# sensor_frontend_test_v0_5_e8a143b4.net
KiCad netlist of a schematic drawn in EAGLE
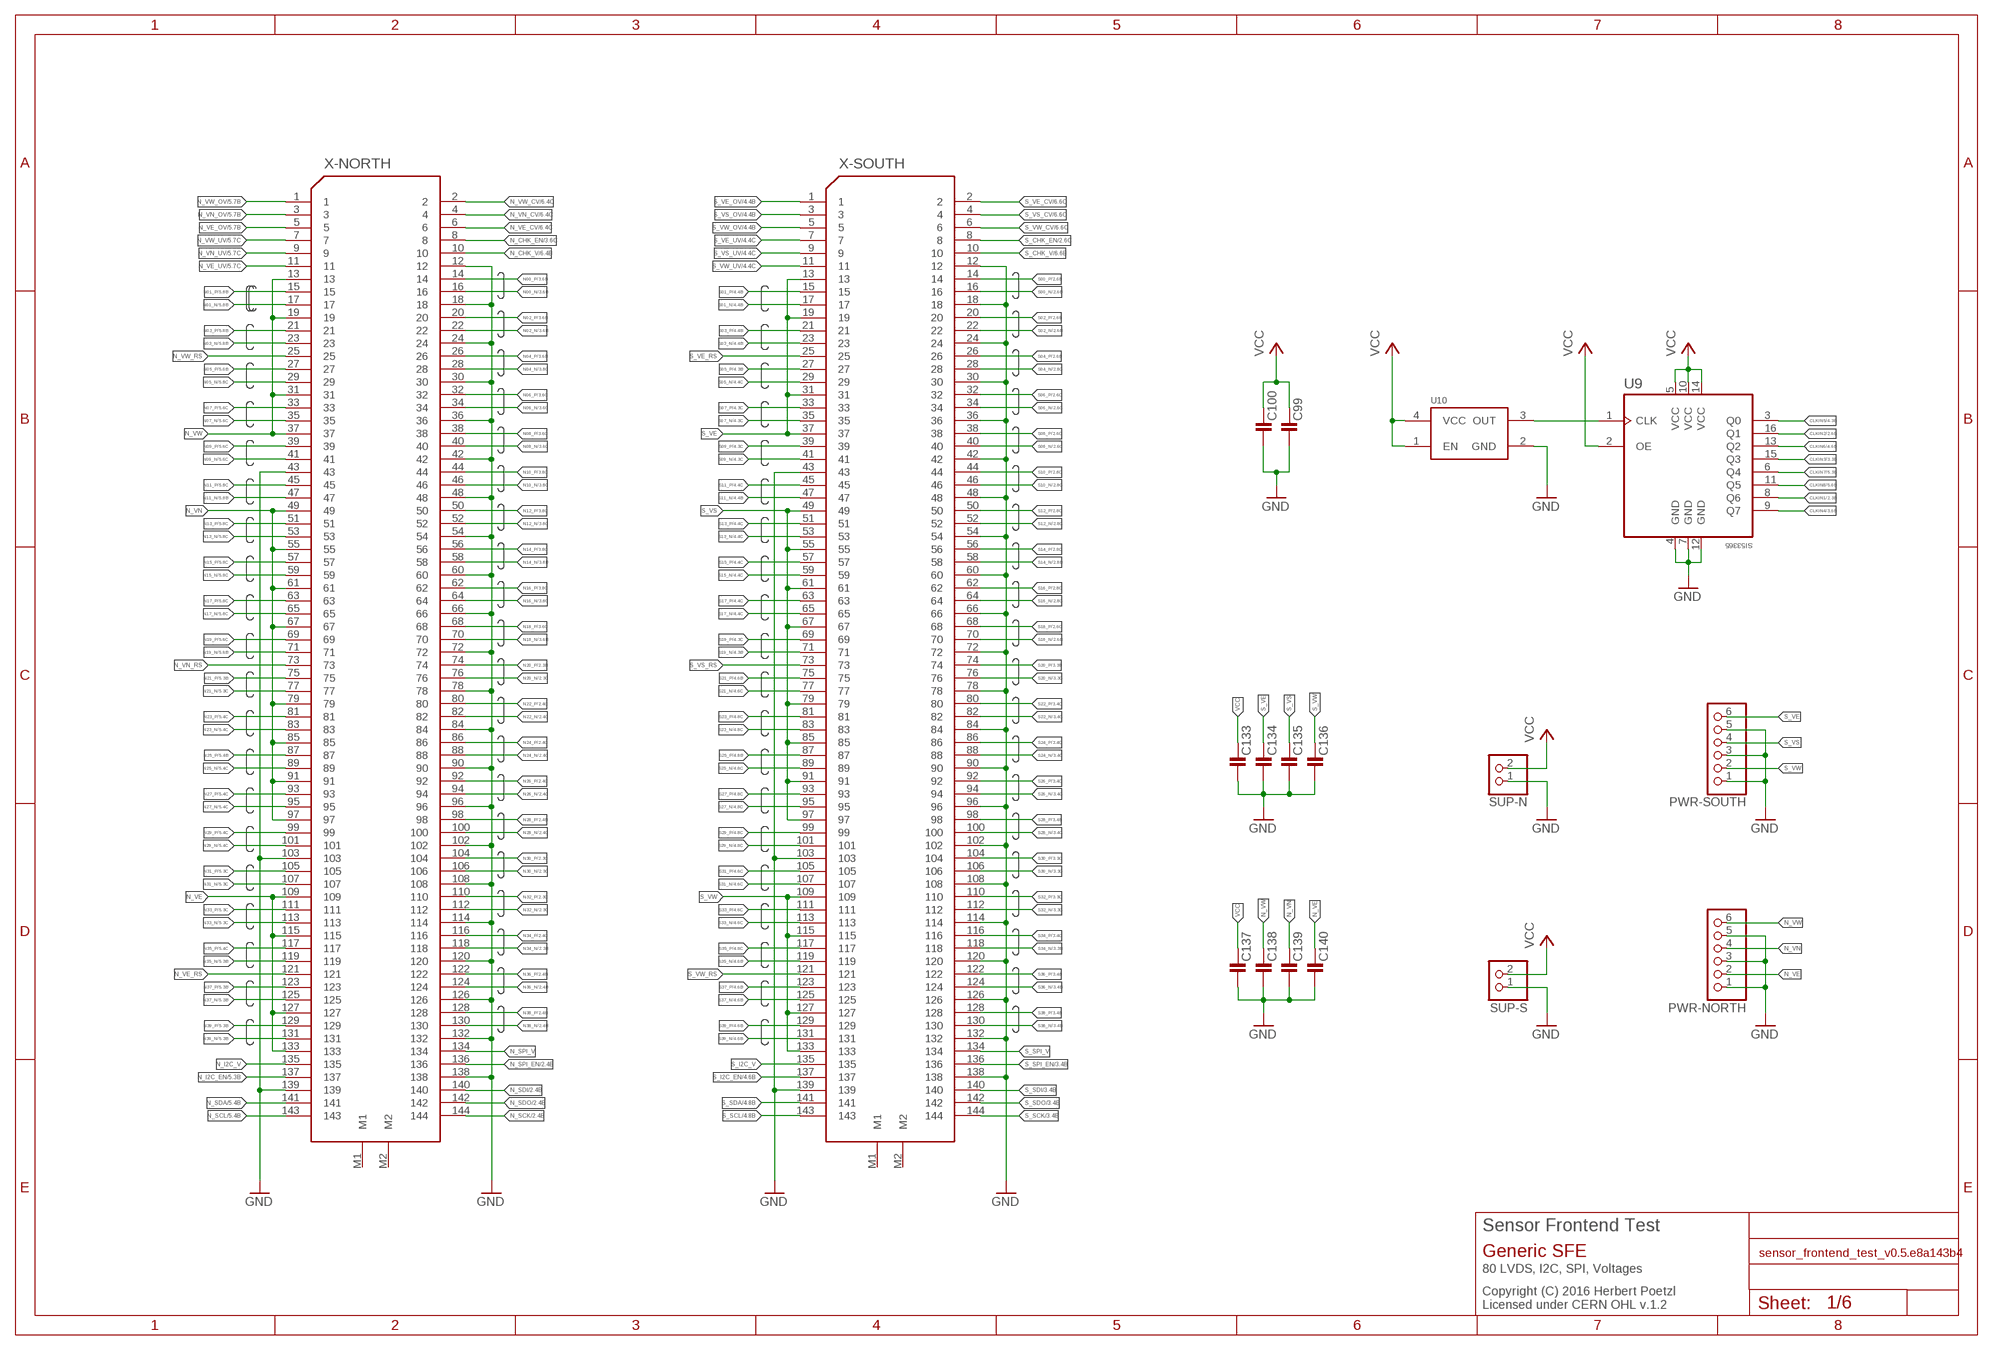
[diagram p0: schematic, sheet 1]
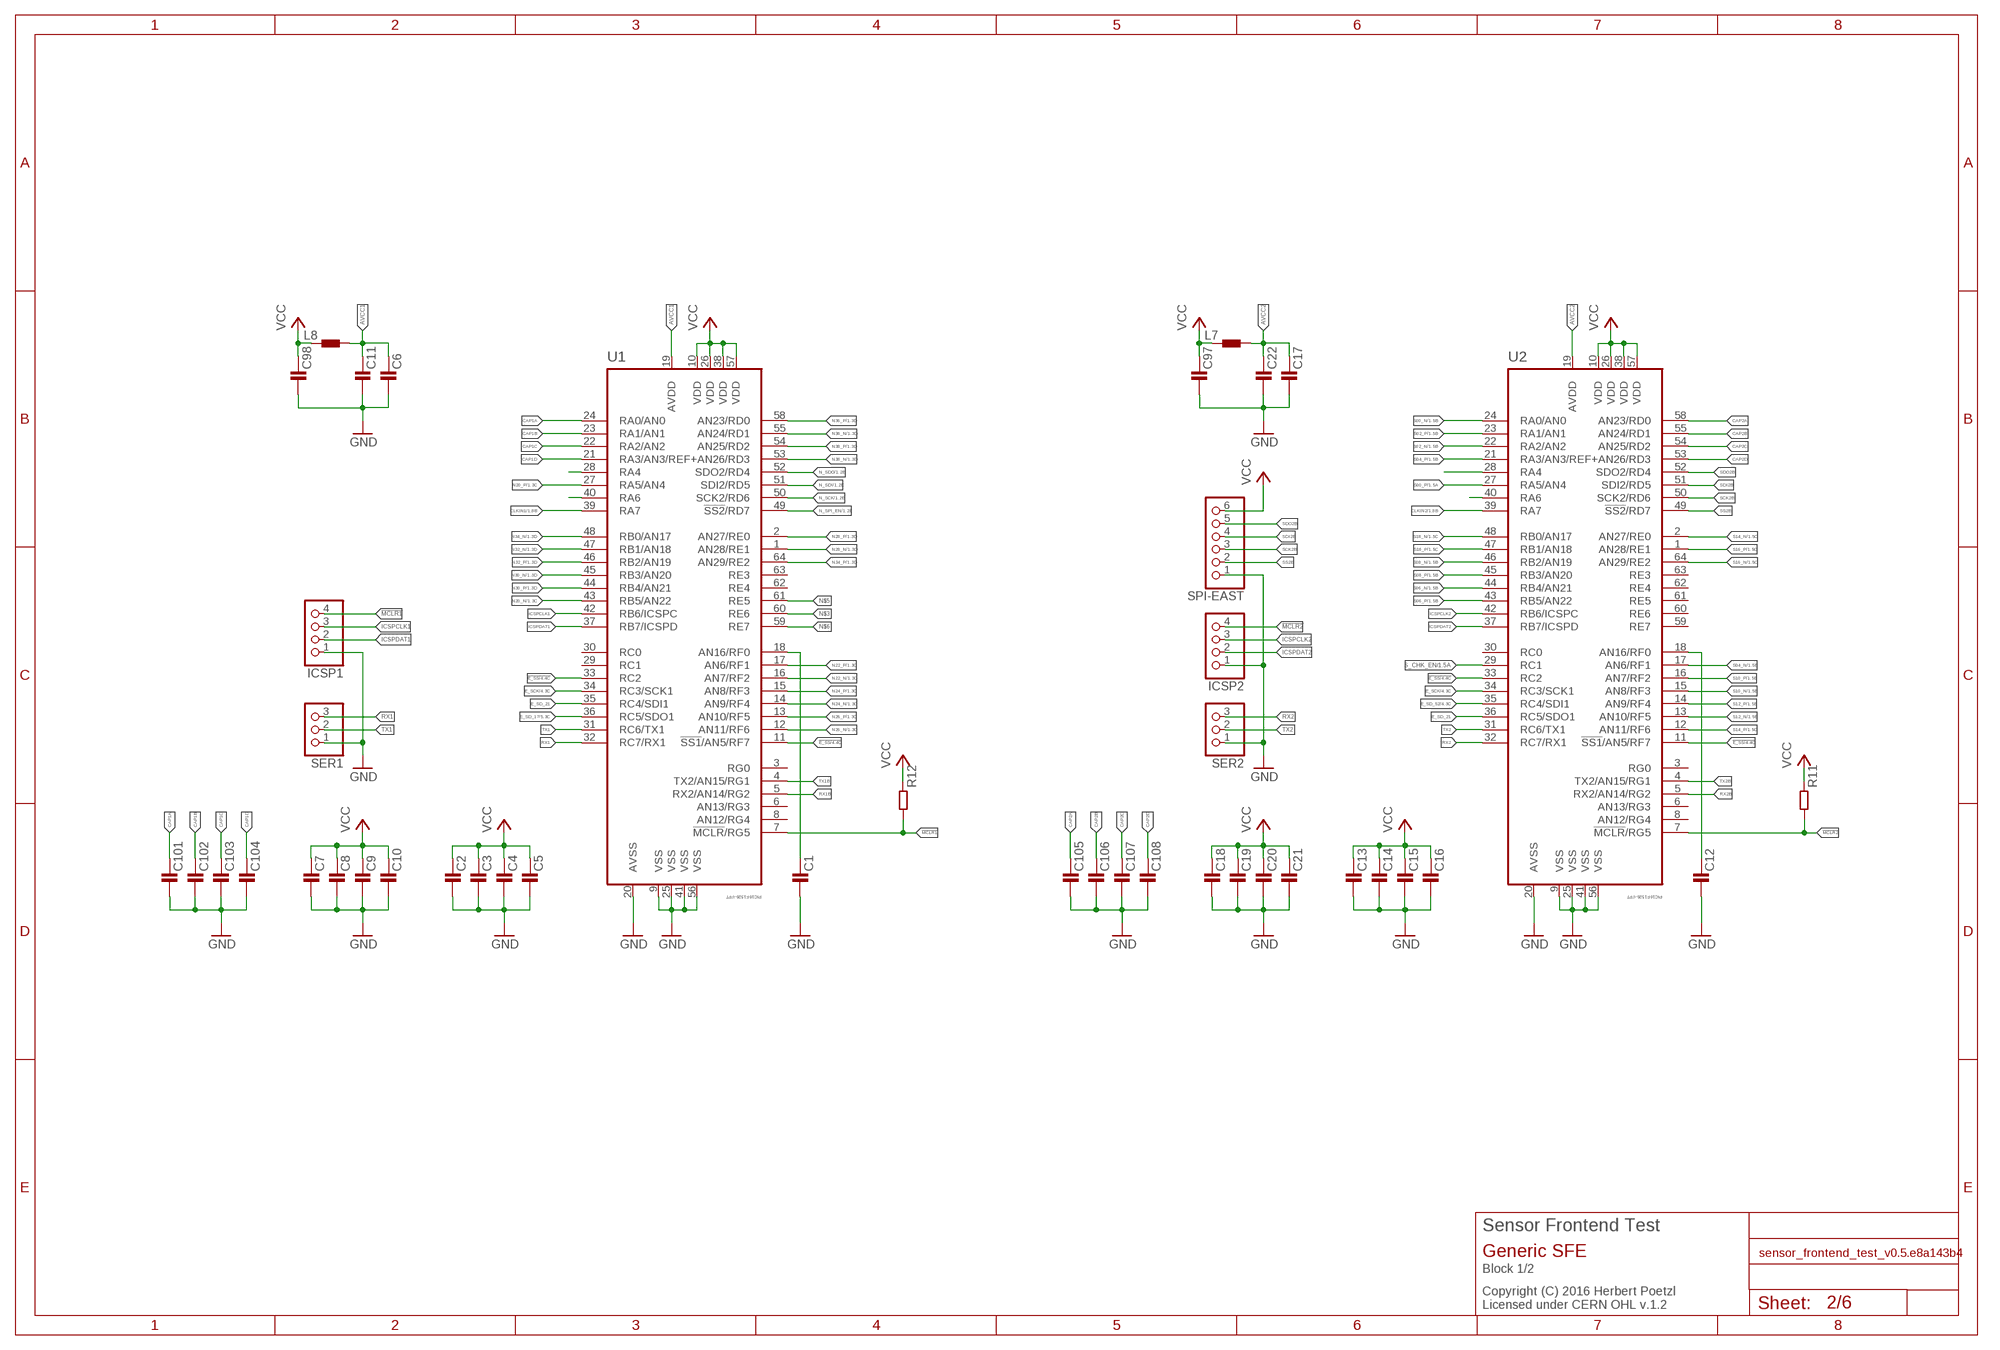
[diagram p1: schematic, sheet 2]
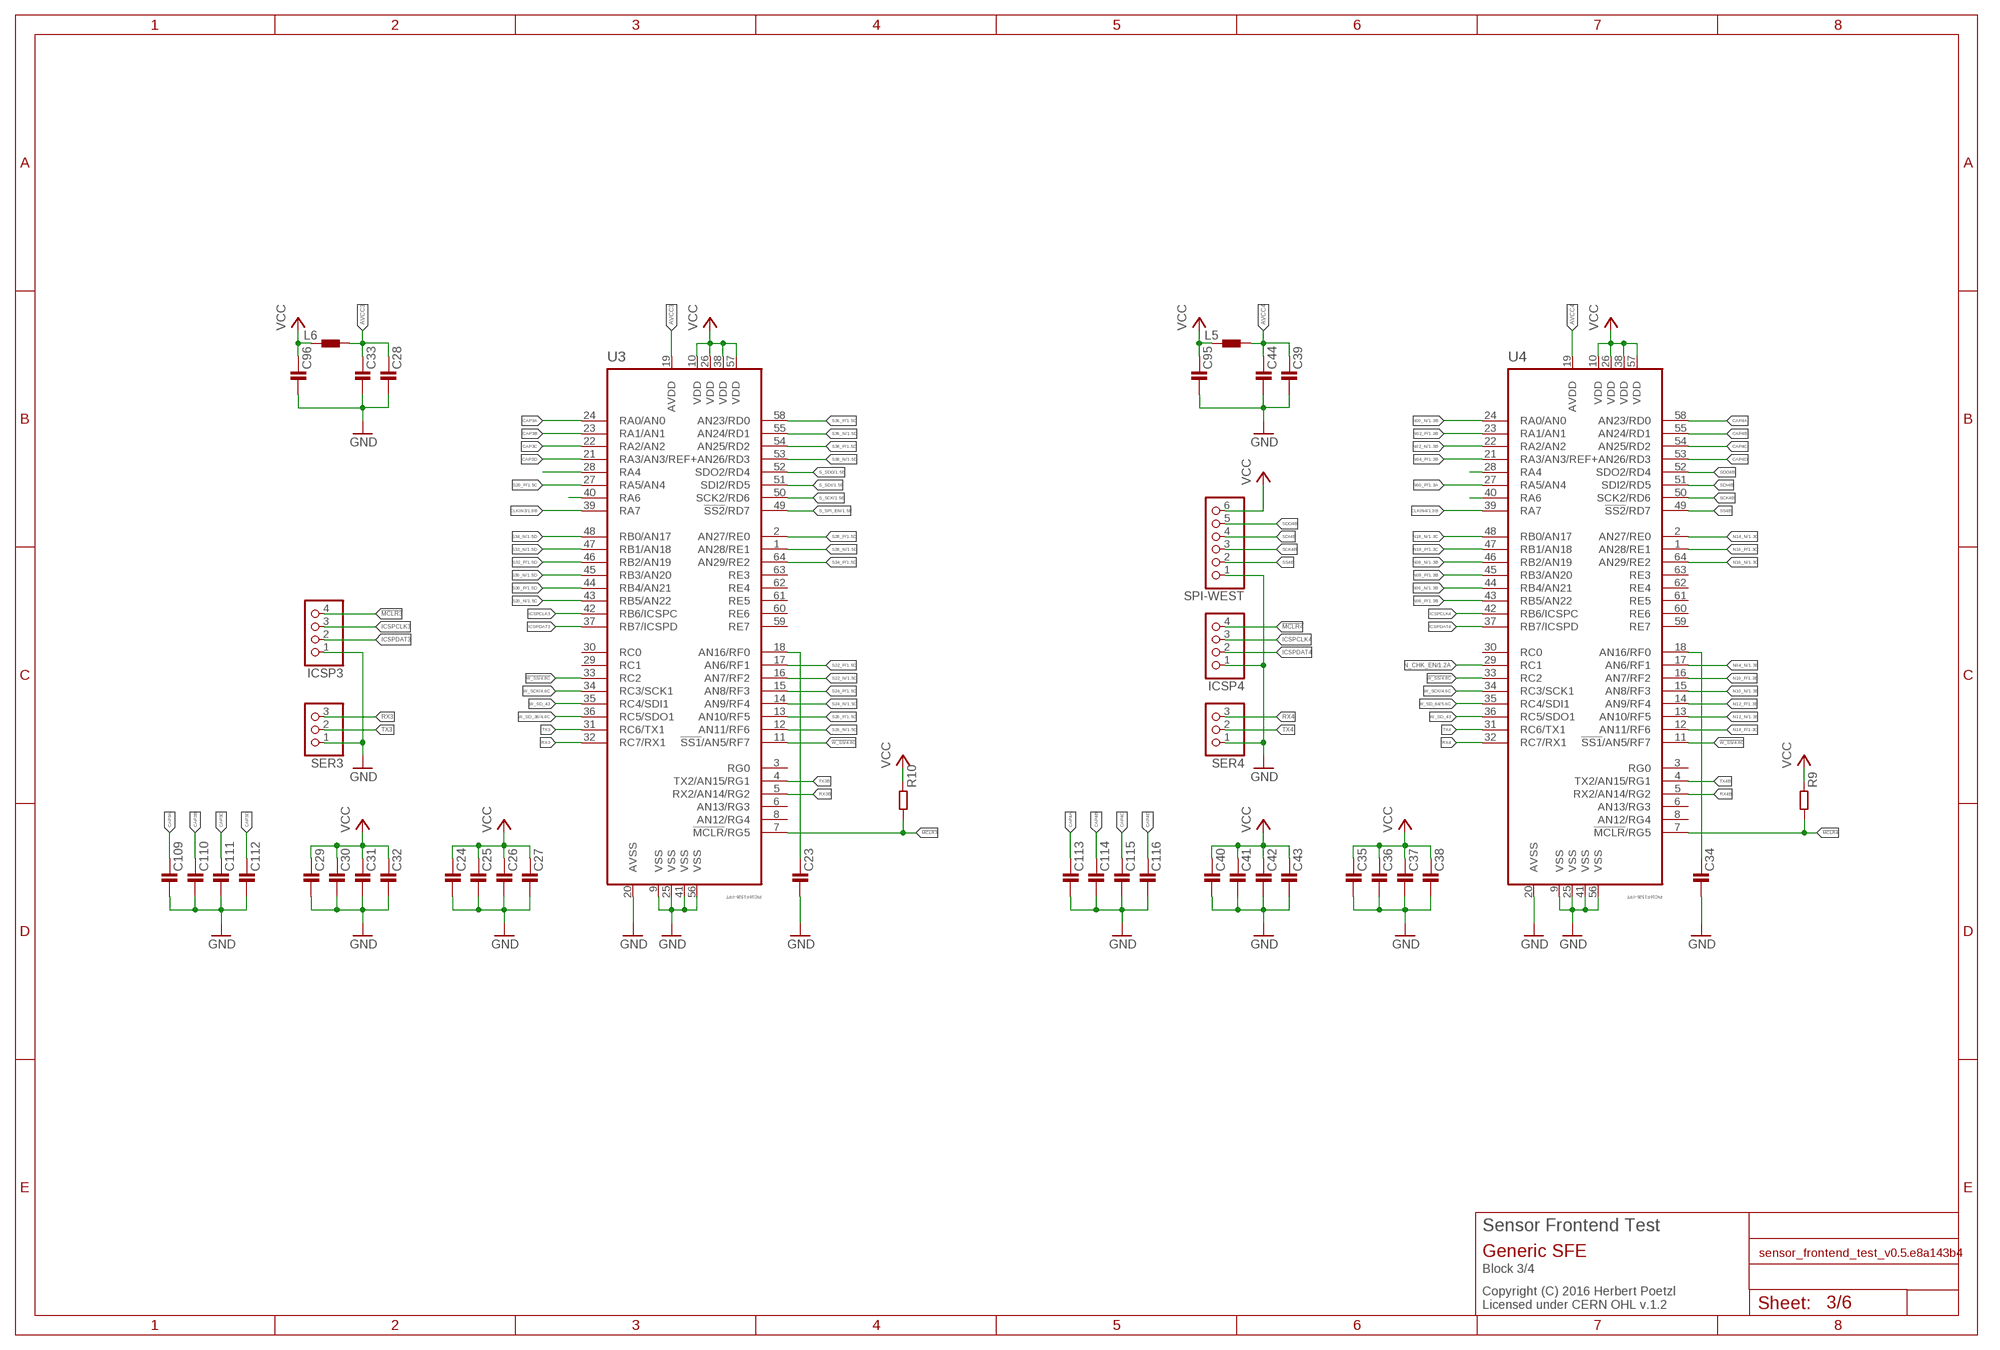
[diagram p2: schematic, sheet 3]
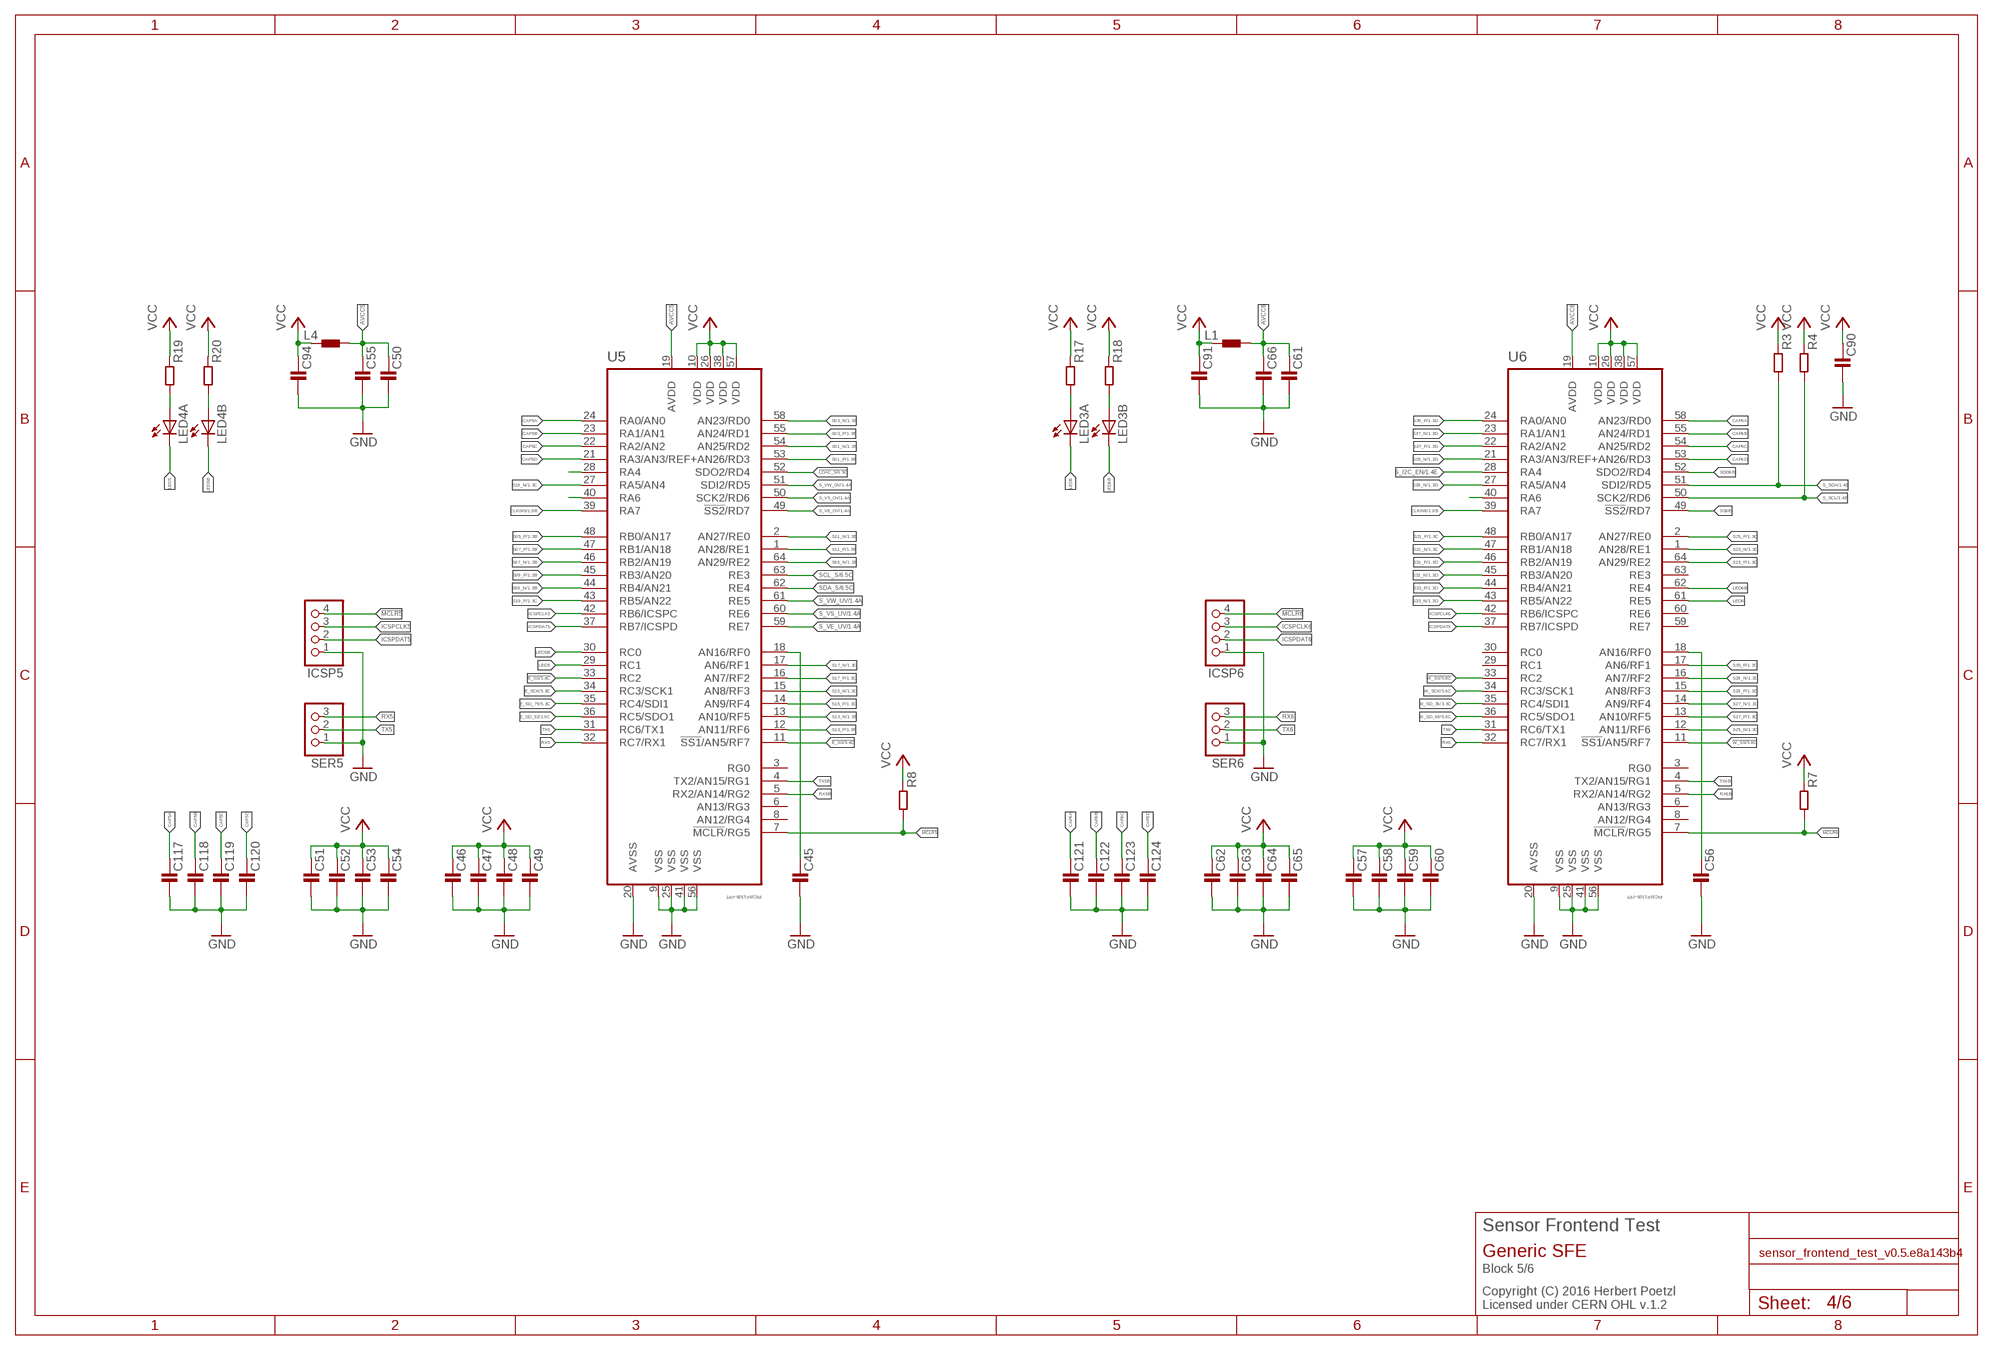
[diagram p3: schematic, sheet 4]
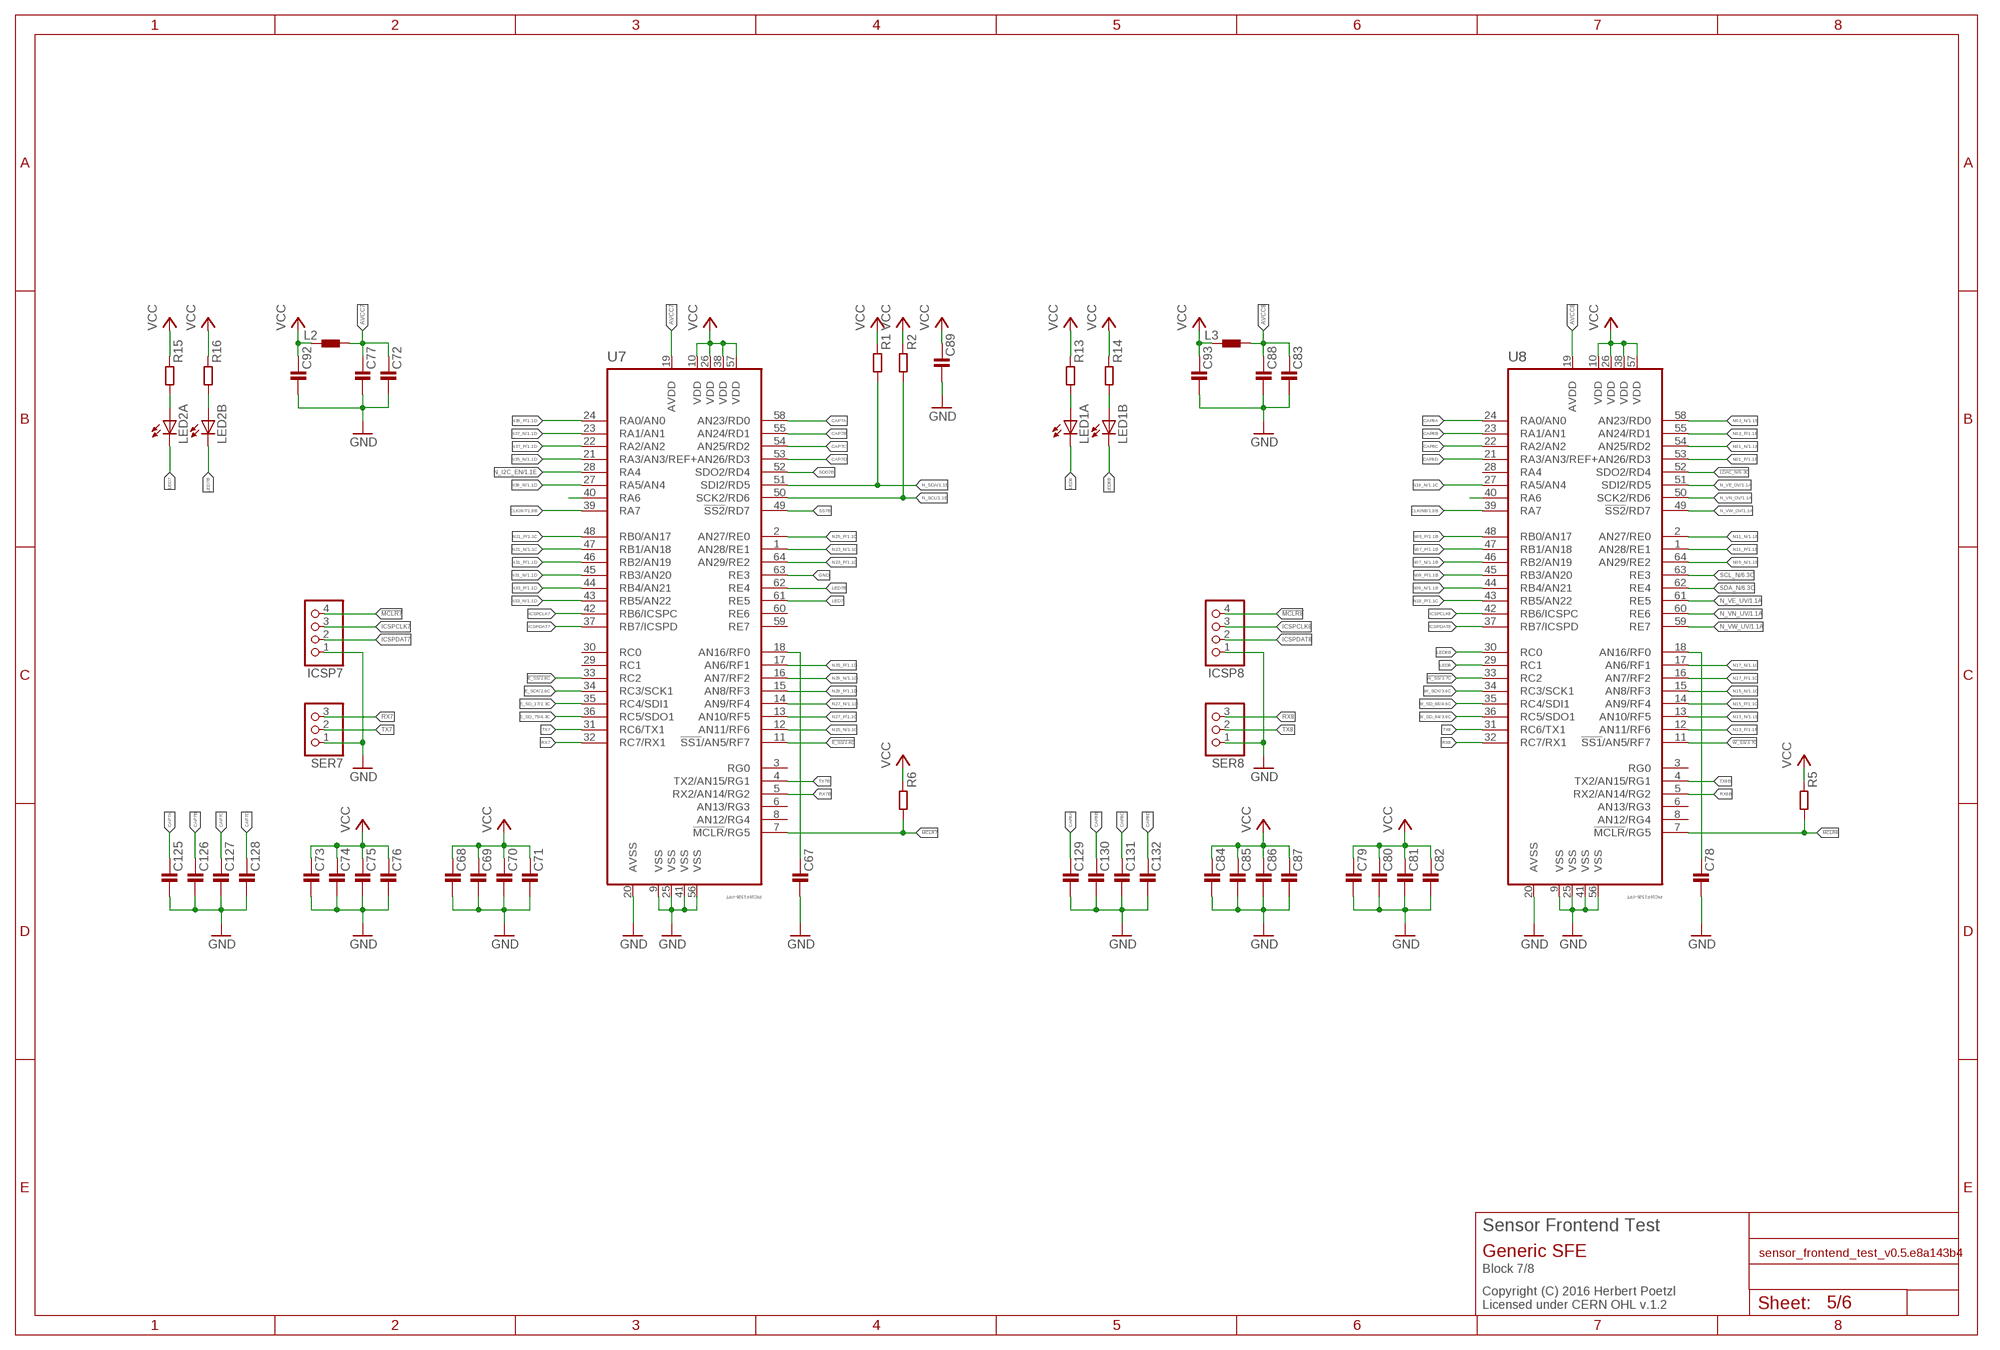
[diagram p4: schematic, sheet 5]
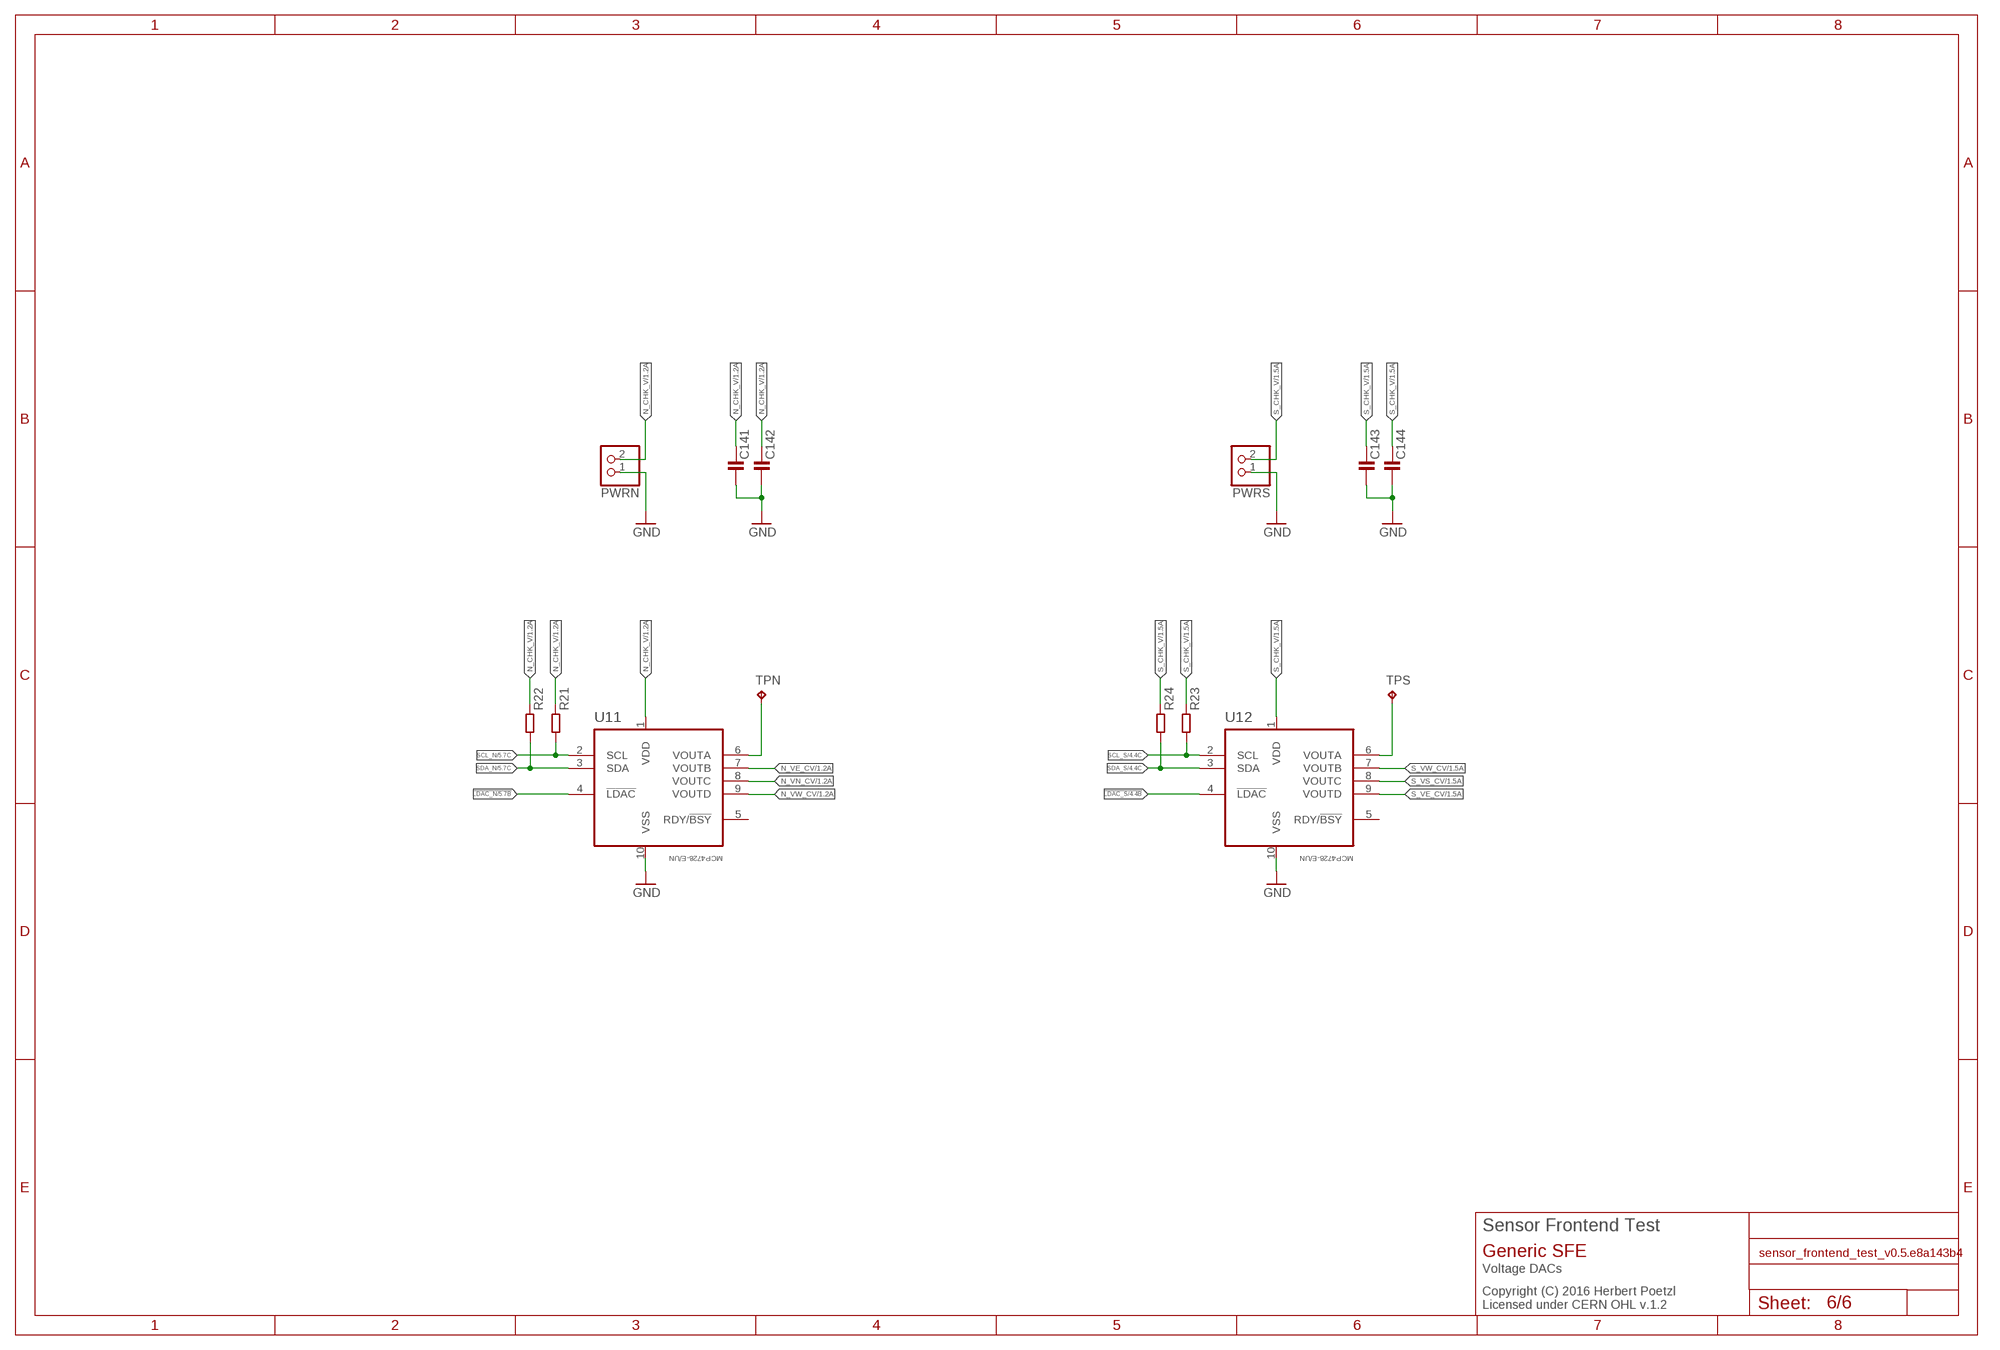
[diagram p5: schematic, sheet 6]

(export (version "E")
  (design (tool "Eeschema 10.0.6"))
  (components
    (comp (ref "C1")
      (value "C0402-B")
      (footprint "eagle-import:0402-B")
      (libsource (lib "eagle-import") (part "C0402-B"))
    )
    (comp (ref "C2")
      (value "C0402-B")
      (footprint "eagle-import:0402-B")
      (libsource (lib "eagle-import") (part "C0402-B"))
    )
    (comp (ref "C3")
      (value "C0402-B")
      (footprint "eagle-import:0402-B")
      (libsource (lib "eagle-import") (part "C0402-B"))
    )
    (comp (ref "C4")
      (value "C0402-B")
      (footprint "eagle-import:0402-B")
      (libsource (lib "eagle-import") (part "C0402-B"))
    )
    (comp (ref "C5")
      (value "C0402-B")
      (footprint "eagle-import:0402-B")
      (libsource (lib "eagle-import") (part "C0402-B"))
    )
    (comp (ref "C6")
      (value "C0402-B")
      (footprint "eagle-import:0402-B")
      (libsource (lib "eagle-import") (part "C0402-B"))
    )
    (comp (ref "C7")
      (value "C0402-B")
      (footprint "eagle-import:0402-B")
      (libsource (lib "eagle-import") (part "C0402-B"))
    )
    (comp (ref "C8")
      (value "C0402-B")
      (footprint "eagle-import:0402-B")
      (libsource (lib "eagle-import") (part "C0402-B"))
    )
    (comp (ref "C9")
      (value "C0402-B")
      (footprint "eagle-import:0402-B")
      (libsource (lib "eagle-import") (part "C0402-B"))
    )
    (comp (ref "C10")
      (value "C0402-B")
      (footprint "eagle-import:0402-B")
      (libsource (lib "eagle-import") (part "C0402-B"))
    )
    (comp (ref "C11")
      (value "C0402-B")
      (footprint "eagle-import:0402-B")
      (libsource (lib "eagle-import") (part "C0402-B"))
    )
    (comp (ref "C12")
      (value "C0402-B")
      (footprint "eagle-import:0402-B")
      (libsource (lib "eagle-import") (part "C0402-B"))
    )
    (comp (ref "C13")
      (value "C0402-B")
      (footprint "eagle-import:0402-B")
      (libsource (lib "eagle-import") (part "C0402-B"))
    )
    (comp (ref "C14")
      (value "C0402-B")
      (footprint "eagle-import:0402-B")
      (libsource (lib "eagle-import") (part "C0402-B"))
    )
    (comp (ref "C15")
      (value "C0402-B")
      (footprint "eagle-import:0402-B")
      (libsource (lib "eagle-import") (part "C0402-B"))
    )
    (comp (ref "C16")
      (value "C0402-B")
      (footprint "eagle-import:0402-B")
      (libsource (lib "eagle-import") (part "C0402-B"))
    )
    (comp (ref "C17")
      (value "C0402-B")
      (footprint "eagle-import:0402-B")
      (libsource (lib "eagle-import") (part "C0402-B"))
    )
    (comp (ref "C18")
      (value "C0402-B")
      (footprint "eagle-import:0402-B")
      (libsource (lib "eagle-import") (part "C0402-B"))
    )
    (comp (ref "C19")
      (value "C0402-B")
      (footprint "eagle-import:0402-B")
      (libsource (lib "eagle-import") (part "C0402-B"))
    )
    (comp (ref "C20")
      (value "C0402-B")
      (footprint "eagle-import:0402-B")
      (libsource (lib "eagle-import") (part "C0402-B"))
    )
    (comp (ref "C21")
      (value "C0402-B")
      (footprint "eagle-import:0402-B")
      (libsource (lib "eagle-import") (part "C0402-B"))
    )
    (comp (ref "C22")
      (value "C0402-B")
      (footprint "eagle-import:0402-B")
      (libsource (lib "eagle-import") (part "C0402-B"))
    )
    (comp (ref "C97")
      (value "C0402-B")
      (footprint "eagle-import:0402-B")
      (libsource (lib "eagle-import") (part "C0402-B"))
    )
    (comp (ref "C98")
      (value "C0402-B")
      (footprint "eagle-import:0402-B")
      (libsource (lib "eagle-import") (part "C0402-B"))
    )
    (comp (ref "C101")
      (value "C0402-B")
      (footprint "eagle-import:0402-B")
      (libsource (lib "eagle-import") (part "C0402-B"))
    )
    (comp (ref "C102")
      (value "C0402-B")
      (footprint "eagle-import:0402-B")
      (libsource (lib "eagle-import") (part "C0402-B"))
    )
    (comp (ref "C103")
      (value "C0603-B")
      (footprint "eagle-import:0603-B")
      (libsource (lib "eagle-import") (part "C0603-B"))
    )
    (comp (ref "C104")
      (value "C0603-B")
      (footprint "eagle-import:0603-B")
      (libsource (lib "eagle-import") (part "C0603-B"))
    )
    (comp (ref "C105")
      (value "C0402-B")
      (footprint "eagle-import:0402-B")
      (libsource (lib "eagle-import") (part "C0402-B"))
    )
    (comp (ref "C106")
      (value "C0402-B")
      (footprint "eagle-import:0402-B")
      (libsource (lib "eagle-import") (part "C0402-B"))
    )
    (comp (ref "C107")
      (value "C0603-B")
      (footprint "eagle-import:0603-B")
      (libsource (lib "eagle-import") (part "C0603-B"))
    )
    (comp (ref "C108")
      (value "C0603-B")
      (footprint "eagle-import:0603-B")
      (libsource (lib "eagle-import") (part "C0603-B"))
    )
    (comp (ref "ICSP1")
      (value "PINHD-1X04_2.00")
      (footprint "eagle-import:1X04M")
      (libsource (lib "eagle-import") (part "PINHD-1X04_2.00"))
    )
    (comp (ref "ICSP2")
      (value "PINHD-1X04_2.00")
      (footprint "eagle-import:1X04M")
      (libsource (lib "eagle-import") (part "PINHD-1X04_2.00"))
    )
    (comp (ref "L7")
      (value "L0402-B")
      (footprint "eagle-import:0402-B")
      (libsource (lib "eagle-import") (part "L0402-B"))
    )
    (comp (ref "L8")
      (value "L0402-B")
      (footprint "eagle-import:0402-B")
      (libsource (lib "eagle-import") (part "L0402-B"))
    )
    (comp (ref "R11")
      (value "R0402-B")
      (footprint "eagle-import:0402-B")
      (libsource (lib "eagle-import") (part "R0402-B"))
    )
    (comp (ref "R12")
      (value "R0402-B")
      (footprint "eagle-import:0402-B")
      (libsource (lib "eagle-import") (part "R0402-B"))
    )
    (comp (ref "SER1")
      (value "PINHD-1X03_2.00")
      (footprint "eagle-import:1X03M")
      (libsource (lib "eagle-import") (part "PINHD-1X03_2.00"))
    )
    (comp (ref "SER2")
      (value "PINHD-1X03_2.00")
      (footprint "eagle-import:1X03M")
      (libsource (lib "eagle-import") (part "PINHD-1X03_2.00"))
    )
    (comp (ref "SPI-EAST")
      (value "PINHD-1X06_2.00")
      (footprint "eagle-import:1X06M")
      (libsource (lib "eagle-import") (part "PINHD-1X06_2.00"))
    )
    (comp (ref "U1")
      (value "PIC16F1526-I/PT")
      (footprint "eagle-import:QFP50P1200X1200X120-64N")
      (libsource (lib "eagle-import") (part "PIC16F1526-I/PT"))
    )
    (comp (ref "U2")
      (value "PIC16F1526-I/PT")
      (footprint "eagle-import:QFP50P1200X1200X120-64N")
      (libsource (lib "eagle-import") (part "PIC16F1526-I/PT"))
    )
    (comp (ref "C67")
      (value "C0402-B")
      (footprint "eagle-import:0402-B")
      (libsource (lib "eagle-import") (part "C0402-B"))
    )
    (comp (ref "C68")
      (value "C0402-B")
      (footprint "eagle-import:0402-B")
      (libsource (lib "eagle-import") (part "C0402-B"))
    )
    (comp (ref "C69")
      (value "C0402-B")
      (footprint "eagle-import:0402-B")
      (libsource (lib "eagle-import") (part "C0402-B"))
    )
    (comp (ref "C70")
      (value "C0402-B")
      (footprint "eagle-import:0402-B")
      (libsource (lib "eagle-import") (part "C0402-B"))
    )
    (comp (ref "C71")
      (value "C0402-B")
      (footprint "eagle-import:0402-B")
      (libsource (lib "eagle-import") (part "C0402-B"))
    )
    (comp (ref "C72")
      (value "C0402-B")
      (footprint "eagle-import:0402-B")
      (libsource (lib "eagle-import") (part "C0402-B"))
    )
    (comp (ref "C73")
      (value "C0402-B")
      (footprint "eagle-import:0402-B")
      (libsource (lib "eagle-import") (part "C0402-B"))
    )
    (comp (ref "C74")
      (value "C0402-B")
      (footprint "eagle-import:0402-B")
      (libsource (lib "eagle-import") (part "C0402-B"))
    )
    (comp (ref "C75")
      (value "C0402-B")
      (footprint "eagle-import:0402-B")
      (libsource (lib "eagle-import") (part "C0402-B"))
    )
    (comp (ref "C76")
      (value "C0402-B")
      (footprint "eagle-import:0402-B")
      (libsource (lib "eagle-import") (part "C0402-B"))
    )
    (comp (ref "C77")
      (value "C0402-B")
      (footprint "eagle-import:0402-B")
      (libsource (lib "eagle-import") (part "C0402-B"))
    )
    (comp (ref "C78")
      (value "C0402-B")
      (footprint "eagle-import:0402-B")
      (libsource (lib "eagle-import") (part "C0402-B"))
    )
    (comp (ref "C79")
      (value "C0402-B")
      (footprint "eagle-import:0402-B")
      (libsource (lib "eagle-import") (part "C0402-B"))
    )
    (comp (ref "C80")
      (value "C0402-B")
      (footprint "eagle-import:0402-B")
      (libsource (lib "eagle-import") (part "C0402-B"))
    )
    (comp (ref "C81")
      (value "C0402-B")
      (footprint "eagle-import:0402-B")
      (libsource (lib "eagle-import") (part "C0402-B"))
    )
    (comp (ref "C82")
      (value "C0402-B")
      (footprint "eagle-import:0402-B")
      (libsource (lib "eagle-import") (part "C0402-B"))
    )
    (comp (ref "C83")
      (value "C0402-B")
      (footprint "eagle-import:0402-B")
      (libsource (lib "eagle-import") (part "C0402-B"))
    )
    (comp (ref "C84")
      (value "C0402-B")
      (footprint "eagle-import:0402-B")
      (libsource (lib "eagle-import") (part "C0402-B"))
    )
    (comp (ref "C85")
      (value "C0402-B")
      (footprint "eagle-import:0402-B")
      (libsource (lib "eagle-import") (part "C0402-B"))
    )
    (comp (ref "C86")
      (value "C0402-B")
      (footprint "eagle-import:0402-B")
      (libsource (lib "eagle-import") (part "C0402-B"))
    )
    (comp (ref "C87")
      (value "C0402-B")
      (footprint "eagle-import:0402-B")
      (libsource (lib "eagle-import") (part "C0402-B"))
    )
    (comp (ref "C88")
      (value "C0402-B")
      (footprint "eagle-import:0402-B")
      (libsource (lib "eagle-import") (part "C0402-B"))
    )
    (comp (ref "C89")
      (value "C0402-B")
      (footprint "eagle-import:0402-B")
      (libsource (lib "eagle-import") (part "C0402-B"))
    )
    (comp (ref "C92")
      (value "C0402-B")
      (footprint "eagle-import:0402-B")
      (libsource (lib "eagle-import") (part "C0402-B"))
    )
    (comp (ref "C93")
      (value "C0402-B")
      (footprint "eagle-import:0402-B")
      (libsource (lib "eagle-import") (part "C0402-B"))
    )
    (comp (ref "C125")
      (value "C0402-B")
      (footprint "eagle-import:0402-B")
      (libsource (lib "eagle-import") (part "C0402-B"))
    )
    (comp (ref "C126")
      (value "C0402-B")
      (footprint "eagle-import:0402-B")
      (libsource (lib "eagle-import") (part "C0402-B"))
    )
    (comp (ref "C127")
      (value "C0603-B")
      (footprint "eagle-import:0603-B")
      (libsource (lib "eagle-import") (part "C0603-B"))
    )
    (comp (ref "C128")
      (value "C0603-B")
      (footprint "eagle-import:0603-B")
      (libsource (lib "eagle-import") (part "C0603-B"))
    )
    (comp (ref "C129")
      (value "C0402-B")
      (footprint "eagle-import:0402-B")
      (libsource (lib "eagle-import") (part "C0402-B"))
    )
    (comp (ref "C130")
      (value "C0402-B")
      (footprint "eagle-import:0402-B")
      (libsource (lib "eagle-import") (part "C0402-B"))
    )
    (comp (ref "C131")
      (value "C0603-B")
      (footprint "eagle-import:0603-B")
      (libsource (lib "eagle-import") (part "C0603-B"))
    )
    (comp (ref "C132")
      (value "C0603-B")
      (footprint "eagle-import:0603-B")
      (libsource (lib "eagle-import") (part "C0603-B"))
    )
    (comp (ref "ICSP7")
      (value "PINHD-1X04_2.00")
      (footprint "eagle-import:1X04M")
      (libsource (lib "eagle-import") (part "PINHD-1X04_2.00"))
    )
    (comp (ref "ICSP8")
      (value "PINHD-1X04_2.00")
      (footprint "eagle-import:1X04M")
      (libsource (lib "eagle-import") (part "PINHD-1X04_2.00"))
    )
    (comp (ref "L2")
      (value "L0402-B")
      (footprint "eagle-import:0402-B")
      (libsource (lib "eagle-import") (part "L0402-B"))
    )
    (comp (ref "L3")
      (value "L0402-B")
      (footprint "eagle-import:0402-B")
      (libsource (lib "eagle-import") (part "L0402-B"))
    )
    (comp (ref "LED1")
      (value "DUAL-LED-0404")
      (footprint "eagle-import:0404")
      (libsource (lib "eagle-import") (part "DUAL-LED-0404"))
    )
    (comp (ref "LED2")
      (value "DUAL-LED-0404")
      (footprint "eagle-import:0404")
      (libsource (lib "eagle-import") (part "DUAL-LED-0404"))
    )
    (comp (ref "R1")
      (value "R0402-B")
      (footprint "eagle-import:0402-B")
      (libsource (lib "eagle-import") (part "R0402-B"))
    )
    (comp (ref "R2")
      (value "R0402-B")
      (footprint "eagle-import:0402-B")
      (libsource (lib "eagle-import") (part "R0402-B"))
    )
    (comp (ref "R5")
      (value "R0402-B")
      (footprint "eagle-import:0402-B")
      (libsource (lib "eagle-import") (part "R0402-B"))
    )
    (comp (ref "R6")
      (value "R0402-B")
      (footprint "eagle-import:0402-B")
      (libsource (lib "eagle-import") (part "R0402-B"))
    )
    (comp (ref "R13")
      (value "R0402-B")
      (footprint "eagle-import:0402-B")
      (libsource (lib "eagle-import") (part "R0402-B"))
    )
    (comp (ref "R14")
      (value "R0402-B")
      (footprint "eagle-import:0402-B")
      (libsource (lib "eagle-import") (part "R0402-B"))
    )
    (comp (ref "R15")
      (value "R0402-B")
      (footprint "eagle-import:0402-B")
      (libsource (lib "eagle-import") (part "R0402-B"))
    )
    (comp (ref "R16")
      (value "R0402-B")
      (footprint "eagle-import:0402-B")
      (libsource (lib "eagle-import") (part "R0402-B"))
    )
    (comp (ref "SER7")
      (value "PINHD-1X03_2.00")
      (footprint "eagle-import:1X03M")
      (libsource (lib "eagle-import") (part "PINHD-1X03_2.00"))
    )
    (comp (ref "SER8")
      (value "PINHD-1X03_2.00")
      (footprint "eagle-import:1X03M")
      (libsource (lib "eagle-import") (part "PINHD-1X03_2.00"))
    )
    (comp (ref "U7")
      (value "PIC16F1526-I/PT")
      (footprint "eagle-import:QFP50P1200X1200X120-64N")
      (libsource (lib "eagle-import") (part "PIC16F1526-I/PT"))
    )
    (comp (ref "U8")
      (value "PIC16F1526-I/PT")
      (footprint "eagle-import:QFP50P1200X1200X120-64N")
      (libsource (lib "eagle-import") (part "PIC16F1526-I/PT"))
    )
    (comp (ref "C99")
      (value "C0402-B")
      (footprint "eagle-import:0402-B")
      (libsource (lib "eagle-import") (part "C0402-B"))
    )
    (comp (ref "C100")
      (value "C0402-B")
      (footprint "eagle-import:0402-B")
      (libsource (lib "eagle-import") (part "C0402-B"))
    )
    (comp (ref "C133")
      (value "C0805-A")
      (footprint "eagle-import:0805-A")
      (libsource (lib "eagle-import") (part "C0805-A"))
    )
    (comp (ref "C134")
      (value "C0805-A")
      (footprint "eagle-import:0805-A")
      (libsource (lib "eagle-import") (part "C0805-A"))
    )
    (comp (ref "C135")
      (value "C0805-A")
      (footprint "eagle-import:0805-A")
      (libsource (lib "eagle-import") (part "C0805-A"))
    )
    (comp (ref "C136")
      (value "C0805-A")
      (footprint "eagle-import:0805-A")
      (libsource (lib "eagle-import") (part "C0805-A"))
    )
    (comp (ref "C137")
      (value "C0805-A")
      (footprint "eagle-import:0805-A")
      (libsource (lib "eagle-import") (part "C0805-A"))
    )
    (comp (ref "C138")
      (value "C0805-A")
      (footprint "eagle-import:0805-A")
      (libsource (lib "eagle-import") (part "C0805-A"))
    )
    (comp (ref "C139")
      (value "C0805-A")
      (footprint "eagle-import:0805-A")
      (libsource (lib "eagle-import") (part "C0805-A"))
    )
    (comp (ref "C140")
      (value "C0805-A")
      (footprint "eagle-import:0805-A")
      (libsource (lib "eagle-import") (part "C0805-A"))
    )
    (comp (ref "PWR-NORTH")
      (value "PINHD-1X06_2.54-S")
      (footprint "eagle-import:1X06-S")
      (libsource (lib "eagle-import") (part "PINHD-1X06_2.54-S"))
    )
    (comp (ref "PWR-SOUTH")
      (value "PINHD-1X06_2.54-S")
      (footprint "eagle-import:1X06-S")
      (libsource (lib "eagle-import") (part "PINHD-1X06_2.54-S"))
    )
    (comp (ref "SUP-N")
      (value "PINHD-1X02_2.54-S")
      (footprint "eagle-import:1X02-S")
      (libsource (lib "eagle-import") (part "PINHD-1X02_2.54-S"))
    )
    (comp (ref "SUP-S")
      (value "PINHD-1X02_2.54-S")
      (footprint "eagle-import:1X02-S")
      (libsource (lib "eagle-import") (part "PINHD-1X02_2.54-S"))
    )
    (comp (ref "U9")
      (value "SI53365")
      (footprint "eagle-import:SOP65P640X120-16N")
      (libsource (lib "eagle-import") (part "SI53365"))
    )
    (comp (ref "U10")
      (value "OSCILLATOR5X3-PIN1-INDICATED")
      (footprint "eagle-import:CRYSTAL-OSC-SMD-5X3")
      (libsource (lib "eagle-import") (part "OSCILLATOR5X3-PIN1-INDICATED"))
    )
    (comp (ref "X-NORTH")
      (value "FX10-144S")
      (footprint "eagle-import:FX10A-144S")
      (libsource (lib "eagle-import") (part "FX10-144S"))
    )
    (comp (ref "X-SOUTH")
      (value "FX10-144S")
      (footprint "eagle-import:FX10A-144S")
      (libsource (lib "eagle-import") (part "FX10-144S"))
    )
    (comp (ref "C141")
      (value "C0402-B")
      (footprint "eagle-import:0402-B")
      (libsource (lib "eagle-import") (part "C0402-B"))
    )
    (comp (ref "C142")
      (value "C0402-B")
      (footprint "eagle-import:0402-B")
      (libsource (lib "eagle-import") (part "C0402-B"))
    )
    (comp (ref "C143")
      (value "C0402-B")
      (footprint "eagle-import:0402-B")
      (libsource (lib "eagle-import") (part "C0402-B"))
    )
    (comp (ref "C144")
      (value "C0402-B")
      (footprint "eagle-import:0402-B")
      (libsource (lib "eagle-import") (part "C0402-B"))
    )
    (comp (ref "PWRN")
      (value "PINHD-1X02_2.00")
      (footprint "eagle-import:1X02M")
      (libsource (lib "eagle-import") (part "PINHD-1X02_2.00"))
    )
    (comp (ref "PWRS")
      (value "PINHD-1X02_2.00")
      (footprint "eagle-import:1X02M")
      (libsource (lib "eagle-import") (part "PINHD-1X02_2.00"))
    )
    (comp (ref "R21")
      (value "R0402-B")
      (footprint "eagle-import:0402-B")
      (libsource (lib "eagle-import") (part "R0402-B"))
    )
    (comp (ref "R22")
      (value "R0402-B")
      (footprint "eagle-import:0402-B")
      (libsource (lib "eagle-import") (part "R0402-B"))
    )
    (comp (ref "R23")
      (value "R0402-B")
      (footprint "eagle-import:0402-B")
      (libsource (lib "eagle-import") (part "R0402-B"))
    )
    (comp (ref "R24")
      (value "R0402-B")
      (footprint "eagle-import:0402-B")
      (libsource (lib "eagle-import") (part "R0402-B"))
    )
    (comp (ref "TPN")
      (value "TPTP16R")
      (footprint "eagle-import:TP16R")
      (libsource (lib "eagle-import") (part "TPTP16R"))
    )
    (comp (ref "TPS")
      (value "TPTP16R")
      (footprint "eagle-import:TP16R")
      (libsource (lib "eagle-import") (part "TPTP16R"))
    )
    (comp (ref "U11")
      (value "MCP4728-E/UN")
      (footprint "eagle-import:SOP50P490X110-10N")
      (libsource (lib "eagle-import") (part "MCP4728-E/UN"))
    )
    (comp (ref "U12")
      (value "MCP4728-E/UN")
      (footprint "eagle-import:SOP50P490X110-10N")
      (libsource (lib "eagle-import") (part "MCP4728-E/UN"))
    )
    (comp (ref "C45")
      (value "C0402-B")
      (footprint "eagle-import:0402-B")
      (libsource (lib "eagle-import") (part "C0402-B"))
    )
    (comp (ref "C46")
      (value "C0402-B")
      (footprint "eagle-import:0402-B")
      (libsource (lib "eagle-import") (part "C0402-B"))
    )
    (comp (ref "C47")
      (value "C0402-B")
      (footprint "eagle-import:0402-B")
      (libsource (lib "eagle-import") (part "C0402-B"))
    )
    (comp (ref "C48")
      (value "C0402-B")
      (footprint "eagle-import:0402-B")
      (libsource (lib "eagle-import") (part "C0402-B"))
    )
    (comp (ref "C49")
      (value "C0402-B")
      (footprint "eagle-import:0402-B")
      (libsource (lib "eagle-import") (part "C0402-B"))
    )
    (comp (ref "C50")
      (value "C0402-B")
      (footprint "eagle-import:0402-B")
      (libsource (lib "eagle-import") (part "C0402-B"))
    )
    (comp (ref "C51")
      (value "C0402-B")
      (footprint "eagle-import:0402-B")
      (libsource (lib "eagle-import") (part "C0402-B"))
    )
    (comp (ref "C52")
      (value "C0402-B")
      (footprint "eagle-import:0402-B")
      (libsource (lib "eagle-import") (part "C0402-B"))
    )
    (comp (ref "C53")
      (value "C0402-B")
      (footprint "eagle-import:0402-B")
      (libsource (lib "eagle-import") (part "C0402-B"))
    )
    (comp (ref "C54")
      (value "C0402-B")
      (footprint "eagle-import:0402-B")
      (libsource (lib "eagle-import") (part "C0402-B"))
    )
    (comp (ref "C55")
      (value "C0402-B")
      (footprint "eagle-import:0402-B")
      (libsource (lib "eagle-import") (part "C0402-B"))
    )
    (comp (ref "C56")
      (value "C0402-B")
      (footprint "eagle-import:0402-B")
      (libsource (lib "eagle-import") (part "C0402-B"))
    )
    (comp (ref "C57")
      (value "C0402-B")
      (footprint "eagle-import:0402-B")
      (libsource (lib "eagle-import") (part "C0402-B"))
    )
    (comp (ref "C58")
      (value "C0402-B")
      (footprint "eagle-import:0402-B")
      (libsource (lib "eagle-import") (part "C0402-B"))
    )
    (comp (ref "C59")
      (value "C0402-B")
      (footprint "eagle-import:0402-B")
      (libsource (lib "eagle-import") (part "C0402-B"))
    )
    (comp (ref "C60")
      (value "C0402-B")
      (footprint "eagle-import:0402-B")
      (libsource (lib "eagle-import") (part "C0402-B"))
    )
    (comp (ref "C61")
      (value "C0402-B")
      (footprint "eagle-import:0402-B")
      (libsource (lib "eagle-import") (part "C0402-B"))
    )
    (comp (ref "C62")
      (value "C0402-B")
      (footprint "eagle-import:0402-B")
      (libsource (lib "eagle-import") (part "C0402-B"))
    )
    (comp (ref "C63")
      (value "C0402-B")
      (footprint "eagle-import:0402-B")
      (libsource (lib "eagle-import") (part "C0402-B"))
    )
    (comp (ref "C64")
      (value "C0402-B")
      (footprint "eagle-import:0402-B")
      (libsource (lib "eagle-import") (part "C0402-B"))
    )
    (comp (ref "C65")
      (value "C0402-B")
      (footprint "eagle-import:0402-B")
      (libsource (lib "eagle-import") (part "C0402-B"))
    )
    (comp (ref "C66")
      (value "C0402-B")
      (footprint "eagle-import:0402-B")
      (libsource (lib "eagle-import") (part "C0402-B"))
    )
    (comp (ref "C90")
      (value "C0402-B")
      (footprint "eagle-import:0402-B")
      (libsource (lib "eagle-import") (part "C0402-B"))
    )
    (comp (ref "C91")
      (value "C0402-B")
      (footprint "eagle-import:0402-B")
      (libsource (lib "eagle-import") (part "C0402-B"))
    )
    (comp (ref "C94")
      (value "C0402-B")
      (footprint "eagle-import:0402-B")
      (libsource (lib "eagle-import") (part "C0402-B"))
    )
    (comp (ref "C117")
      (value "C0402-B")
      (footprint "eagle-import:0402-B")
      (libsource (lib "eagle-import") (part "C0402-B"))
    )
    (comp (ref "C118")
      (value "C0402-B")
      (footprint "eagle-import:0402-B")
      (libsource (lib "eagle-import") (part "C0402-B"))
    )
    (comp (ref "C119")
      (value "C0603-B")
      (footprint "eagle-import:0603-B")
      (libsource (lib "eagle-import") (part "C0603-B"))
    )
    (comp (ref "C120")
      (value "C0603-B")
      (footprint "eagle-import:0603-B")
      (libsource (lib "eagle-import") (part "C0603-B"))
    )
    (comp (ref "C121")
      (value "C0402-B")
      (footprint "eagle-import:0402-B")
      (libsource (lib "eagle-import") (part "C0402-B"))
    )
    (comp (ref "C122")
      (value "C0402-B")
      (footprint "eagle-import:0402-B")
      (libsource (lib "eagle-import") (part "C0402-B"))
    )
    (comp (ref "C123")
      (value "C0603-B")
      (footprint "eagle-import:0603-B")
      (libsource (lib "eagle-import") (part "C0603-B"))
    )
    (comp (ref "C124")
      (value "C0603-B")
      (footprint "eagle-import:0603-B")
      (libsource (lib "eagle-import") (part "C0603-B"))
    )
    (comp (ref "ICSP5")
      (value "PINHD-1X04_2.00")
      (footprint "eagle-import:1X04M")
      (libsource (lib "eagle-import") (part "PINHD-1X04_2.00"))
    )
    (comp (ref "ICSP6")
      (value "PINHD-1X04_2.00")
      (footprint "eagle-import:1X04M")
      (libsource (lib "eagle-import") (part "PINHD-1X04_2.00"))
    )
    (comp (ref "L1")
      (value "L0402-B")
      (footprint "eagle-import:0402-B")
      (libsource (lib "eagle-import") (part "L0402-B"))
    )
    (comp (ref "L4")
      (value "L0402-B")
      (footprint "eagle-import:0402-B")
      (libsource (lib "eagle-import") (part "L0402-B"))
    )
    (comp (ref "LED3")
      (value "DUAL-LED-0404")
      (footprint "eagle-import:0404")
      (libsource (lib "eagle-import") (part "DUAL-LED-0404"))
    )
    (comp (ref "LED4")
      (value "DUAL-LED-0404")
      (footprint "eagle-import:0404")
      (libsource (lib "eagle-import") (part "DUAL-LED-0404"))
    )
    (comp (ref "R3")
      (value "R0402-B")
      (footprint "eagle-import:0402-B")
      (libsource (lib "eagle-import") (part "R0402-B"))
    )
    (comp (ref "R4")
      (value "R0402-B")
      (footprint "eagle-import:0402-B")
      (libsource (lib "eagle-import") (part "R0402-B"))
    )
    (comp (ref "R7")
      (value "R0402-B")
      (footprint "eagle-import:0402-B")
      (libsource (lib "eagle-import") (part "R0402-B"))
    )
    (comp (ref "R8")
      (value "R0402-B")
      (footprint "eagle-import:0402-B")
      (libsource (lib "eagle-import") (part "R0402-B"))
    )
    (comp (ref "R17")
      (value "R0402-B")
      (footprint "eagle-import:0402-B")
      (libsource (lib "eagle-import") (part "R0402-B"))
    )
    (comp (ref "R18")
      (value "R0402-B")
      (footprint "eagle-import:0402-B")
      (libsource (lib "eagle-import") (part "R0402-B"))
    )
    (comp (ref "R19")
      (value "R0402-B")
      (footprint "eagle-import:0402-B")
      (libsource (lib "eagle-import") (part "R0402-B"))
    )
    (comp (ref "R20")
      (value "R0402-B")
      (footprint "eagle-import:0402-B")
      (libsource (lib "eagle-import") (part "R0402-B"))
    )
    (comp (ref "SER5")
      (value "PINHD-1X03_2.00")
      (footprint "eagle-import:1X03M")
      (libsource (lib "eagle-import") (part "PINHD-1X03_2.00"))
    )
    (comp (ref "SER6")
      (value "PINHD-1X03_2.00")
      (footprint "eagle-import:1X03M")
      (libsource (lib "eagle-import") (part "PINHD-1X03_2.00"))
    )
    (comp (ref "U5")
      (value "PIC16F1526-I/PT")
      (footprint "eagle-import:QFP50P1200X1200X120-64N")
      (libsource (lib "eagle-import") (part "PIC16F1526-I/PT"))
    )
    (comp (ref "U6")
      (value "PIC16F1526-I/PT")
      (footprint "eagle-import:QFP50P1200X1200X120-64N")
      (libsource (lib "eagle-import") (part "PIC16F1526-I/PT"))
    )
    (comp (ref "C23")
      (value "C0402-B")
      (footprint "eagle-import:0402-B")
      (libsource (lib "eagle-import") (part "C0402-B"))
    )
    (comp (ref "C24")
      (value "C0402-B")
      (footprint "eagle-import:0402-B")
      (libsource (lib "eagle-import") (part "C0402-B"))
    )
    (comp (ref "C25")
      (value "C0402-B")
      (footprint "eagle-import:0402-B")
      (libsource (lib "eagle-import") (part "C0402-B"))
    )
    (comp (ref "C26")
      (value "C0402-B")
      (footprint "eagle-import:0402-B")
      (libsource (lib "eagle-import") (part "C0402-B"))
    )
    (comp (ref "C27")
      (value "C0402-B")
      (footprint "eagle-import:0402-B")
      (libsource (lib "eagle-import") (part "C0402-B"))
    )
    (comp (ref "C28")
      (value "C0402-B")
      (footprint "eagle-import:0402-B")
      (libsource (lib "eagle-import") (part "C0402-B"))
    )
    (comp (ref "C29")
      (value "C0402-B")
      (footprint "eagle-import:0402-B")
      (libsource (lib "eagle-import") (part "C0402-B"))
    )
    (comp (ref "C30")
      (value "C0402-B")
      (footprint "eagle-import:0402-B")
      (libsource (lib "eagle-import") (part "C0402-B"))
    )
    (comp (ref "C31")
      (value "C0402-B")
      (footprint "eagle-import:0402-B")
      (libsource (lib "eagle-import") (part "C0402-B"))
    )
    (comp (ref "C32")
      (value "C0402-B")
      (footprint "eagle-import:0402-B")
      (libsource (lib "eagle-import") (part "C0402-B"))
    )
    (comp (ref "C33")
      (value "C0402-B")
      (footprint "eagle-import:0402-B")
      (libsource (lib "eagle-import") (part "C0402-B"))
    )
    (comp (ref "C34")
      (value "C0402-B")
      (footprint "eagle-import:0402-B")
      (libsource (lib "eagle-import") (part "C0402-B"))
    )
    (comp (ref "C35")
      (value "C0402-B")
      (footprint "eagle-import:0402-B")
      (libsource (lib "eagle-import") (part "C0402-B"))
    )
    (comp (ref "C36")
      (value "C0402-B")
      (footprint "eagle-import:0402-B")
      (libsource (lib "eagle-import") (part "C0402-B"))
    )
    (comp (ref "C37")
      (value "C0402-B")
      (footprint "eagle-import:0402-B")
      (libsource (lib "eagle-import") (part "C0402-B"))
    )
    (comp (ref "C38")
      (value "C0402-B")
      (footprint "eagle-import:0402-B")
      (libsource (lib "eagle-import") (part "C0402-B"))
    )
    (comp (ref "C39")
      (value "C0402-B")
      (footprint "eagle-import:0402-B")
      (libsource (lib "eagle-import") (part "C0402-B"))
    )
    (comp (ref "C40")
      (value "C0402-B")
      (footprint "eagle-import:0402-B")
      (libsource (lib "eagle-import") (part "C0402-B"))
    )
    (comp (ref "C41")
      (value "C0402-B")
      (footprint "eagle-import:0402-B")
      (libsource (lib "eagle-import") (part "C0402-B"))
    )
    (comp (ref "C42")
      (value "C0402-B")
      (footprint "eagle-import:0402-B")
      (libsource (lib "eagle-import") (part "C0402-B"))
    )
    (comp (ref "C43")
      (value "C0402-B")
      (footprint "eagle-import:0402-B")
      (libsource (lib "eagle-import") (part "C0402-B"))
    )
    (comp (ref "C44")
      (value "C0402-B")
      (footprint "eagle-import:0402-B")
      (libsource (lib "eagle-import") (part "C0402-B"))
    )
    (comp (ref "C95")
      (value "C0402-B")
      (footprint "eagle-import:0402-B")
      (libsource (lib "eagle-import") (part "C0402-B"))
    )
    (comp (ref "C96")
      (value "C0402-B")
      (footprint "eagle-import:0402-B")
      (libsource (lib "eagle-import") (part "C0402-B"))
    )
    (comp (ref "C109")
      (value "C0402-B")
      (footprint "eagle-import:0402-B")
      (libsource (lib "eagle-import") (part "C0402-B"))
    )
    (comp (ref "C110")
      (value "C0402-B")
      (footprint "eagle-import:0402-B")
      (libsource (lib "eagle-import") (part "C0402-B"))
    )
    (comp (ref "C111")
      (value "C0603-B")
      (footprint "eagle-import:0603-B")
      (libsource (lib "eagle-import") (part "C0603-B"))
    )
    (comp (ref "C112")
      (value "C0603-B")
      (footprint "eagle-import:0603-B")
      (libsource (lib "eagle-import") (part "C0603-B"))
    )
    (comp (ref "C113")
      (value "C0402-B")
      (footprint "eagle-import:0402-B")
      (libsource (lib "eagle-import") (part "C0402-B"))
    )
    (comp (ref "C114")
      (value "C0402-B")
      (footprint "eagle-import:0402-B")
      (libsource (lib "eagle-import") (part "C0402-B"))
    )
    (comp (ref "C115")
      (value "C0603-B")
      (footprint "eagle-import:0603-B")
      (libsource (lib "eagle-import") (part "C0603-B"))
    )
    (comp (ref "C116")
      (value "C0603-B")
      (footprint "eagle-import:0603-B")
      (libsource (lib "eagle-import") (part "C0603-B"))
    )
    (comp (ref "ICSP3")
      (value "PINHD-1X04_2.00")
      (footprint "eagle-import:1X04M")
      (libsource (lib "eagle-import") (part "PINHD-1X04_2.00"))
    )
    (comp (ref "ICSP4")
      (value "PINHD-1X04_2.00")
      (footprint "eagle-import:1X04M")
      (libsource (lib "eagle-import") (part "PINHD-1X04_2.00"))
    )
    (comp (ref "L5")
      (value "L0402-B")
      (footprint "eagle-import:0402-B")
      (libsource (lib "eagle-import") (part "L0402-B"))
    )
    (comp (ref "L6")
      (value "L0402-B")
      (footprint "eagle-import:0402-B")
      (libsource (lib "eagle-import") (part "L0402-B"))
    )
    (comp (ref "R9")
      (value "R0402-B")
      (footprint "eagle-import:0402-B")
      (libsource (lib "eagle-import") (part "R0402-B"))
    )
    (comp (ref "R10")
      (value "R0402-B")
      (footprint "eagle-import:0402-B")
      (libsource (lib "eagle-import") (part "R0402-B"))
    )
    (comp (ref "SER3")
      (value "PINHD-1X03_2.00")
      (footprint "eagle-import:1X03M")
      (libsource (lib "eagle-import") (part "PINHD-1X03_2.00"))
    )
    (comp (ref "SER4")
      (value "PINHD-1X03_2.00")
      (footprint "eagle-import:1X03M")
      (libsource (lib "eagle-import") (part "PINHD-1X03_2.00"))
    )
    (comp (ref "SPI-WEST")
      (value "PINHD-1X06_2.00")
      (footprint "eagle-import:1X06M")
      (libsource (lib "eagle-import") (part "PINHD-1X06_2.00"))
    )
    (comp (ref "U3")
      (value "PIC16F1526-I/PT")
      (footprint "eagle-import:QFP50P1200X1200X120-64N")
      (libsource (lib "eagle-import") (part "PIC16F1526-I/PT"))
    )
    (comp (ref "U4")
      (value "PIC16F1526-I/PT")
      (footprint "eagle-import:QFP50P1200X1200X120-64N")
      (libsource (lib "eagle-import") (part "PIC16F1526-I/PT"))
    )
  )
  (nets
    (net (code "1") (name "AVCC1") (class "Default")
      (node (ref "C11") (pin "1") (pinfunction "1_1") (pintype "passive"))
      (node (ref "C6") (pin "1") (pinfunction "1_1") (pintype "passive"))
      (node (ref "L8") (pin "2") (pinfunction "2_2") (pintype "passive"))
      (node (ref "U1") (pin "19") (pinfunction "AVDD_19") (pintype "power_in"))
    )
    (net (code "2") (name "AVCC2") (class "Default")
      (node (ref "C17") (pin "1") (pinfunction "1_1") (pintype "passive"))
      (node (ref "C22") (pin "1") (pinfunction "1_1") (pintype "passive"))
      (node (ref "L7") (pin "2") (pinfunction "2_2") (pintype "passive"))
      (node (ref "U2") (pin "19") (pinfunction "AVDD_19") (pintype "power_in"))
    )
    (net (code "3") (name "AVCC3") (class "Default")
      (node (ref "C28") (pin "1") (pinfunction "1_1") (pintype "passive"))
      (node (ref "C33") (pin "1") (pinfunction "1_1") (pintype "passive"))
      (node (ref "L6") (pin "2") (pinfunction "2_2") (pintype "passive"))
      (node (ref "U3") (pin "19") (pinfunction "AVDD_19") (pintype "power_in"))
    )
    (net (code "4") (name "AVCC4") (class "Default")
      (node (ref "C39") (pin "1") (pinfunction "1_1") (pintype "passive"))
      (node (ref "C44") (pin "1") (pinfunction "1_1") (pintype "passive"))
      (node (ref "L5") (pin "2") (pinfunction "2_2") (pintype "passive"))
      (node (ref "U4") (pin "19") (pinfunction "AVDD_19") (pintype "power_in"))
    )
    (net (code "5") (name "AVCC5") (class "Default")
      (node (ref "C50") (pin "1") (pinfunction "1_1") (pintype "passive"))
      (node (ref "C55") (pin "1") (pinfunction "1_1") (pintype "passive"))
      (node (ref "L4") (pin "2") (pinfunction "2_2") (pintype "passive"))
      (node (ref "U5") (pin "19") (pinfunction "AVDD_19") (pintype "power_in"))
    )
    (net (code "6") (name "AVCC6") (class "Default")
      (node (ref "C61") (pin "1") (pinfunction "1_1") (pintype "passive"))
      (node (ref "C66") (pin "1") (pinfunction "1_1") (pintype "passive"))
      (node (ref "L1") (pin "2") (pinfunction "2_2") (pintype "passive"))
      (node (ref "U6") (pin "19") (pinfunction "AVDD_19") (pintype "power_in"))
    )
    (net (code "7") (name "AVCC7") (class "Default")
      (node (ref "C72") (pin "1") (pinfunction "1_1") (pintype "passive"))
      (node (ref "C77") (pin "1") (pinfunction "1_1") (pintype "passive"))
      (node (ref "L2") (pin "2") (pinfunction "2_2") (pintype "passive"))
      (node (ref "U7") (pin "19") (pinfunction "AVDD_19") (pintype "power_in"))
    )
    (net (code "8") (name "AVCC8") (class "Default")
      (node (ref "C83") (pin "1") (pinfunction "1_1") (pintype "passive"))
      (node (ref "C88") (pin "1") (pinfunction "1_1") (pintype "passive"))
      (node (ref "L3") (pin "2") (pinfunction "2_2") (pintype "passive"))
      (node (ref "U8") (pin "19") (pinfunction "AVDD_19") (pintype "power_in"))
    )
    (net (code "9") (name "CAP1A") (class "Default")
      (node (ref "C101") (pin "1") (pinfunction "1_1") (pintype "passive"))
      (node (ref "U1") (pin "24") (pinfunction "RA0/AN0_24") (pintype "bidirectional"))
    )
    (net (code "10") (name "CAP1B") (class "Default")
      (node (ref "C102") (pin "1") (pinfunction "1_1") (pintype "passive"))
      (node (ref "U1") (pin "23") (pinfunction "RA1/AN1_23") (pintype "bidirectional"))
    )
    (net (code "11") (name "CAP1C") (class "Default")
      (node (ref "C103") (pin "1") (pinfunction "1_1") (pintype "passive"))
      (node (ref "U1") (pin "22") (pinfunction "RA2/AN2_22") (pintype "bidirectional"))
    )
    (net (code "12") (name "CAP1D") (class "Default")
      (node (ref "C104") (pin "1") (pinfunction "1_1") (pintype "passive"))
      (node (ref "U1") (pin "21") (pinfunction "RA3/AN3/REF+_21") (pintype "bidirectional"))
    )
    (net (code "13") (name "CAP2A") (class "Default")
      (node (ref "C105") (pin "1") (pinfunction "1_1") (pintype "passive"))
      (node (ref "U2") (pin "58") (pinfunction "AN23/RD0_58") (pintype "bidirectional"))
    )
    (net (code "14") (name "CAP2B") (class "Default")
      (node (ref "C106") (pin "1") (pinfunction "1_1") (pintype "passive"))
      (node (ref "U2") (pin "55") (pinfunction "AN24/RD1_55") (pintype "bidirectional"))
    )
    (net (code "15") (name "CAP2C") (class "Default")
      (node (ref "C107") (pin "1") (pinfunction "1_1") (pintype "passive"))
      (node (ref "U2") (pin "54") (pinfunction "AN25/RD2_54") (pintype "bidirectional"))
    )
    (net (code "16") (name "CAP2D") (class "Default")
      (node (ref "C108") (pin "1") (pinfunction "1_1") (pintype "passive"))
      (node (ref "U2") (pin "53") (pinfunction "AN26/RD3_53") (pintype "bidirectional"))
    )
    (net (code "17") (name "CAP3A") (class "Default")
      (node (ref "C109") (pin "1") (pinfunction "1_1") (pintype "passive"))
      (node (ref "U3") (pin "24") (pinfunction "RA0/AN0_24") (pintype "bidirectional"))
    )
    (net (code "18") (name "CAP3B") (class "Default")
      (node (ref "C110") (pin "1") (pinfunction "1_1") (pintype "passive"))
      (node (ref "U3") (pin "23") (pinfunction "RA1/AN1_23") (pintype "bidirectional"))
    )
    (net (code "19") (name "CAP3C") (class "Default")
      (node (ref "C111") (pin "1") (pinfunction "1_1") (pintype "passive"))
      (node (ref "U3") (pin "22") (pinfunction "RA2/AN2_22") (pintype "bidirectional"))
    )
    (net (code "20") (name "CAP3D") (class "Default")
      (node (ref "C112") (pin "1") (pinfunction "1_1") (pintype "passive"))
      (node (ref "U3") (pin "21") (pinfunction "RA3/AN3/REF+_21") (pintype "bidirectional"))
    )
    (net (code "21") (name "CAP4A") (class "Default")
      (node (ref "C113") (pin "1") (pinfunction "1_1") (pintype "passive"))
      (node (ref "U4") (pin "58") (pinfunction "AN23/RD0_58") (pintype "bidirectional"))
    )
    (net (code "22") (name "CAP4B") (class "Default")
      (node (ref "C114") (pin "1") (pinfunction "1_1") (pintype "passive"))
      (node (ref "U4") (pin "55") (pinfunction "AN24/RD1_55") (pintype "bidirectional"))
    )
    (net (code "23") (name "CAP4C") (class "Default")
      (node (ref "C115") (pin "1") (pinfunction "1_1") (pintype "passive"))
      (node (ref "U4") (pin "54") (pinfunction "AN25/RD2_54") (pintype "bidirectional"))
    )
    (net (code "24") (name "CAP4D") (class "Default")
      (node (ref "C116") (pin "1") (pinfunction "1_1") (pintype "passive"))
      (node (ref "U4") (pin "53") (pinfunction "AN26/RD3_53") (pintype "bidirectional"))
    )
    (net (code "25") (name "CAP5A") (class "Default")
      (node (ref "C117") (pin "1") (pinfunction "1_1") (pintype "passive"))
      (node (ref "U5") (pin "24") (pinfunction "RA0/AN0_24") (pintype "bidirectional"))
    )
    (net (code "26") (name "CAP5B") (class "Default")
      (node (ref "C118") (pin "1") (pinfunction "1_1") (pintype "passive"))
      (node (ref "U5") (pin "23") (pinfunction "RA1/AN1_23") (pintype "bidirectional"))
    )
    (net (code "27") (name "CAP5C") (class "Default")
      (node (ref "C119") (pin "1") (pinfunction "1_1") (pintype "passive"))
      (node (ref "U5") (pin "22") (pinfunction "RA2/AN2_22") (pintype "bidirectional"))
    )
    (net (code "28") (name "CAP5D") (class "Default")
      (node (ref "C120") (pin "1") (pinfunction "1_1") (pintype "passive"))
      (node (ref "U5") (pin "21") (pinfunction "RA3/AN3/REF+_21") (pintype "bidirectional"))
    )
    (net (code "29") (name "CAP6A") (class "Default")
      (node (ref "C121") (pin "1") (pinfunction "1_1") (pintype "passive"))
      (node (ref "U6") (pin "58") (pinfunction "AN23/RD0_58") (pintype "bidirectional"))
    )
    (net (code "30") (name "CAP6B") (class "Default")
      (node (ref "C122") (pin "1") (pinfunction "1_1") (pintype "passive"))
      (node (ref "U6") (pin "55") (pinfunction "AN24/RD1_55") (pintype "bidirectional"))
    )
    (net (code "31") (name "CAP6C") (class "Default")
      (node (ref "C123") (pin "1") (pinfunction "1_1") (pintype "passive"))
      (node (ref "U6") (pin "54") (pinfunction "AN25/RD2_54") (pintype "bidirectional"))
    )
    (net (code "32") (name "CAP6D") (class "Default")
      (node (ref "C124") (pin "1") (pinfunction "1_1") (pintype "passive"))
      (node (ref "U6") (pin "53") (pinfunction "AN26/RD3_53") (pintype "bidirectional"))
    )
    (net (code "33") (name "CAP7A") (class "Default")
      (node (ref "C125") (pin "1") (pinfunction "1_1") (pintype "passive"))
      (node (ref "U7") (pin "58") (pinfunction "AN23/RD0_58") (pintype "bidirectional"))
    )
    (net (code "34") (name "CAP7B") (class "Default")
      (node (ref "C126") (pin "1") (pinfunction "1_1") (pintype "passive"))
      (node (ref "U7") (pin "55") (pinfunction "AN24/RD1_55") (pintype "bidirectional"))
    )
    (net (code "35") (name "CAP7C") (class "Default")
      (node (ref "C127") (pin "1") (pinfunction "1_1") (pintype "passive"))
      (node (ref "U7") (pin "54") (pinfunction "AN25/RD2_54") (pintype "bidirectional"))
    )
    (net (code "36") (name "CAP7D") (class "Default")
      (node (ref "C128") (pin "1") (pinfunction "1_1") (pintype "passive"))
      (node (ref "U7") (pin "53") (pinfunction "AN26/RD3_53") (pintype "bidirectional"))
    )
    (net (code "37") (name "CAP8A") (class "Default")
      (node (ref "C129") (pin "1") (pinfunction "1_1") (pintype "passive"))
      (node (ref "U8") (pin "24") (pinfunction "RA0/AN0_24") (pintype "bidirectional"))
    )
    (net (code "38") (name "CAP8B") (class "Default")
      (node (ref "C130") (pin "1") (pinfunction "1_1") (pintype "passive"))
      (node (ref "U8") (pin "23") (pinfunction "RA1/AN1_23") (pintype "bidirectional"))
    )
    (net (code "39") (name "CAP8C") (class "Default")
      (node (ref "C131") (pin "1") (pinfunction "1_1") (pintype "passive"))
      (node (ref "U8") (pin "22") (pinfunction "RA2/AN2_22") (pintype "bidirectional"))
    )
    (net (code "40") (name "CAP8D") (class "Default")
      (node (ref "C132") (pin "1") (pinfunction "1_1") (pintype "passive"))
      (node (ref "U8") (pin "21") (pinfunction "RA3/AN3/REF+_21") (pintype "bidirectional"))
    )
    (net (code "41") (name "CLKIN1") (class "Default")
      (node (ref "U1") (pin "39") (pinfunction "RA7_39") (pintype "bidirectional"))
      (node (ref "U9") (pin "8") (pinfunction "Q6_8") (pintype "output"))
    )
    (net (code "42") (name "CLKIN2") (class "Default")
      (node (ref "U2") (pin "39") (pinfunction "RA7_39") (pintype "bidirectional"))
      (node (ref "U9") (pin "16") (pinfunction "Q1_16") (pintype "output"))
    )
    (net (code "43") (name "CLKIN3") (class "Default")
      (node (ref "U3") (pin "39") (pinfunction "RA7_39") (pintype "bidirectional"))
      (node (ref "U9") (pin "15") (pinfunction "Q3_15") (pintype "output"))
    )
    (net (code "44") (name "CLKIN4") (class "Default")
      (node (ref "U4") (pin "39") (pinfunction "RA7_39") (pintype "bidirectional"))
      (node (ref "U9") (pin "9") (pinfunction "Q7_9") (pintype "output"))
    )
    (net (code "45") (name "CLKIN5") (class "Default")
      (node (ref "U5") (pin "39") (pinfunction "RA7_39") (pintype "bidirectional"))
      (node (ref "U9") (pin "3") (pinfunction "Q0_3") (pintype "output"))
    )
    (net (code "46") (name "CLKIN6") (class "Default")
      (node (ref "U6") (pin "39") (pinfunction "RA7_39") (pintype "bidirectional"))
      (node (ref "U9") (pin "13") (pinfunction "Q2_13") (pintype "output"))
    )
    (net (code "47") (name "CLKIN7") (class "Default")
      (node (ref "U7") (pin "39") (pinfunction "RA7_39") (pintype "bidirectional"))
      (node (ref "U9") (pin "6") (pinfunction "Q4_6") (pintype "output"))
    )
    (net (code "48") (name "CLKIN8") (class "Default")
      (node (ref "U8") (pin "39") (pinfunction "RA7_39") (pintype "bidirectional"))
      (node (ref "U9") (pin "11") (pinfunction "Q5_11") (pintype "output"))
    )
    (net (code "49") (name "E_SCK") (class "Default")
      (node (ref "U1") (pin "34") (pinfunction "RC3/SCK1_34") (pintype "bidirectional"))
      (node (ref "U2") (pin "34") (pinfunction "RC3/SCK1_34") (pintype "bidirectional"))
      (node (ref "U5") (pin "34") (pinfunction "RC3/SCK1_34") (pintype "bidirectional"))
      (node (ref "U7") (pin "34") (pinfunction "RC3/SCK1_34") (pintype "bidirectional"))
    )
    (net (code "50") (name "E_SD_17") (class "Default")
      (node (ref "U1") (pin "36") (pinfunction "RC5/SDO1_36") (pintype "bidirectional"))
      (node (ref "U7") (pin "35") (pinfunction "RC4/SDI1_35") (pintype "bidirectional"))
    )
    (net (code "51") (name "E_SD_21") (class "Default")
      (node (ref "U1") (pin "35") (pinfunction "RC4/SDI1_35") (pintype "bidirectional"))
      (node (ref "U2") (pin "36") (pinfunction "RC5/SDO1_36") (pintype "bidirectional"))
    )
    (net (code "52") (name "E_SD_52") (class "Default")
      (node (ref "U2") (pin "35") (pinfunction "RC4/SDI1_35") (pintype "bidirectional"))
      (node (ref "U5") (pin "36") (pinfunction "RC5/SDO1_36") (pintype "bidirectional"))
    )
    (net (code "53") (name "E_SD_75") (class "Default")
      (node (ref "U5") (pin "35") (pinfunction "RC4/SDI1_35") (pintype "bidirectional"))
      (node (ref "U7") (pin "36") (pinfunction "RC5/SDO1_36") (pintype "bidirectional"))
    )
    (net (code "54") (name "GND") (class "Default")
      (node (ref "C1") (pin "2") (pinfunction "2_2") (pintype "passive"))
      (node (ref "C10") (pin "2") (pinfunction "2_2") (pintype "passive"))
      (node (ref "C100") (pin "2") (pinfunction "2_2") (pintype "passive"))
      (node (ref "C101") (pin "2") (pinfunction "2_2") (pintype "passive"))
      (node (ref "C102") (pin "2") (pinfunction "2_2") (pintype "passive"))
      (node (ref "C103") (pin "2") (pinfunction "2_2") (pintype "passive"))
      (node (ref "C104") (pin "2") (pinfunction "2_2") (pintype "passive"))
      (node (ref "C105") (pin "2") (pinfunction "2_2") (pintype "passive"))
      (node (ref "C106") (pin "2") (pinfunction "2_2") (pintype "passive"))
      (node (ref "C107") (pin "2") (pinfunction "2_2") (pintype "passive"))
      (node (ref "C108") (pin "2") (pinfunction "2_2") (pintype "passive"))
      (node (ref "C109") (pin "2") (pinfunction "2_2") (pintype "passive"))
      (node (ref "C11") (pin "2") (pinfunction "2_2") (pintype "passive"))
      (node (ref "C110") (pin "2") (pinfunction "2_2") (pintype "passive"))
      (node (ref "C111") (pin "2") (pinfunction "2_2") (pintype "passive"))
      (node (ref "C112") (pin "2") (pinfunction "2_2") (pintype "passive"))
      (node (ref "C113") (pin "2") (pinfunction "2_2") (pintype "passive"))
      (node (ref "C114") (pin "2") (pinfunction "2_2") (pintype "passive"))
      (node (ref "C115") (pin "2") (pinfunction "2_2") (pintype "passive"))
      (node (ref "C116") (pin "2") (pinfunction "2_2") (pintype "passive"))
      (node (ref "C117") (pin "2") (pinfunction "2_2") (pintype "passive"))
      (node (ref "C118") (pin "2") (pinfunction "2_2") (pintype "passive"))
      (node (ref "C119") (pin "2") (pinfunction "2_2") (pintype "passive"))
      (node (ref "C12") (pin "2") (pinfunction "2_2") (pintype "passive"))
      (node (ref "C120") (pin "2") (pinfunction "2_2") (pintype "passive"))
      (node (ref "C121") (pin "2") (pinfunction "2_2") (pintype "passive"))
      (node (ref "C122") (pin "2") (pinfunction "2_2") (pintype "passive"))
      (node (ref "C123") (pin "2") (pinfunction "2_2") (pintype "passive"))
      (node (ref "C124") (pin "2") (pinfunction "2_2") (pintype "passive"))
      (node (ref "C125") (pin "2") (pinfunction "2_2") (pintype "passive"))
      (node (ref "C126") (pin "2") (pinfunction "2_2") (pintype "passive"))
      (node (ref "C127") (pin "2") (pinfunction "2_2") (pintype "passive"))
      (node (ref "C128") (pin "2") (pinfunction "2_2") (pintype "passive"))
      (node (ref "C129") (pin "2") (pinfunction "2_2") (pintype "passive"))
      (node (ref "C13") (pin "2") (pinfunction "2_2") (pintype "passive"))
      (node (ref "C130") (pin "2") (pinfunction "2_2") (pintype "passive"))
      (node (ref "C131") (pin "2") (pinfunction "2_2") (pintype "passive"))
      (node (ref "C132") (pin "2") (pinfunction "2_2") (pintype "passive"))
      (node (ref "C133") (pin "2") (pinfunction "2_2") (pintype "passive"))
      (node (ref "C134") (pin "2") (pinfunction "2_2") (pintype "passive"))
      (node (ref "C135") (pin "2") (pinfunction "2_2") (pintype "passive"))
      (node (ref "C136") (pin "2") (pinfunction "2_2") (pintype "passive"))
      (node (ref "C137") (pin "2") (pinfunction "2_2") (pintype "passive"))
      (node (ref "C138") (pin "2") (pinfunction "2_2") (pintype "passive"))
      (node (ref "C139") (pin "2") (pinfunction "2_2") (pintype "passive"))
      (node (ref "C14") (pin "2") (pinfunction "2_2") (pintype "passive"))
      (node (ref "C140") (pin "2") (pinfunction "2_2") (pintype "passive"))
      (node (ref "C141") (pin "2") (pinfunction "2_2") (pintype "passive"))
      (node (ref "C142") (pin "2") (pinfunction "2_2") (pintype "passive"))
      (node (ref "C143") (pin "2") (pinfunction "2_2") (pintype "passive"))
      (node (ref "C144") (pin "2") (pinfunction "2_2") (pintype "passive"))
      (node (ref "C15") (pin "2") (pinfunction "2_2") (pintype "passive"))
      (node (ref "C16") (pin "2") (pinfunction "2_2") (pintype "passive"))
      (node (ref "C17") (pin "2") (pinfunction "2_2") (pintype "passive"))
      (node (ref "C18") (pin "2") (pinfunction "2_2") (pintype "passive"))
      (node (ref "C19") (pin "2") (pinfunction "2_2") (pintype "passive"))
      (node (ref "C2") (pin "2") (pinfunction "2_2") (pintype "passive"))
      (node (ref "C20") (pin "2") (pinfunction "2_2") (pintype "passive"))
      (node (ref "C21") (pin "2") (pinfunction "2_2") (pintype "passive"))
      (node (ref "C22") (pin "2") (pinfunction "2_2") (pintype "passive"))
      (node (ref "C23") (pin "2") (pinfunction "2_2") (pintype "passive"))
      (node (ref "C24") (pin "2") (pinfunction "2_2") (pintype "passive"))
      (node (ref "C25") (pin "2") (pinfunction "2_2") (pintype "passive"))
      (node (ref "C26") (pin "2") (pinfunction "2_2") (pintype "passive"))
      (node (ref "C27") (pin "2") (pinfunction "2_2") (pintype "passive"))
      (node (ref "C28") (pin "2") (pinfunction "2_2") (pintype "passive"))
      (node (ref "C29") (pin "2") (pinfunction "2_2") (pintype "passive"))
      (node (ref "C3") (pin "2") (pinfunction "2_2") (pintype "passive"))
      (node (ref "C30") (pin "2") (pinfunction "2_2") (pintype "passive"))
      (node (ref "C31") (pin "2") (pinfunction "2_2") (pintype "passive"))
      (node (ref "C32") (pin "2") (pinfunction "2_2") (pintype "passive"))
      (node (ref "C33") (pin "2") (pinfunction "2_2") (pintype "passive"))
      (node (ref "C34") (pin "2") (pinfunction "2_2") (pintype "passive"))
      (node (ref "C35") (pin "2") (pinfunction "2_2") (pintype "passive"))
      (node (ref "C36") (pin "2") (pinfunction "2_2") (pintype "passive"))
      (node (ref "C37") (pin "2") (pinfunction "2_2") (pintype "passive"))
      (node (ref "C38") (pin "2") (pinfunction "2_2") (pintype "passive"))
      (node (ref "C39") (pin "2") (pinfunction "2_2") (pintype "passive"))
      (node (ref "C4") (pin "2") (pinfunction "2_2") (pintype "passive"))
      (node (ref "C40") (pin "2") (pinfunction "2_2") (pintype "passive"))
      (node (ref "C41") (pin "2") (pinfunction "2_2") (pintype "passive"))
      (node (ref "C42") (pin "2") (pinfunction "2_2") (pintype "passive"))
      (node (ref "C43") (pin "2") (pinfunction "2_2") (pintype "passive"))
      (node (ref "C44") (pin "2") (pinfunction "2_2") (pintype "passive"))
      (node (ref "C45") (pin "2") (pinfunction "2_2") (pintype "passive"))
      (node (ref "C46") (pin "2") (pinfunction "2_2") (pintype "passive"))
      (node (ref "C47") (pin "2") (pinfunction "2_2") (pintype "passive"))
      (node (ref "C48") (pin "2") (pinfunction "2_2") (pintype "passive"))
      (node (ref "C49") (pin "2") (pinfunction "2_2") (pintype "passive"))
      (node (ref "C5") (pin "2") (pinfunction "2_2") (pintype "passive"))
      (node (ref "C50") (pin "2") (pinfunction "2_2") (pintype "passive"))
      (node (ref "C51") (pin "2") (pinfunction "2_2") (pintype "passive"))
      (node (ref "C52") (pin "2") (pinfunction "2_2") (pintype "passive"))
      (node (ref "C53") (pin "2") (pinfunction "2_2") (pintype "passive"))
      (node (ref "C54") (pin "2") (pinfunction "2_2") (pintype "passive"))
      (node (ref "C55") (pin "2") (pinfunction "2_2") (pintype "passive"))
      (node (ref "C56") (pin "2") (pinfunction "2_2") (pintype "passive"))
      (node (ref "C57") (pin "2") (pinfunction "2_2") (pintype "passive"))
      (node (ref "C58") (pin "2") (pinfunction "2_2") (pintype "passive"))
      (node (ref "C59") (pin "2") (pinfunction "2_2") (pintype "passive"))
      (node (ref "C6") (pin "2") (pinfunction "2_2") (pintype "passive"))
      (node (ref "C60") (pin "2") (pinfunction "2_2") (pintype "passive"))
      (node (ref "C61") (pin "2") (pinfunction "2_2") (pintype "passive"))
      (node (ref "C62") (pin "2") (pinfunction "2_2") (pintype "passive"))
      (node (ref "C63") (pin "2") (pinfunction "2_2") (pintype "passive"))
      (node (ref "C64") (pin "2") (pinfunction "2_2") (pintype "passive"))
      (node (ref "C65") (pin "2") (pinfunction "2_2") (pintype "passive"))
      (node (ref "C66") (pin "2") (pinfunction "2_2") (pintype "passive"))
      (node (ref "C67") (pin "2") (pinfunction "2_2") (pintype "passive"))
      (node (ref "C68") (pin "2") (pinfunction "2_2") (pintype "passive"))
      (node (ref "C69") (pin "2") (pinfunction "2_2") (pintype "passive"))
      (node (ref "C7") (pin "2") (pinfunction "2_2") (pintype "passive"))
      (node (ref "C70") (pin "2") (pinfunction "2_2") (pintype "passive"))
      (node (ref "C71") (pin "2") (pinfunction "2_2") (pintype "passive"))
      (node (ref "C72") (pin "2") (pinfunction "2_2") (pintype "passive"))
      (node (ref "C73") (pin "2") (pinfunction "2_2") (pintype "passive"))
      (node (ref "C74") (pin "2") (pinfunction "2_2") (pintype "passive"))
      (node (ref "C75") (pin "2") (pinfunction "2_2") (pintype "passive"))
      (node (ref "C76") (pin "2") (pinfunction "2_2") (pintype "passive"))
      (node (ref "C77") (pin "2") (pinfunction "2_2") (pintype "passive"))
      (node (ref "C78") (pin "2") (pinfunction "2_2") (pintype "passive"))
      (node (ref "C79") (pin "2") (pinfunction "2_2") (pintype "passive"))
      (node (ref "C8") (pin "2") (pinfunction "2_2") (pintype "passive"))
      (node (ref "C80") (pin "2") (pinfunction "2_2") (pintype "passive"))
      (node (ref "C81") (pin "2") (pinfunction "2_2") (pintype "passive"))
      (node (ref "C82") (pin "2") (pinfunction "2_2") (pintype "passive"))
      (node (ref "C83") (pin "2") (pinfunction "2_2") (pintype "passive"))
      (node (ref "C84") (pin "2") (pinfunction "2_2") (pintype "passive"))
      (node (ref "C85") (pin "2") (pinfunction "2_2") (pintype "passive"))
      (node (ref "C86") (pin "2") (pinfunction "2_2") (pintype "passive"))
      (node (ref "C87") (pin "2") (pinfunction "2_2") (pintype "passive"))
      (node (ref "C88") (pin "2") (pinfunction "2_2") (pintype "passive"))
      (node (ref "C89") (pin "2") (pinfunction "2_2") (pintype "passive"))
      (node (ref "C9") (pin "2") (pinfunction "2_2") (pintype "passive"))
      (node (ref "C90") (pin "2") (pinfunction "2_2") (pintype "passive"))
      (node (ref "C91") (pin "2") (pinfunction "2_2") (pintype "passive"))
      (node (ref "C92") (pin "2") (pinfunction "2_2") (pintype "passive"))
      (node (ref "C93") (pin "2") (pinfunction "2_2") (pintype "passive"))
      (node (ref "C94") (pin "2") (pinfunction "2_2") (pintype "passive"))
      (node (ref "C95") (pin "2") (pinfunction "2_2") (pintype "passive"))
      (node (ref "C96") (pin "2") (pinfunction "2_2") (pintype "passive"))
      (node (ref "C97") (pin "2") (pinfunction "2_2") (pintype "passive"))
      (node (ref "C98") (pin "2") (pinfunction "2_2") (pintype "passive"))
      (node (ref "C99") (pin "2") (pinfunction "2_2") (pintype "passive"))
      (node (ref "ICSP1") (pin "1") (pinfunction "1_1") (pintype "passive"))
      (node (ref "ICSP2") (pin "1") (pinfunction "1_1") (pintype "passive"))
      (node (ref "ICSP3") (pin "1") (pinfunction "1_1") (pintype "passive"))
      (node (ref "ICSP4") (pin "1") (pinfunction "1_1") (pintype "passive"))
      (node (ref "ICSP5") (pin "1") (pinfunction "1_1") (pintype "passive"))
      (node (ref "ICSP6") (pin "1") (pinfunction "1_1") (pintype "passive"))
      (node (ref "ICSP7") (pin "1") (pinfunction "1_1") (pintype "passive"))
      (node (ref "ICSP8") (pin "1") (pinfunction "1_1") (pintype "passive"))
      (node (ref "PWR-NORTH") (pin "1") (pinfunction "1_1") (pintype "passive"))
      (node (ref "PWR-NORTH") (pin "3") (pinfunction "3_3") (pintype "passive"))
      (node (ref "PWR-NORTH") (pin "5") (pinfunction "5_5") (pintype "passive"))
      (node (ref "PWR-SOUTH") (pin "1") (pinfunction "1_1") (pintype "passive"))
      (node (ref "PWR-SOUTH") (pin "3") (pinfunction "3_3") (pintype "passive"))
      (node (ref "PWR-SOUTH") (pin "5") (pinfunction "5_5") (pintype "passive"))
      (node (ref "PWRN") (pin "1") (pinfunction "1_1") (pintype "passive"))
      (node (ref "PWRS") (pin "1") (pinfunction "1_1") (pintype "passive"))
      (node (ref "SER1") (pin "1") (pinfunction "1_1") (pintype "passive"))
      (node (ref "SER2") (pin "1") (pinfunction "1_1") (pintype "passive"))
      (node (ref "SER3") (pin "1") (pinfunction "1_1") (pintype "passive"))
      (node (ref "SER4") (pin "1") (pinfunction "1_1") (pintype "passive"))
      (node (ref "SER5") (pin "1") (pinfunction "1_1") (pintype "passive"))
      (node (ref "SER6") (pin "1") (pinfunction "1_1") (pintype "passive"))
      (node (ref "SER7") (pin "1") (pinfunction "1_1") (pintype "passive"))
      (node (ref "SER8") (pin "1") (pinfunction "1_1") (pintype "passive"))
      (node (ref "SPI-EAST") (pin "1") (pinfunction "1_1") (pintype "passive"))
      (node (ref "SPI-WEST") (pin "1") (pinfunction "1_1") (pintype "passive"))
      (node (ref "SUP-N") (pin "1") (pinfunction "1_1") (pintype "passive"))
      (node (ref "SUP-S") (pin "1") (pinfunction "1_1") (pintype "passive"))
      (node (ref "U1") (pin "20") (pinfunction "AVSS_20") (pintype "power_in"))
      (node (ref "U1") (pin "25") (pinfunction "VSS_25") (pintype "power_in"))
      (node (ref "U1") (pin "41") (pinfunction "VSS_41") (pintype "power_in"))
      (node (ref "U1") (pin "56") (pinfunction "VSS_56") (pintype "power_in"))
      (node (ref "U1") (pin "9") (pinfunction "VSS_9") (pintype "power_in"))
      (node (ref "U10") (pin "2") (pinfunction "GND_2") (pintype "bidirectional"))
      (node (ref "U11") (pin "10") (pinfunction "VSS_10") (pintype "power_in"))
      (node (ref "U12") (pin "10") (pinfunction "VSS_10") (pintype "power_in"))
      (node (ref "U2") (pin "20") (pinfunction "AVSS_20") (pintype "power_in"))
      (node (ref "U2") (pin "25") (pinfunction "VSS_25") (pintype "power_in"))
      (node (ref "U2") (pin "41") (pinfunction "VSS_41") (pintype "power_in"))
      (node (ref "U2") (pin "56") (pinfunction "VSS_56") (pintype "power_in"))
      (node (ref "U2") (pin "9") (pinfunction "VSS_9") (pintype "power_in"))
      (node (ref "U3") (pin "20") (pinfunction "AVSS_20") (pintype "power_in"))
      (node (ref "U3") (pin "25") (pinfunction "VSS_25") (pintype "power_in"))
      (node (ref "U3") (pin "41") (pinfunction "VSS_41") (pintype "power_in"))
      (node (ref "U3") (pin "56") (pinfunction "VSS_56") (pintype "power_in"))
      (node (ref "U3") (pin "9") (pinfunction "VSS_9") (pintype "power_in"))
      (node (ref "U4") (pin "20") (pinfunction "AVSS_20") (pintype "power_in"))
      (node (ref "U4") (pin "25") (pinfunction "VSS_25") (pintype "power_in"))
      (node (ref "U4") (pin "41") (pinfunction "VSS_41") (pintype "power_in"))
      (node (ref "U4") (pin "56") (pinfunction "VSS_56") (pintype "power_in"))
      (node (ref "U4") (pin "9") (pinfunction "VSS_9") (pintype "power_in"))
      (node (ref "U5") (pin "20") (pinfunction "AVSS_20") (pintype "power_in"))
      (node (ref "U5") (pin "25") (pinfunction "VSS_25") (pintype "power_in"))
      (node (ref "U5") (pin "41") (pinfunction "VSS_41") (pintype "power_in"))
      (node (ref "U5") (pin "56") (pinfunction "VSS_56") (pintype "power_in"))
      (node (ref "U5") (pin "9") (pinfunction "VSS_9") (pintype "power_in"))
      (node (ref "U6") (pin "20") (pinfunction "AVSS_20") (pintype "power_in"))
      (node (ref "U6") (pin "25") (pinfunction "VSS_25") (pintype "power_in"))
      (node (ref "U6") (pin "41") (pinfunction "VSS_41") (pintype "power_in"))
      (node (ref "U6") (pin "56") (pinfunction "VSS_56") (pintype "power_in"))
      (node (ref "U6") (pin "9") (pinfunction "VSS_9") (pintype "power_in"))
      (node (ref "U7") (pin "20") (pinfunction "AVSS_20") (pintype "power_in"))
      (node (ref "U7") (pin "25") (pinfunction "VSS_25") (pintype "power_in"))
      (node (ref "U7") (pin "41") (pinfunction "VSS_41") (pintype "power_in"))
      (node (ref "U7") (pin "56") (pinfunction "VSS_56") (pintype "power_in"))
      (node (ref "U7") (pin "63") (pinfunction "RE3_63") (pintype "bidirectional"))
      (node (ref "U7") (pin "9") (pinfunction "VSS_9") (pintype "power_in"))
      (node (ref "U8") (pin "20") (pinfunction "AVSS_20") (pintype "power_in"))
      (node (ref "U8") (pin "25") (pinfunction "VSS_25") (pintype "power_in"))
      (node (ref "U8") (pin "41") (pinfunction "VSS_41") (pintype "power_in"))
      (node (ref "U8") (pin "56") (pinfunction "VSS_56") (pintype "power_in"))
      (node (ref "U8") (pin "9") (pinfunction "VSS_9") (pintype "power_in"))
      (node (ref "U9") (pin "12") (pinfunction "GND_12") (pintype "passive"))
      (node (ref "U9") (pin "4") (pinfunction "GND_4") (pintype "passive"))
      (node (ref "U9") (pin "7") (pinfunction "GND_7") (pintype "passive"))
      (node (ref "X-NORTH") (pin "102") (pinfunction "102_102") (pintype "bidirectional"))
      (node (ref "X-NORTH") (pin "103") (pinfunction "103_103") (pintype "bidirectional"))
      (node (ref "X-NORTH") (pin "108") (pinfunction "108_108") (pintype "bidirectional"))
      (node (ref "X-NORTH") (pin "114") (pinfunction "114_114") (pintype "bidirectional"))
      (node (ref "X-NORTH") (pin "12") (pinfunction "12_12") (pintype "bidirectional"))
      (node (ref "X-NORTH") (pin "120") (pinfunction "120_120") (pintype "bidirectional"))
      (node (ref "X-NORTH") (pin "126") (pinfunction "126_126") (pintype "bidirectional"))
      (node (ref "X-NORTH") (pin "132") (pinfunction "132_132") (pintype "bidirectional"))
      (node (ref "X-NORTH") (pin "138") (pinfunction "138_138") (pintype "bidirectional"))
      (node (ref "X-NORTH") (pin "139") (pinfunction "139_139") (pintype "bidirectional"))
      (node (ref "X-NORTH") (pin "18") (pinfunction "18_18") (pintype "bidirectional"))
      (node (ref "X-NORTH") (pin "24") (pinfunction "24_24") (pintype "bidirectional"))
      (node (ref "X-NORTH") (pin "30") (pinfunction "30_30") (pintype "bidirectional"))
      (node (ref "X-NORTH") (pin "36") (pinfunction "36_36") (pintype "bidirectional"))
      (node (ref "X-NORTH") (pin "42") (pinfunction "42_42") (pintype "bidirectional"))
      (node (ref "X-NORTH") (pin "43") (pinfunction "43_43") (pintype "bidirectional"))
      (node (ref "X-NORTH") (pin "48") (pinfunction "48_48") (pintype "bidirectional"))
      (node (ref "X-NORTH") (pin "54") (pinfunction "54_54") (pintype "bidirectional"))
      (node (ref "X-NORTH") (pin "60") (pinfunction "60_60") (pintype "bidirectional"))
      (node (ref "X-NORTH") (pin "66") (pinfunction "66_66") (pintype "bidirectional"))
      (node (ref "X-NORTH") (pin "72") (pinfunction "72_72") (pintype "bidirectional"))
      (node (ref "X-NORTH") (pin "78") (pinfunction "78_78") (pintype "bidirectional"))
      (node (ref "X-NORTH") (pin "84") (pinfunction "84_84") (pintype "bidirectional"))
      (node (ref "X-NORTH") (pin "90") (pinfunction "90_90") (pintype "bidirectional"))
      (node (ref "X-NORTH") (pin "96") (pinfunction "96_96") (pintype "bidirectional"))
      (node (ref "X-SOUTH") (pin "102") (pinfunction "102_102") (pintype "bidirectional"))
      (node (ref "X-SOUTH") (pin "103") (pinfunction "103_103") (pintype "bidirectional"))
      (node (ref "X-SOUTH") (pin "108") (pinfunction "108_108") (pintype "bidirectional"))
      (node (ref "X-SOUTH") (pin "114") (pinfunction "114_114") (pintype "bidirectional"))
      (node (ref "X-SOUTH") (pin "12") (pinfunction "12_12") (pintype "bidirectional"))
      (node (ref "X-SOUTH") (pin "120") (pinfunction "120_120") (pintype "bidirectional"))
      (node (ref "X-SOUTH") (pin "126") (pinfunction "126_126") (pintype "bidirectional"))
      (node (ref "X-SOUTH") (pin "132") (pinfunction "132_132") (pintype "bidirectional"))
      (node (ref "X-SOUTH") (pin "138") (pinfunction "138_138") (pintype "bidirectional"))
      (node (ref "X-SOUTH") (pin "139") (pinfunction "139_139") (pintype "bidirectional"))
      (node (ref "X-SOUTH") (pin "18") (pinfunction "18_18") (pintype "bidirectional"))
      (node (ref "X-SOUTH") (pin "24") (pinfunction "24_24") (pintype "bidirectional"))
      (node (ref "X-SOUTH") (pin "30") (pinfunction "30_30") (pintype "bidirectional"))
      (node (ref "X-SOUTH") (pin "36") (pinfunction "36_36") (pintype "bidirectional"))
      (node (ref "X-SOUTH") (pin "42") (pinfunction "42_42") (pintype "bidirectional"))
      (node (ref "X-SOUTH") (pin "43") (pinfunction "43_43") (pintype "bidirectional"))
      (node (ref "X-SOUTH") (pin "48") (pinfunction "48_48") (pintype "bidirectional"))
      (node (ref "X-SOUTH") (pin "54") (pinfunction "54_54") (pintype "bidirectional"))
      (node (ref "X-SOUTH") (pin "60") (pinfunction "60_60") (pintype "bidirectional"))
      (node (ref "X-SOUTH") (pin "66") (pinfunction "66_66") (pintype "bidirectional"))
      (node (ref "X-SOUTH") (pin "72") (pinfunction "72_72") (pintype "bidirectional"))
      (node (ref "X-SOUTH") (pin "78") (pinfunction "78_78") (pintype "bidirectional"))
      (node (ref "X-SOUTH") (pin "84") (pinfunction "84_84") (pintype "bidirectional"))
      (node (ref "X-SOUTH") (pin "90") (pinfunction "90_90") (pintype "bidirectional"))
      (node (ref "X-SOUTH") (pin "96") (pinfunction "96_96") (pintype "bidirectional"))
    )
    (net (code "55") (name "ICSPCLK1") (class "Default")
      (node (ref "ICSP1") (pin "3") (pinfunction "3_3") (pintype "passive"))
      (node (ref "U1") (pin "42") (pinfunction "RB6/ICSPC_42") (pintype "bidirectional"))
    )
    (net (code "56") (name "ICSPCLK2") (class "Default")
      (node (ref "ICSP2") (pin "3") (pinfunction "3_3") (pintype "passive"))
      (node (ref "U2") (pin "42") (pinfunction "RB6/ICSPC_42") (pintype "bidirectional"))
    )
    (net (code "57") (name "ICSPCLK3") (class "Default")
      (node (ref "ICSP3") (pin "3") (pinfunction "3_3") (pintype "passive"))
      (node (ref "U3") (pin "42") (pinfunction "RB6/ICSPC_42") (pintype "bidirectional"))
    )
    (net (code "58") (name "ICSPCLK4") (class "Default")
      (node (ref "ICSP4") (pin "3") (pinfunction "3_3") (pintype "passive"))
      (node (ref "U4") (pin "42") (pinfunction "RB6/ICSPC_42") (pintype "bidirectional"))
    )
    (net (code "59") (name "ICSPCLK5") (class "Default")
      (node (ref "ICSP5") (pin "3") (pinfunction "3_3") (pintype "passive"))
      (node (ref "U5") (pin "42") (pinfunction "RB6/ICSPC_42") (pintype "bidirectional"))
    )
    (net (code "60") (name "ICSPCLK6") (class "Default")
      (node (ref "ICSP6") (pin "3") (pinfunction "3_3") (pintype "passive"))
      (node (ref "U6") (pin "42") (pinfunction "RB6/ICSPC_42") (pintype "bidirectional"))
    )
    (net (code "61") (name "ICSPCLK7") (class "Default")
      (node (ref "ICSP7") (pin "3") (pinfunction "3_3") (pintype "passive"))
      (node (ref "U7") (pin "42") (pinfunction "RB6/ICSPC_42") (pintype "bidirectional"))
    )
    (net (code "62") (name "ICSPCLK8") (class "Default")
      (node (ref "ICSP8") (pin "3") (pinfunction "3_3") (pintype "passive"))
      (node (ref "U8") (pin "42") (pinfunction "RB6/ICSPC_42") (pintype "bidirectional"))
    )
    (net (code "63") (name "ICSPDAT1") (class "Default")
      (node (ref "ICSP1") (pin "2") (pinfunction "2_2") (pintype "passive"))
      (node (ref "U1") (pin "37") (pinfunction "RB7/ICSPD_37") (pintype "bidirectional"))
    )
    (net (code "64") (name "ICSPDAT2") (class "Default")
      (node (ref "ICSP2") (pin "2") (pinfunction "2_2") (pintype "passive"))
      (node (ref "U2") (pin "37") (pinfunction "RB7/ICSPD_37") (pintype "bidirectional"))
    )
    (net (code "65") (name "ICSPDAT3") (class "Default")
      (node (ref "ICSP3") (pin "2") (pinfunction "2_2") (pintype "passive"))
      (node (ref "U3") (pin "37") (pinfunction "RB7/ICSPD_37") (pintype "bidirectional"))
    )
    (net (code "66") (name "ICSPDAT4") (class "Default")
      (node (ref "ICSP4") (pin "2") (pinfunction "2_2") (pintype "passive"))
      (node (ref "U4") (pin "37") (pinfunction "RB7/ICSPD_37") (pintype "bidirectional"))
    )
    (net (code "67") (name "ICSPDAT5") (class "Default")
      (node (ref "ICSP5") (pin "2") (pinfunction "2_2") (pintype "passive"))
      (node (ref "U5") (pin "37") (pinfunction "RB7/ICSPD_37") (pintype "bidirectional"))
    )
    (net (code "68") (name "ICSPDAT6") (class "Default")
      (node (ref "ICSP6") (pin "2") (pinfunction "2_2") (pintype "passive"))
      (node (ref "U6") (pin "37") (pinfunction "RB7/ICSPD_37") (pintype "bidirectional"))
    )
    (net (code "69") (name "ICSPDAT7") (class "Default")
      (node (ref "ICSP7") (pin "2") (pinfunction "2_2") (pintype "passive"))
      (node (ref "U7") (pin "37") (pinfunction "RB7/ICSPD_37") (pintype "bidirectional"))
    )
    (net (code "70") (name "ICSPDAT8") (class "Default")
      (node (ref "ICSP8") (pin "2") (pinfunction "2_2") (pintype "passive"))
      (node (ref "U8") (pin "37") (pinfunction "RB7/ICSPD_37") (pintype "bidirectional"))
    )
    (net (code "71") (name "LED5") (class "Default")
      (node (ref "LED4") (pin "4") (pinfunction "C_4") (pintype "passive"))
      (node (ref "U5") (pin "29") (pinfunction "RC1_29") (pintype "bidirectional"))
    )
    (net (code "72") (name "LED5B") (class "Default")
      (node (ref "LED4") (pin "3") (pinfunction "C_3") (pintype "passive"))
      (node (ref "U5") (pin "30") (pinfunction "RC0_30") (pintype "bidirectional"))
    )
    (net (code "73") (name "LED6") (class "Default")
      (node (ref "LED3") (pin "4") (pinfunction "C_4") (pintype "passive"))
      (node (ref "U6") (pin "61") (pinfunction "RE5_61") (pintype "bidirectional"))
    )
    (net (code "74") (name "LED6B") (class "Default")
      (node (ref "LED3") (pin "3") (pinfunction "C_3") (pintype "passive"))
      (node (ref "U6") (pin "62") (pinfunction "RE4_62") (pintype "bidirectional"))
    )
    (net (code "75") (name "LED7") (class "Default")
      (node (ref "LED2") (pin "4") (pinfunction "C_4") (pintype "passive"))
      (node (ref "U7") (pin "61") (pinfunction "RE5_61") (pintype "bidirectional"))
    )
    (net (code "76") (name "LED7B") (class "Default")
      (node (ref "LED2") (pin "3") (pinfunction "C_3") (pintype "passive"))
      (node (ref "U7") (pin "62") (pinfunction "RE4_62") (pintype "bidirectional"))
    )
    (net (code "77") (name "LED8") (class "Default")
      (node (ref "LED1") (pin "4") (pinfunction "C_4") (pintype "passive"))
      (node (ref "U8") (pin "29") (pinfunction "RC1_29") (pintype "bidirectional"))
    )
    (net (code "78") (name "LED8B") (class "Default")
      (node (ref "LED1") (pin "3") (pinfunction "C_3") (pintype "passive"))
      (node (ref "U8") (pin "30") (pinfunction "RC0_30") (pintype "bidirectional"))
    )
    (net (code "79") (name "N$3") (class "Default")
      (node (ref "U1") (pin "60") (pinfunction "RE6_60") (pintype "bidirectional"))
    )
    (net (code "80") (name "N$5") (class "Default")
      (node (ref "U1") (pin "61") (pinfunction "RE5_61") (pintype "bidirectional"))
    )
    (net (code "81") (name "N$6") (class "Default")
      (node (ref "U1") (pin "59") (pinfunction "RE7_59") (pintype "bidirectional"))
    )
    (net (code "82") (name "N00_N") (class "Default")
      (node (ref "U4") (pin "24") (pinfunction "RA0/AN0_24") (pintype "bidirectional"))
      (node (ref "X-NORTH") (pin "16") (pinfunction "16_16") (pintype "bidirectional"))
    )
    (net (code "83") (name "N00_P") (class "Default")
      (node (ref "U4") (pin "27") (pinfunction "RA5/AN4_27") (pintype "bidirectional"))
      (node (ref "X-NORTH") (pin "14") (pinfunction "14_14") (pintype "bidirectional"))
    )
    (net (code "84") (name "N01_N") (class "Default")
      (node (ref "U8") (pin "54") (pinfunction "AN25/RD2_54") (pintype "bidirectional"))
      (node (ref "X-NORTH") (pin "17") (pinfunction "17_17") (pintype "bidirectional"))
    )
    (net (code "85") (name "N01_P") (class "Default")
      (node (ref "U8") (pin "53") (pinfunction "AN26/RD3_53") (pintype "bidirectional"))
      (node (ref "X-NORTH") (pin "15") (pinfunction "15_15") (pintype "bidirectional"))
    )
    (net (code "86") (name "N02_N") (class "Default")
      (node (ref "U4") (pin "22") (pinfunction "RA2/AN2_22") (pintype "bidirectional"))
      (node (ref "X-NORTH") (pin "22") (pinfunction "22_22") (pintype "bidirectional"))
    )
    (net (code "87") (name "N02_P") (class "Default")
      (node (ref "U4") (pin "23") (pinfunction "RA1/AN1_23") (pintype "bidirectional"))
      (node (ref "X-NORTH") (pin "20") (pinfunction "20_20") (pintype "bidirectional"))
    )
    (net (code "88") (name "N03_N") (class "Default")
      (node (ref "U8") (pin "58") (pinfunction "AN23/RD0_58") (pintype "bidirectional"))
      (node (ref "X-NORTH") (pin "23") (pinfunction "23_23") (pintype "bidirectional"))
    )
    (net (code "89") (name "N03_P") (class "Default")
      (node (ref "U8") (pin "55") (pinfunction "AN24/RD1_55") (pintype "bidirectional"))
      (node (ref "X-NORTH") (pin "21") (pinfunction "21_21") (pintype "bidirectional"))
    )
    (net (code "90") (name "N04_N") (class "Default")
      (node (ref "U4") (pin "17") (pinfunction "AN6/RF1_17") (pintype "bidirectional"))
      (node (ref "X-NORTH") (pin "28") (pinfunction "28_28") (pintype "bidirectional"))
    )
    (net (code "91") (name "N04_P") (class "Default")
      (node (ref "U4") (pin "21") (pinfunction "RA3/AN3/REF+_21") (pintype "bidirectional"))
      (node (ref "X-NORTH") (pin "26") (pinfunction "26_26") (pintype "bidirectional"))
    )
    (net (code "92") (name "N05_N") (class "Default")
      (node (ref "U8") (pin "64") (pinfunction "AN29/RE2_64") (pintype "bidirectional"))
      (node (ref "X-NORTH") (pin "29") (pinfunction "29_29") (pintype "bidirectional"))
    )
    (net (code "93") (name "N05_P") (class "Default")
      (node (ref "U8") (pin "48") (pinfunction "RB0/AN17_48") (pintype "bidirectional"))
      (node (ref "X-NORTH") (pin "27") (pinfunction "27_27") (pintype "bidirectional"))
    )
    (net (code "94") (name "N06_N") (class "Default")
      (node (ref "U4") (pin "44") (pinfunction "RB4/AN21_44") (pintype "bidirectional"))
      (node (ref "X-NORTH") (pin "34") (pinfunction "34_34") (pintype "bidirectional"))
    )
    (net (code "95") (name "N06_P") (class "Default")
      (node (ref "U4") (pin "43") (pinfunction "RB5/AN22_43") (pintype "bidirectional"))
      (node (ref "X-NORTH") (pin "32") (pinfunction "32_32") (pintype "bidirectional"))
    )
    (net (code "96") (name "N07_N") (class "Default")
      (node (ref "U8") (pin "46") (pinfunction "RB2/AN19_46") (pintype "bidirectional"))
      (node (ref "X-NORTH") (pin "35") (pinfunction "35_35") (pintype "bidirectional"))
    )
    (net (code "97") (name "N07_P") (class "Default")
      (node (ref "U8") (pin "47") (pinfunction "RB1/AN18_47") (pintype "bidirectional"))
      (node (ref "X-NORTH") (pin "33") (pinfunction "33_33") (pintype "bidirectional"))
    )
    (net (code "98") (name "N08_N") (class "Default")
      (node (ref "U4") (pin "46") (pinfunction "RB2/AN19_46") (pintype "bidirectional"))
      (node (ref "X-NORTH") (pin "40") (pinfunction "40_40") (pintype "bidirectional"))
    )
    (net (code "99") (name "N08_P") (class "Default")
      (node (ref "U4") (pin "45") (pinfunction "RB3/AN20_45") (pintype "bidirectional"))
      (node (ref "X-NORTH") (pin "38") (pinfunction "38_38") (pintype "bidirectional"))
    )
    (net (code "100") (name "N09_N") (class "Default")
      (node (ref "U8") (pin "44") (pinfunction "RB4/AN21_44") (pintype "bidirectional"))
      (node (ref "X-NORTH") (pin "41") (pinfunction "41_41") (pintype "bidirectional"))
    )
    (net (code "101") (name "N09_P") (class "Default")
      (node (ref "U8") (pin "45") (pinfunction "RB3/AN20_45") (pintype "bidirectional"))
      (node (ref "X-NORTH") (pin "39") (pinfunction "39_39") (pintype "bidirectional"))
    )
    (net (code "102") (name "N10_N") (class "Default")
      (node (ref "U4") (pin "15") (pinfunction "AN8/RF3_15") (pintype "bidirectional"))
      (node (ref "X-NORTH") (pin "46") (pinfunction "46_46") (pintype "bidirectional"))
    )
    (net (code "103") (name "N10_P") (class "Default")
      (node (ref "U4") (pin "16") (pinfunction "AN7/RF2_16") (pintype "bidirectional"))
      (node (ref "X-NORTH") (pin "44") (pinfunction "44_44") (pintype "bidirectional"))
    )
    (net (code "104") (name "N11_N") (class "Default")
      (node (ref "U8") (pin "2") (pinfunction "AN27/RE0_2") (pintype "bidirectional"))
      (node (ref "X-NORTH") (pin "47") (pinfunction "47_47") (pintype "bidirectional"))
    )
    (net (code "105") (name "N11_P") (class "Default")
      (node (ref "U8") (pin "1") (pinfunction "AN28/RE1_1") (pintype "bidirectional"))
      (node (ref "X-NORTH") (pin "45") (pinfunction "45_45") (pintype "bidirectional"))
    )
    (net (code "106") (name "N12_N") (class "Default")
      (node (ref "U4") (pin "13") (pinfunction "AN10/RF5_13") (pintype "bidirectional"))
      (node (ref "X-NORTH") (pin "52") (pinfunction "52_52") (pintype "bidirectional"))
    )
    (net (code "107") (name "N12_P") (class "Default")
      (node (ref "U4") (pin "14") (pinfunction "AN9/RF4_14") (pintype "bidirectional"))
      (node (ref "X-NORTH") (pin "50") (pinfunction "50_50") (pintype "bidirectional"))
    )
    (net (code "108") (name "N13_N") (class "Default")
      (node (ref "U8") (pin "13") (pinfunction "AN10/RF5_13") (pintype "bidirectional"))
      (node (ref "X-NORTH") (pin "53") (pinfunction "53_53") (pintype "bidirectional"))
    )
    (net (code "109") (name "N13_P") (class "Default")
      (node (ref "U8") (pin "12") (pinfunction "AN11/RF6_12") (pintype "bidirectional"))
      (node (ref "X-NORTH") (pin "51") (pinfunction "51_51") (pintype "bidirectional"))
    )
    (net (code "110") (name "N14_N") (class "Default")
      (node (ref "U4") (pin "2") (pinfunction "AN27/RE0_2") (pintype "bidirectional"))
      (node (ref "X-NORTH") (pin "58") (pinfunction "58_58") (pintype "bidirectional"))
    )
    (net (code "111") (name "N14_P") (class "Default")
      (node (ref "U4") (pin "12") (pinfunction "AN11/RF6_12") (pintype "bidirectional"))
      (node (ref "X-NORTH") (pin "56") (pinfunction "56_56") (pintype "bidirectional"))
    )
    (net (code "112") (name "N15_N") (class "Default")
      (node (ref "U8") (pin "15") (pinfunction "AN8/RF3_15") (pintype "bidirectional"))
      (node (ref "X-NORTH") (pin "59") (pinfunction "59_59") (pintype "bidirectional"))
    )
    (net (code "113") (name "N15_P") (class "Default")
      (node (ref "U8") (pin "14") (pinfunction "AN9/RF4_14") (pintype "bidirectional"))
      (node (ref "X-NORTH") (pin "57") (pinfunction "57_57") (pintype "bidirectional"))
    )
    (net (code "114") (name "N16_N") (class "Default")
      (node (ref "U4") (pin "64") (pinfunction "AN29/RE2_64") (pintype "bidirectional"))
      (node (ref "X-NORTH") (pin "64") (pinfunction "64_64") (pintype "bidirectional"))
    )
    (net (code "115") (name "N16_P") (class "Default")
      (node (ref "U4") (pin "1") (pinfunction "AN28/RE1_1") (pintype "bidirectional"))
      (node (ref "X-NORTH") (pin "62") (pinfunction "62_62") (pintype "bidirectional"))
    )
    (net (code "116") (name "N17_N") (class "Default")
      (node (ref "U8") (pin "17") (pinfunction "AN6/RF1_17") (pintype "bidirectional"))
      (node (ref "X-NORTH") (pin "65") (pinfunction "65_65") (pintype "bidirectional"))
    )
    (net (code "117") (name "N17_P") (class "Default")
      (node (ref "U8") (pin "16") (pinfunction "AN7/RF2_16") (pintype "bidirectional"))
      (node (ref "X-NORTH") (pin "63") (pinfunction "63_63") (pintype "bidirectional"))
    )
    (net (code "118") (name "N18_N") (class "Default")
      (node (ref "U4") (pin "48") (pinfunction "RB0/AN17_48") (pintype "bidirectional"))
      (node (ref "X-NORTH") (pin "70") (pinfunction "70_70") (pintype "bidirectional"))
    )
    (net (code "119") (name "N18_P") (class "Default")
      (node (ref "U4") (pin "47") (pinfunction "RB1/AN18_47") (pintype "bidirectional"))
      (node (ref "X-NORTH") (pin "68") (pinfunction "68_68") (pintype "bidirectional"))
    )
    (net (code "120") (name "N19_N") (class "Default")
      (node (ref "U8") (pin "27") (pinfunction "RA5/AN4_27") (pintype "bidirectional"))
      (node (ref "X-NORTH") (pin "71") (pinfunction "71_71") (pintype "bidirectional"))
    )
    (net (code "121") (name "N19_P") (class "Default")
      (node (ref "U8") (pin "43") (pinfunction "RB5/AN22_43") (pintype "bidirectional"))
      (node (ref "X-NORTH") (pin "69") (pinfunction "69_69") (pintype "bidirectional"))
    )
    (net (code "122") (name "N20_N") (class "Default")
      (node (ref "U1") (pin "43") (pinfunction "RB5/AN22_43") (pintype "bidirectional"))
      (node (ref "X-NORTH") (pin "76") (pinfunction "76_76") (pintype "bidirectional"))
    )
    (net (code "123") (name "N20_P") (class "Default")
      (node (ref "U1") (pin "27") (pinfunction "RA5/AN4_27") (pintype "bidirectional"))
      (node (ref "X-NORTH") (pin "74") (pinfunction "74_74") (pintype "bidirectional"))
    )
    (net (code "124") (name "N21_N") (class "Default")
      (node (ref "U7") (pin "47") (pinfunction "RB1/AN18_47") (pintype "bidirectional"))
      (node (ref "X-NORTH") (pin "77") (pinfunction "77_77") (pintype "bidirectional"))
    )
    (net (code "125") (name "N21_P") (class "Default")
      (node (ref "U7") (pin "48") (pinfunction "RB0/AN17_48") (pintype "bidirectional"))
      (node (ref "X-NORTH") (pin "75") (pinfunction "75_75") (pintype "bidirectional"))
    )
    (net (code "126") (name "N22_N") (class "Default")
      (node (ref "U1") (pin "16") (pinfunction "AN7/RF2_16") (pintype "bidirectional"))
      (node (ref "X-NORTH") (pin "82") (pinfunction "82_82") (pintype "bidirectional"))
    )
    (net (code "127") (name "N22_P") (class "Default")
      (node (ref "U1") (pin "17") (pinfunction "AN6/RF1_17") (pintype "bidirectional"))
      (node (ref "X-NORTH") (pin "80") (pinfunction "80_80") (pintype "bidirectional"))
    )
    (net (code "128") (name "N23_N") (class "Default")
      (node (ref "U7") (pin "1") (pinfunction "AN28/RE1_1") (pintype "bidirectional"))
      (node (ref "X-NORTH") (pin "83") (pinfunction "83_83") (pintype "bidirectional"))
    )
    (net (code "129") (name "N23_P") (class "Default")
      (node (ref "U7") (pin "64") (pinfunction "AN29/RE2_64") (pintype "bidirectional"))
      (node (ref "X-NORTH") (pin "81") (pinfunction "81_81") (pintype "bidirectional"))
    )
    (net (code "130") (name "N24_N") (class "Default")
      (node (ref "U1") (pin "14") (pinfunction "AN9/RF4_14") (pintype "bidirectional"))
      (node (ref "X-NORTH") (pin "88") (pinfunction "88_88") (pintype "bidirectional"))
    )
    (net (code "131") (name "N24_P") (class "Default")
      (node (ref "U1") (pin "15") (pinfunction "AN8/RF3_15") (pintype "bidirectional"))
      (node (ref "X-NORTH") (pin "86") (pinfunction "86_86") (pintype "bidirectional"))
    )
    (net (code "132") (name "N25_N") (class "Default")
      (node (ref "U7") (pin "12") (pinfunction "AN11/RF6_12") (pintype "bidirectional"))
      (node (ref "X-NORTH") (pin "89") (pinfunction "89_89") (pintype "bidirectional"))
    )
    (net (code "133") (name "N25_P") (class "Default")
      (node (ref "U7") (pin "2") (pinfunction "AN27/RE0_2") (pintype "bidirectional"))
      (node (ref "X-NORTH") (pin "87") (pinfunction "87_87") (pintype "bidirectional"))
    )
    (net (code "134") (name "N26_N") (class "Default")
      (node (ref "U1") (pin "12") (pinfunction "AN11/RF6_12") (pintype "bidirectional"))
      (node (ref "X-NORTH") (pin "94") (pinfunction "94_94") (pintype "bidirectional"))
    )
    (net (code "135") (name "N26_P") (class "Default")
      (node (ref "U1") (pin "13") (pinfunction "AN10/RF5_13") (pintype "bidirectional"))
      (node (ref "X-NORTH") (pin "92") (pinfunction "92_92") (pintype "bidirectional"))
    )
    (net (code "136") (name "N27_N") (class "Default")
      (node (ref "U7") (pin "14") (pinfunction "AN9/RF4_14") (pintype "bidirectional"))
      (node (ref "X-NORTH") (pin "95") (pinfunction "95_95") (pintype "bidirectional"))
    )
    (net (code "137") (name "N27_P") (class "Default")
      (node (ref "U7") (pin "13") (pinfunction "AN10/RF5_13") (pintype "bidirectional"))
      (node (ref "X-NORTH") (pin "93") (pinfunction "93_93") (pintype "bidirectional"))
    )
    (net (code "138") (name "N28_N") (class "Default")
      (node (ref "U1") (pin "1") (pinfunction "AN28/RE1_1") (pintype "bidirectional"))
      (node (ref "X-NORTH") (pin "100") (pinfunction "100_100") (pintype "bidirectional"))
    )
    (net (code "139") (name "N28_P") (class "Default")
      (node (ref "U1") (pin "2") (pinfunction "AN27/RE0_2") (pintype "bidirectional"))
      (node (ref "X-NORTH") (pin "98") (pinfunction "98_98") (pintype "bidirectional"))
    )
    (net (code "140") (name "N29_N") (class "Default")
      (node (ref "U7") (pin "16") (pinfunction "AN7/RF2_16") (pintype "bidirectional"))
      (node (ref "X-NORTH") (pin "101") (pinfunction "101_101") (pintype "bidirectional"))
    )
    (net (code "141") (name "N29_P") (class "Default")
      (node (ref "U7") (pin "15") (pinfunction "AN8/RF3_15") (pintype "bidirectional"))
      (node (ref "X-NORTH") (pin "99") (pinfunction "99_99") (pintype "bidirectional"))
    )
    (net (code "142") (name "N30_N") (class "Default")
      (node (ref "U1") (pin "45") (pinfunction "RB3/AN20_45") (pintype "bidirectional"))
      (node (ref "X-NORTH") (pin "106") (pinfunction "106_106") (pintype "bidirectional"))
    )
    (net (code "143") (name "N30_P") (class "Default")
      (node (ref "U1") (pin "44") (pinfunction "RB4/AN21_44") (pintype "bidirectional"))
      (node (ref "X-NORTH") (pin "104") (pinfunction "104_104") (pintype "bidirectional"))
    )
    (net (code "144") (name "N31_N") (class "Default")
      (node (ref "U7") (pin "45") (pinfunction "RB3/AN20_45") (pintype "bidirectional"))
      (node (ref "X-NORTH") (pin "107") (pinfunction "107_107") (pintype "bidirectional"))
    )
    (net (code "145") (name "N31_P") (class "Default")
      (node (ref "U7") (pin "46") (pinfunction "RB2/AN19_46") (pintype "bidirectional"))
      (node (ref "X-NORTH") (pin "105") (pinfunction "105_105") (pintype "bidirectional"))
    )
    (net (code "146") (name "N32_N") (class "Default")
      (node (ref "U1") (pin "47") (pinfunction "RB1/AN18_47") (pintype "bidirectional"))
      (node (ref "X-NORTH") (pin "112") (pinfunction "112_112") (pintype "bidirectional"))
    )
    (net (code "147") (name "N32_P") (class "Default")
      (node (ref "U1") (pin "46") (pinfunction "RB2/AN19_46") (pintype "bidirectional"))
      (node (ref "X-NORTH") (pin "110") (pinfunction "110_110") (pintype "bidirectional"))
    )
    (net (code "148") (name "N33_N") (class "Default")
      (node (ref "U7") (pin "43") (pinfunction "RB5/AN22_43") (pintype "bidirectional"))
      (node (ref "X-NORTH") (pin "113") (pinfunction "113_113") (pintype "bidirectional"))
    )
    (net (code "149") (name "N33_P") (class "Default")
      (node (ref "U7") (pin "44") (pinfunction "RB4/AN21_44") (pintype "bidirectional"))
      (node (ref "X-NORTH") (pin "111") (pinfunction "111_111") (pintype "bidirectional"))
    )
    (net (code "150") (name "N34_N") (class "Default")
      (node (ref "U1") (pin "48") (pinfunction "RB0/AN17_48") (pintype "bidirectional"))
      (node (ref "X-NORTH") (pin "118") (pinfunction "118_118") (pintype "bidirectional"))
    )
    (net (code "151") (name "N34_P") (class "Default")
      (node (ref "U1") (pin "64") (pinfunction "AN29/RE2_64") (pintype "bidirectional"))
      (node (ref "X-NORTH") (pin "116") (pinfunction "116_116") (pintype "bidirectional"))
    )
    (net (code "152") (name "N35_N") (class "Default")
      (node (ref "U7") (pin "21") (pinfunction "RA3/AN3/REF+_21") (pintype "bidirectional"))
      (node (ref "X-NORTH") (pin "119") (pinfunction "119_119") (pintype "bidirectional"))
    )
    (net (code "153") (name "N35_P") (class "Default")
      (node (ref "U7") (pin "17") (pinfunction "AN6/RF1_17") (pintype "bidirectional"))
      (node (ref "X-NORTH") (pin "117") (pinfunction "117_117") (pintype "bidirectional"))
    )
    (net (code "154") (name "N36_N") (class "Default")
      (node (ref "U1") (pin "55") (pinfunction "AN24/RD1_55") (pintype "bidirectional"))
      (node (ref "X-NORTH") (pin "124") (pinfunction "124_124") (pintype "bidirectional"))
    )
    (net (code "155") (name "N36_P") (class "Default")
      (node (ref "U1") (pin "58") (pinfunction "AN23/RD0_58") (pintype "bidirectional"))
      (node (ref "X-NORTH") (pin "122") (pinfunction "122_122") (pintype "bidirectional"))
    )
    (net (code "156") (name "N37_N") (class "Default")
      (node (ref "U7") (pin "23") (pinfunction "RA1/AN1_23") (pintype "bidirectional"))
      (node (ref "X-NORTH") (pin "125") (pinfunction "125_125") (pintype "bidirectional"))
    )
    (net (code "157") (name "N37_P") (class "Default")
      (node (ref "U7") (pin "22") (pinfunction "RA2/AN2_22") (pintype "bidirectional"))
      (node (ref "X-NORTH") (pin "123") (pinfunction "123_123") (pintype "bidirectional"))
    )
    (net (code "158") (name "N38_N") (class "Default")
      (node (ref "U1") (pin "53") (pinfunction "AN26/RD3_53") (pintype "bidirectional"))
      (node (ref "X-NORTH") (pin "130") (pinfunction "130_130") (pintype "bidirectional"))
    )
    (net (code "159") (name "N38_P") (class "Default")
      (node (ref "U1") (pin "54") (pinfunction "AN25/RD2_54") (pintype "bidirectional"))
      (node (ref "X-NORTH") (pin "128") (pinfunction "128_128") (pintype "bidirectional"))
    )
    (net (code "160") (name "N39_N") (class "Default")
      (node (ref "U7") (pin "27") (pinfunction "RA5/AN4_27") (pintype "bidirectional"))
      (node (ref "X-NORTH") (pin "131") (pinfunction "131_131") (pintype "bidirectional"))
    )
    (net (code "161") (name "N39_P") (class "Default")
      (node (ref "U7") (pin "24") (pinfunction "RA0/AN0_24") (pintype "bidirectional"))
      (node (ref "X-NORTH") (pin "129") (pinfunction "129_129") (pintype "bidirectional"))
    )
    (net (code "162") (name "N_CHK_EN") (class "Default")
      (node (ref "U4") (pin "29") (pinfunction "RC1_29") (pintype "bidirectional"))
      (node (ref "X-NORTH") (pin "8") (pinfunction "8_8") (pintype "bidirectional"))
    )
    (net (code "163") (name "N_CHK_V") (class "Default")
      (node (ref "C141") (pin "1") (pinfunction "1_1") (pintype "passive"))
      (node (ref "C142") (pin "1") (pinfunction "1_1") (pintype "passive"))
      (node (ref "PWRN") (pin "2") (pinfunction "2_2") (pintype "passive"))
      (node (ref "R21") (pin "1") (pinfunction "1_1") (pintype "passive"))
      (node (ref "R22") (pin "1") (pinfunction "1_1") (pintype "passive"))
      (node (ref "U11") (pin "1") (pinfunction "VDD_1") (pintype "power_in"))
      (node (ref "X-NORTH") (pin "10") (pinfunction "10_10") (pintype "bidirectional"))
    )
    (net (code "164") (name "N_I2C_EN") (class "Default")
      (node (ref "U7") (pin "28") (pinfunction "RA4_28") (pintype "bidirectional"))
      (node (ref "X-NORTH") (pin "137") (pinfunction "137_137") (pintype "bidirectional"))
    )
    (net (code "165") (name "N_I2C_V") (class "Default")
      (node (ref "X-NORTH") (pin "135") (pinfunction "135_135") (pintype "bidirectional"))
    )
    (net (code "166") (name "N_SCK") (class "Default")
      (node (ref "U1") (pin "50") (pinfunction "SCK2/RD6_50") (pintype "bidirectional"))
      (node (ref "X-NORTH") (pin "144") (pinfunction "144_144") (pintype "bidirectional"))
    )
    (net (code "167") (name "N_SCL") (class "Default")
      (node (ref "R2") (pin "2") (pinfunction "2_2") (pintype "passive"))
      (node (ref "U7") (pin "50") (pinfunction "SCK2/RD6_50") (pintype "bidirectional"))
      (node (ref "X-NORTH") (pin "143") (pinfunction "143_143") (pintype "bidirectional"))
    )
    (net (code "168") (name "N_SDA") (class "Default")
      (node (ref "R1") (pin "2") (pinfunction "2_2") (pintype "passive"))
      (node (ref "U7") (pin "51") (pinfunction "SDI2/RD5_51") (pintype "bidirectional"))
      (node (ref "X-NORTH") (pin "141") (pinfunction "141_141") (pintype "bidirectional"))
    )
    (net (code "169") (name "N_SDI") (class "Default")
      (node (ref "U1") (pin "51") (pinfunction "SDI2/RD5_51") (pintype "bidirectional"))
      (node (ref "X-NORTH") (pin "140") (pinfunction "140_140") (pintype "bidirectional"))
    )
    (net (code "170") (name "N_SDO") (class "Default")
      (node (ref "U1") (pin "52") (pinfunction "SDO2/RD4_52") (pintype "bidirectional"))
      (node (ref "X-NORTH") (pin "142") (pinfunction "142_142") (pintype "bidirectional"))
    )
    (net (code "171") (name "N_SPI_EN") (class "Default")
      (node (ref "U1") (pin "49") (pinfunction "~{SS2}/RD7_49") (pintype "bidirectional"))
      (node (ref "X-NORTH") (pin "136") (pinfunction "136_136") (pintype "bidirectional"))
    )
    (net (code "172") (name "N_SPI_V") (class "Default")
      (node (ref "X-NORTH") (pin "134") (pinfunction "134_134") (pintype "bidirectional"))
    )
    (net (code "173") (name "N_VE") (class "Default")
      (node (ref "C140") (pin "1") (pinfunction "1_1") (pintype "passive"))
      (node (ref "PWR-NORTH") (pin "2") (pinfunction "2_2") (pintype "passive"))
      (node (ref "X-NORTH") (pin "109") (pinfunction "109_109") (pintype "bidirectional"))
      (node (ref "X-NORTH") (pin "115") (pinfunction "115_115") (pintype "bidirectional"))
      (node (ref "X-NORTH") (pin "127") (pinfunction "127_127") (pintype "bidirectional"))
      (node (ref "X-NORTH") (pin "133") (pinfunction "133_133") (pintype "bidirectional"))
    )
    (net (code "174") (name "N_VE_CV") (class "Default")
      (node (ref "U11") (pin "7") (pinfunction "VOUTB_7") (pintype "output"))
      (node (ref "X-NORTH") (pin "6") (pinfunction "6_6") (pintype "bidirectional"))
    )
    (net (code "175") (name "N_VE_OV") (class "Default")
      (node (ref "U8") (pin "51") (pinfunction "SDI2/RD5_51") (pintype "bidirectional"))
      (node (ref "X-NORTH") (pin "5") (pinfunction "5_5") (pintype "bidirectional"))
    )
    (net (code "176") (name "N_VE_RS") (class "Default")
      (node (ref "X-NORTH") (pin "121") (pinfunction "121_121") (pintype "bidirectional"))
    )
    (net (code "177") (name "N_VE_UV") (class "Default")
      (node (ref "U8") (pin "61") (pinfunction "RE5_61") (pintype "bidirectional"))
      (node (ref "X-NORTH") (pin "11") (pinfunction "11_11") (pintype "bidirectional"))
    )
    (net (code "178") (name "N_VN") (class "Default")
      (node (ref "C139") (pin "1") (pinfunction "1_1") (pintype "passive"))
      (node (ref "PWR-NORTH") (pin "4") (pinfunction "4_4") (pintype "passive"))
      (node (ref "X-NORTH") (pin "49") (pinfunction "49_49") (pintype "bidirectional"))
      (node (ref "X-NORTH") (pin "55") (pinfunction "55_55") (pintype "bidirectional"))
      (node (ref "X-NORTH") (pin "61") (pinfunction "61_61") (pintype "bidirectional"))
      (node (ref "X-NORTH") (pin "67") (pinfunction "67_67") (pintype "bidirectional"))
      (node (ref "X-NORTH") (pin "79") (pinfunction "79_79") (pintype "bidirectional"))
      (node (ref "X-NORTH") (pin "85") (pinfunction "85_85") (pintype "bidirectional"))
      (node (ref "X-NORTH") (pin "91") (pinfunction "91_91") (pintype "bidirectional"))
      (node (ref "X-NORTH") (pin "97") (pinfunction "97_97") (pintype "bidirectional"))
    )
    (net (code "179") (name "N_VN_CV") (class "Default")
      (node (ref "U11") (pin "8") (pinfunction "VOUTC_8") (pintype "output"))
      (node (ref "X-NORTH") (pin "4") (pinfunction "4_4") (pintype "bidirectional"))
    )
    (net (code "180") (name "N_VN_OV") (class "Default")
      (node (ref "U8") (pin "50") (pinfunction "SCK2/RD6_50") (pintype "bidirectional"))
      (node (ref "X-NORTH") (pin "3") (pinfunction "3_3") (pintype "bidirectional"))
    )
    (net (code "181") (name "N_VN_RS") (class "Default")
      (node (ref "X-NORTH") (pin "73") (pinfunction "73_73") (pintype "bidirectional"))
    )
    (net (code "182") (name "N_VN_UV") (class "Default")
      (node (ref "U8") (pin "60") (pinfunction "RE6_60") (pintype "bidirectional"))
      (node (ref "X-NORTH") (pin "9") (pinfunction "9_9") (pintype "bidirectional"))
    )
    (net (code "183") (name "N_VW") (class "Default")
      (node (ref "C138") (pin "1") (pinfunction "1_1") (pintype "passive"))
      (node (ref "PWR-NORTH") (pin "6") (pinfunction "6_6") (pintype "passive"))
      (node (ref "X-NORTH") (pin "13") (pinfunction "13_13") (pintype "bidirectional"))
      (node (ref "X-NORTH") (pin "19") (pinfunction "19_19") (pintype "bidirectional"))
      (node (ref "X-NORTH") (pin "31") (pinfunction "31_31") (pintype "bidirectional"))
      (node (ref "X-NORTH") (pin "37") (pinfunction "37_37") (pintype "bidirectional"))
    )
    (net (code "184") (name "N_VW_CV") (class "Default")
      (node (ref "U11") (pin "9") (pinfunction "VOUTD_9") (pintype "output"))
      (node (ref "X-NORTH") (pin "2") (pinfunction "2_2") (pintype "bidirectional"))
    )
    (net (code "185") (name "N_VW_OV") (class "Default")
      (node (ref "U8") (pin "49") (pinfunction "~{SS2}/RD7_49") (pintype "bidirectional"))
      (node (ref "X-NORTH") (pin "1") (pinfunction "1_1") (pintype "bidirectional"))
    )
    (net (code "186") (name "N_VW_RS") (class "Default")
      (node (ref "X-NORTH") (pin "25") (pinfunction "25_25") (pintype "bidirectional"))
    )
    (net (code "187") (name "N_VW_UV") (class "Default")
      (node (ref "U8") (pin "59") (pinfunction "RE7_59") (pintype "bidirectional"))
      (node (ref "X-NORTH") (pin "7") (pinfunction "7_7") (pintype "bidirectional"))
    )
    (net (code "188") (name "Net-(LED1A-A)") (class "Default")
      (node (ref "LED1") (pin "1") (pinfunction "A_1") (pintype "passive"))
      (node (ref "R13") (pin "2") (pinfunction "2_2") (pintype "passive"))
    )
    (net (code "189") (name "Net-(LED1B-A)") (class "Default")
      (node (ref "LED1") (pin "2") (pinfunction "A_2") (pintype "passive"))
      (node (ref "R14") (pin "2") (pinfunction "2_2") (pintype "passive"))
    )
    (net (code "190") (name "Net-(LED2A-A)") (class "Default")
      (node (ref "LED2") (pin "1") (pinfunction "A_1") (pintype "passive"))
      (node (ref "R15") (pin "2") (pinfunction "2_2") (pintype "passive"))
    )
    (net (code "191") (name "Net-(LED2B-A)") (class "Default")
      (node (ref "LED2") (pin "2") (pinfunction "A_2") (pintype "passive"))
      (node (ref "R16") (pin "2") (pinfunction "2_2") (pintype "passive"))
    )
    (net (code "192") (name "Net-(LED3A-A)") (class "Default")
      (node (ref "LED3") (pin "1") (pinfunction "A_1") (pintype "passive"))
      (node (ref "R17") (pin "2") (pinfunction "2_2") (pintype "passive"))
    )
    (net (code "193") (name "Net-(LED3B-A)") (class "Default")
      (node (ref "LED3") (pin "2") (pinfunction "A_2") (pintype "passive"))
      (node (ref "R18") (pin "2") (pinfunction "2_2") (pintype "passive"))
    )
    (net (code "194") (name "Net-(LED4A-A)") (class "Default")
      (node (ref "LED4") (pin "1") (pinfunction "A_1") (pintype "passive"))
      (node (ref "R19") (pin "2") (pinfunction "2_2") (pintype "passive"))
    )
    (net (code "195") (name "Net-(LED4B-A)") (class "Default")
      (node (ref "LED4") (pin "2") (pinfunction "A_2") (pintype "passive"))
      (node (ref "R20") (pin "2") (pinfunction "2_2") (pintype "passive"))
    )
    (net (code "196") (name "Net-(U1-AN16{slash}RF0)") (class "Default")
      (node (ref "C1") (pin "1") (pinfunction "1_1") (pintype "passive"))
      (node (ref "U1") (pin "18") (pinfunction "AN16/RF0_18") (pintype "bidirectional"))
    )
    (net (code "197") (name "Net-(U2-AN16{slash}RF0)") (class "Default")
      (node (ref "C12") (pin "1") (pinfunction "1_1") (pintype "passive"))
      (node (ref "U2") (pin "18") (pinfunction "AN16/RF0_18") (pintype "bidirectional"))
    )
    (net (code "198") (name "Net-(U3-AN16{slash}RF0)") (class "Default")
      (node (ref "C23") (pin "1") (pinfunction "1_1") (pintype "passive"))
      (node (ref "U3") (pin "18") (pinfunction "AN16/RF0_18") (pintype "bidirectional"))
    )
    (net (code "199") (name "Net-(U4-AN16{slash}RF0)") (class "Default")
      (node (ref "C34") (pin "1") (pinfunction "1_1") (pintype "passive"))
      (node (ref "U4") (pin "18") (pinfunction "AN16/RF0_18") (pintype "bidirectional"))
    )
    (net (code "200") (name "Net-(U5-AN16{slash}RF0)") (class "Default")
      (node (ref "C45") (pin "1") (pinfunction "1_1") (pintype "passive"))
      (node (ref "U5") (pin "18") (pinfunction "AN16/RF0_18") (pintype "bidirectional"))
    )
    (net (code "201") (name "Net-(U6-AN16{slash}RF0)") (class "Default")
      (node (ref "C56") (pin "1") (pinfunction "1_1") (pintype "passive"))
      (node (ref "U6") (pin "18") (pinfunction "AN16/RF0_18") (pintype "bidirectional"))
    )
    (net (code "202") (name "Net-(U7-AN16{slash}RF0)") (class "Default")
      (node (ref "C67") (pin "1") (pinfunction "1_1") (pintype "passive"))
      (node (ref "U7") (pin "18") (pinfunction "AN16/RF0_18") (pintype "bidirectional"))
    )
    (net (code "203") (name "Net-(U8-AN16{slash}RF0)") (class "Default")
      (node (ref "C78") (pin "1") (pinfunction "1_1") (pintype "passive"))
      (node (ref "U8") (pin "18") (pinfunction "AN16/RF0_18") (pintype "bidirectional"))
    )
    (net (code "204") (name "Net-(U10-OUT)") (class "Default")
      (node (ref "U10") (pin "3") (pinfunction "OUT_3") (pintype "bidirectional"))
      (node (ref "U9") (pin "1") (pinfunction "CLK_1") (pintype "input"))
    )
    (net (code "205") (name "Net-(U11-VOUTA)") (class "Default")
      (node (ref "TPN") (pin "TP") (pinfunction "TP_TP") (pintype "input"))
      (node (ref "U11") (pin "6") (pinfunction "VOUTA_6") (pintype "output"))
    )
    (net (code "206") (name "Net-(U12-VOUTA)") (class "Default")
      (node (ref "TPS") (pin "TP") (pinfunction "TP_TP") (pintype "input"))
      (node (ref "U12") (pin "6") (pinfunction "VOUTA_6") (pintype "output"))
    )
    (net (code "207") (name "RX1") (class "Default")
      (node (ref "SER1") (pin "3") (pinfunction "3_3") (pintype "passive"))
      (node (ref "U1") (pin "32") (pinfunction "RC7/RX1_32") (pintype "bidirectional"))
    )
    (net (code "208") (name "RX1B") (class "Default")
      (node (ref "U1") (pin "5") (pinfunction "RX2/AN14/RG2_5") (pintype "bidirectional"))
    )
    (net (code "209") (name "RX2") (class "Default")
      (node (ref "SER2") (pin "3") (pinfunction "3_3") (pintype "passive"))
      (node (ref "U2") (pin "32") (pinfunction "RC7/RX1_32") (pintype "bidirectional"))
    )
    (net (code "210") (name "RX2B") (class "Default")
      (node (ref "U2") (pin "5") (pinfunction "RX2/AN14/RG2_5") (pintype "bidirectional"))
    )
    (net (code "211") (name "RX3") (class "Default")
      (node (ref "SER3") (pin "3") (pinfunction "3_3") (pintype "passive"))
      (node (ref "U3") (pin "32") (pinfunction "RC7/RX1_32") (pintype "bidirectional"))
    )
    (net (code "212") (name "RX3B") (class "Default")
      (node (ref "U3") (pin "5") (pinfunction "RX2/AN14/RG2_5") (pintype "bidirectional"))
    )
    (net (code "213") (name "RX4") (class "Default")
      (node (ref "SER4") (pin "3") (pinfunction "3_3") (pintype "passive"))
      (node (ref "U4") (pin "32") (pinfunction "RC7/RX1_32") (pintype "bidirectional"))
    )
    (net (code "214") (name "RX4B") (class "Default")
      (node (ref "U4") (pin "5") (pinfunction "RX2/AN14/RG2_5") (pintype "bidirectional"))
    )
    (net (code "215") (name "RX5") (class "Default")
      (node (ref "SER5") (pin "3") (pinfunction "3_3") (pintype "passive"))
      (node (ref "U5") (pin "32") (pinfunction "RC7/RX1_32") (pintype "bidirectional"))
    )
    (net (code "216") (name "RX5B") (class "Default")
      (node (ref "U5") (pin "5") (pinfunction "RX2/AN14/RG2_5") (pintype "bidirectional"))
    )
    (net (code "217") (name "RX6") (class "Default")
      (node (ref "SER6") (pin "3") (pinfunction "3_3") (pintype "passive"))
      (node (ref "U6") (pin "32") (pinfunction "RC7/RX1_32") (pintype "bidirectional"))
    )
    (net (code "218") (name "RX6B") (class "Default")
      (node (ref "U6") (pin "5") (pinfunction "RX2/AN14/RG2_5") (pintype "bidirectional"))
    )
    (net (code "219") (name "RX7") (class "Default")
      (node (ref "SER7") (pin "3") (pinfunction "3_3") (pintype "passive"))
      (node (ref "U7") (pin "32") (pinfunction "RC7/RX1_32") (pintype "bidirectional"))
    )
    (net (code "220") (name "RX7B") (class "Default")
      (node (ref "U7") (pin "5") (pinfunction "RX2/AN14/RG2_5") (pintype "bidirectional"))
    )
    (net (code "221") (name "RX8") (class "Default")
      (node (ref "SER8") (pin "3") (pinfunction "3_3") (pintype "passive"))
      (node (ref "U8") (pin "32") (pinfunction "RC7/RX1_32") (pintype "bidirectional"))
    )
    (net (code "222") (name "RX8B") (class "Default")
      (node (ref "U8") (pin "5") (pinfunction "RX2/AN14/RG2_5") (pintype "bidirectional"))
    )
    (net (code "223") (name "S00_N") (class "Default")
      (node (ref "U2") (pin "24") (pinfunction "RA0/AN0_24") (pintype "bidirectional"))
      (node (ref "X-SOUTH") (pin "16") (pinfunction "16_16") (pintype "bidirectional"))
    )
    (net (code "224") (name "S00_P") (class "Default")
      (node (ref "U2") (pin "27") (pinfunction "RA5/AN4_27") (pintype "bidirectional"))
      (node (ref "X-SOUTH") (pin "14") (pinfunction "14_14") (pintype "bidirectional"))
    )
    (net (code "225") (name "S01_N") (class "Default")
      (node (ref "U5") (pin "54") (pinfunction "AN25/RD2_54") (pintype "bidirectional"))
      (node (ref "X-SOUTH") (pin "17") (pinfunction "17_17") (pintype "bidirectional"))
    )
    (net (code "226") (name "S01_P") (class "Default")
      (node (ref "U5") (pin "53") (pinfunction "AN26/RD3_53") (pintype "bidirectional"))
      (node (ref "X-SOUTH") (pin "15") (pinfunction "15_15") (pintype "bidirectional"))
    )
    (net (code "227") (name "S02_N") (class "Default")
      (node (ref "U2") (pin "22") (pinfunction "RA2/AN2_22") (pintype "bidirectional"))
      (node (ref "X-SOUTH") (pin "22") (pinfunction "22_22") (pintype "bidirectional"))
    )
    (net (code "228") (name "S02_P") (class "Default")
      (node (ref "U2") (pin "23") (pinfunction "RA1/AN1_23") (pintype "bidirectional"))
      (node (ref "X-SOUTH") (pin "20") (pinfunction "20_20") (pintype "bidirectional"))
    )
    (net (code "229") (name "S03_N") (class "Default")
      (node (ref "U5") (pin "58") (pinfunction "AN23/RD0_58") (pintype "bidirectional"))
      (node (ref "X-SOUTH") (pin "23") (pinfunction "23_23") (pintype "bidirectional"))
    )
    (net (code "230") (name "S03_P") (class "Default")
      (node (ref "U5") (pin "55") (pinfunction "AN24/RD1_55") (pintype "bidirectional"))
      (node (ref "X-SOUTH") (pin "21") (pinfunction "21_21") (pintype "bidirectional"))
    )
    (net (code "231") (name "S04_N") (class "Default")
      (node (ref "U2") (pin "17") (pinfunction "AN6/RF1_17") (pintype "bidirectional"))
      (node (ref "X-SOUTH") (pin "28") (pinfunction "28_28") (pintype "bidirectional"))
    )
    (net (code "232") (name "S04_P") (class "Default")
      (node (ref "U2") (pin "21") (pinfunction "RA3/AN3/REF+_21") (pintype "bidirectional"))
      (node (ref "X-SOUTH") (pin "26") (pinfunction "26_26") (pintype "bidirectional"))
    )
    (net (code "233") (name "S05_N") (class "Default")
      (node (ref "U5") (pin "64") (pinfunction "AN29/RE2_64") (pintype "bidirectional"))
      (node (ref "X-SOUTH") (pin "29") (pinfunction "29_29") (pintype "bidirectional"))
    )
    (net (code "234") (name "S05_P") (class "Default")
      (node (ref "U5") (pin "48") (pinfunction "RB0/AN17_48") (pintype "bidirectional"))
      (node (ref "X-SOUTH") (pin "27") (pinfunction "27_27") (pintype "bidirectional"))
    )
    (net (code "235") (name "S06_N") (class "Default")
      (node (ref "U2") (pin "44") (pinfunction "RB4/AN21_44") (pintype "bidirectional"))
      (node (ref "X-SOUTH") (pin "34") (pinfunction "34_34") (pintype "bidirectional"))
    )
    (net (code "236") (name "S06_P") (class "Default")
      (node (ref "U2") (pin "43") (pinfunction "RB5/AN22_43") (pintype "bidirectional"))
      (node (ref "X-SOUTH") (pin "32") (pinfunction "32_32") (pintype "bidirectional"))
    )
    (net (code "237") (name "S07_N") (class "Default")
      (node (ref "U5") (pin "46") (pinfunction "RB2/AN19_46") (pintype "bidirectional"))
      (node (ref "X-SOUTH") (pin "35") (pinfunction "35_35") (pintype "bidirectional"))
    )
    (net (code "238") (name "S07_P") (class "Default")
      (node (ref "U5") (pin "47") (pinfunction "RB1/AN18_47") (pintype "bidirectional"))
      (node (ref "X-SOUTH") (pin "33") (pinfunction "33_33") (pintype "bidirectional"))
    )
    (net (code "239") (name "S08_N") (class "Default")
      (node (ref "U2") (pin "46") (pinfunction "RB2/AN19_46") (pintype "bidirectional"))
      (node (ref "X-SOUTH") (pin "40") (pinfunction "40_40") (pintype "bidirectional"))
    )
    (net (code "240") (name "S08_P") (class "Default")
      (node (ref "U2") (pin "45") (pinfunction "RB3/AN20_45") (pintype "bidirectional"))
      (node (ref "X-SOUTH") (pin "38") (pinfunction "38_38") (pintype "bidirectional"))
    )
    (net (code "241") (name "S09_N") (class "Default")
      (node (ref "U5") (pin "44") (pinfunction "RB4/AN21_44") (pintype "bidirectional"))
      (node (ref "X-SOUTH") (pin "41") (pinfunction "41_41") (pintype "bidirectional"))
    )
    (net (code "242") (name "S09_P") (class "Default")
      (node (ref "U5") (pin "45") (pinfunction "RB3/AN20_45") (pintype "bidirectional"))
      (node (ref "X-SOUTH") (pin "39") (pinfunction "39_39") (pintype "bidirectional"))
    )
    (net (code "243") (name "S10_N") (class "Default")
      (node (ref "U2") (pin "15") (pinfunction "AN8/RF3_15") (pintype "bidirectional"))
      (node (ref "X-SOUTH") (pin "46") (pinfunction "46_46") (pintype "bidirectional"))
    )
    (net (code "244") (name "S10_P") (class "Default")
      (node (ref "U2") (pin "16") (pinfunction "AN7/RF2_16") (pintype "bidirectional"))
      (node (ref "X-SOUTH") (pin "44") (pinfunction "44_44") (pintype "bidirectional"))
    )
    (net (code "245") (name "S11_N") (class "Default")
      (node (ref "U5") (pin "2") (pinfunction "AN27/RE0_2") (pintype "bidirectional"))
      (node (ref "X-SOUTH") (pin "47") (pinfunction "47_47") (pintype "bidirectional"))
    )
    (net (code "246") (name "S11_P") (class "Default")
      (node (ref "U5") (pin "1") (pinfunction "AN28/RE1_1") (pintype "bidirectional"))
      (node (ref "X-SOUTH") (pin "45") (pinfunction "45_45") (pintype "bidirectional"))
    )
    (net (code "247") (name "S12_N") (class "Default")
      (node (ref "U2") (pin "13") (pinfunction "AN10/RF5_13") (pintype "bidirectional"))
      (node (ref "X-SOUTH") (pin "52") (pinfunction "52_52") (pintype "bidirectional"))
    )
    (net (code "248") (name "S12_P") (class "Default")
      (node (ref "U2") (pin "14") (pinfunction "AN9/RF4_14") (pintype "bidirectional"))
      (node (ref "X-SOUTH") (pin "50") (pinfunction "50_50") (pintype "bidirectional"))
    )
    (net (code "249") (name "S13_N") (class "Default")
      (node (ref "U5") (pin "13") (pinfunction "AN10/RF5_13") (pintype "bidirectional"))
      (node (ref "X-SOUTH") (pin "53") (pinfunction "53_53") (pintype "bidirectional"))
    )
    (net (code "250") (name "S13_P") (class "Default")
      (node (ref "U5") (pin "12") (pinfunction "AN11/RF6_12") (pintype "bidirectional"))
      (node (ref "X-SOUTH") (pin "51") (pinfunction "51_51") (pintype "bidirectional"))
    )
    (net (code "251") (name "S14_N") (class "Default")
      (node (ref "U2") (pin "2") (pinfunction "AN27/RE0_2") (pintype "bidirectional"))
      (node (ref "X-SOUTH") (pin "58") (pinfunction "58_58") (pintype "bidirectional"))
    )
    (net (code "252") (name "S14_P") (class "Default")
      (node (ref "U2") (pin "12") (pinfunction "AN11/RF6_12") (pintype "bidirectional"))
      (node (ref "X-SOUTH") (pin "56") (pinfunction "56_56") (pintype "bidirectional"))
    )
    (net (code "253") (name "S15_N") (class "Default")
      (node (ref "U5") (pin "15") (pinfunction "AN8/RF3_15") (pintype "bidirectional"))
      (node (ref "X-SOUTH") (pin "59") (pinfunction "59_59") (pintype "bidirectional"))
    )
    (net (code "254") (name "S15_P") (class "Default")
      (node (ref "U5") (pin "14") (pinfunction "AN9/RF4_14") (pintype "bidirectional"))
      (node (ref "X-SOUTH") (pin "57") (pinfunction "57_57") (pintype "bidirectional"))
    )
    (net (code "255") (name "S16_N") (class "Default")
      (node (ref "U2") (pin "64") (pinfunction "AN29/RE2_64") (pintype "bidirectional"))
      (node (ref "X-SOUTH") (pin "64") (pinfunction "64_64") (pintype "bidirectional"))
    )
    (net (code "256") (name "S16_P") (class "Default")
      (node (ref "U2") (pin "1") (pinfunction "AN28/RE1_1") (pintype "bidirectional"))
      (node (ref "X-SOUTH") (pin "62") (pinfunction "62_62") (pintype "bidirectional"))
    )
    (net (code "257") (name "S17_N") (class "Default")
      (node (ref "U5") (pin "17") (pinfunction "AN6/RF1_17") (pintype "bidirectional"))
      (node (ref "X-SOUTH") (pin "65") (pinfunction "65_65") (pintype "bidirectional"))
    )
    (net (code "258") (name "S17_P") (class "Default")
      (node (ref "U5") (pin "16") (pinfunction "AN7/RF2_16") (pintype "bidirectional"))
      (node (ref "X-SOUTH") (pin "63") (pinfunction "63_63") (pintype "bidirectional"))
    )
    (net (code "259") (name "S18_N") (class "Default")
      (node (ref "U2") (pin "48") (pinfunction "RB0/AN17_48") (pintype "bidirectional"))
      (node (ref "X-SOUTH") (pin "70") (pinfunction "70_70") (pintype "bidirectional"))
    )
    (net (code "260") (name "S18_P") (class "Default")
      (node (ref "U2") (pin "47") (pinfunction "RB1/AN18_47") (pintype "bidirectional"))
      (node (ref "X-SOUTH") (pin "68") (pinfunction "68_68") (pintype "bidirectional"))
    )
    (net (code "261") (name "S19_N") (class "Default")
      (node (ref "U5") (pin "27") (pinfunction "RA5/AN4_27") (pintype "bidirectional"))
      (node (ref "X-SOUTH") (pin "71") (pinfunction "71_71") (pintype "bidirectional"))
    )
    (net (code "262") (name "S19_P") (class "Default")
      (node (ref "U5") (pin "43") (pinfunction "RB5/AN22_43") (pintype "bidirectional"))
      (node (ref "X-SOUTH") (pin "69") (pinfunction "69_69") (pintype "bidirectional"))
    )
    (net (code "263") (name "S20_N") (class "Default")
      (node (ref "U3") (pin "43") (pinfunction "RB5/AN22_43") (pintype "bidirectional"))
      (node (ref "X-SOUTH") (pin "76") (pinfunction "76_76") (pintype "bidirectional"))
    )
    (net (code "264") (name "S20_P") (class "Default")
      (node (ref "U3") (pin "27") (pinfunction "RA5/AN4_27") (pintype "bidirectional"))
      (node (ref "X-SOUTH") (pin "74") (pinfunction "74_74") (pintype "bidirectional"))
    )
    (net (code "265") (name "S21_N") (class "Default")
      (node (ref "U6") (pin "47") (pinfunction "RB1/AN18_47") (pintype "bidirectional"))
      (node (ref "X-SOUTH") (pin "77") (pinfunction "77_77") (pintype "bidirectional"))
    )
    (net (code "266") (name "S21_P") (class "Default")
      (node (ref "U6") (pin "48") (pinfunction "RB0/AN17_48") (pintype "bidirectional"))
      (node (ref "X-SOUTH") (pin "75") (pinfunction "75_75") (pintype "bidirectional"))
    )
    (net (code "267") (name "S22_N") (class "Default")
      (node (ref "U3") (pin "16") (pinfunction "AN7/RF2_16") (pintype "bidirectional"))
      (node (ref "X-SOUTH") (pin "82") (pinfunction "82_82") (pintype "bidirectional"))
    )
    (net (code "268") (name "S22_P") (class "Default")
      (node (ref "U3") (pin "17") (pinfunction "AN6/RF1_17") (pintype "bidirectional"))
      (node (ref "X-SOUTH") (pin "80") (pinfunction "80_80") (pintype "bidirectional"))
    )
    (net (code "269") (name "S23_N") (class "Default")
      (node (ref "U6") (pin "1") (pinfunction "AN28/RE1_1") (pintype "bidirectional"))
      (node (ref "X-SOUTH") (pin "83") (pinfunction "83_83") (pintype "bidirectional"))
    )
    (net (code "270") (name "S23_P") (class "Default")
      (node (ref "U6") (pin "64") (pinfunction "AN29/RE2_64") (pintype "bidirectional"))
      (node (ref "X-SOUTH") (pin "81") (pinfunction "81_81") (pintype "bidirectional"))
    )
    (net (code "271") (name "S24_N") (class "Default")
      (node (ref "U3") (pin "14") (pinfunction "AN9/RF4_14") (pintype "bidirectional"))
      (node (ref "X-SOUTH") (pin "88") (pinfunction "88_88") (pintype "bidirectional"))
    )
    (net (code "272") (name "S24_P") (class "Default")
      (node (ref "U3") (pin "15") (pinfunction "AN8/RF3_15") (pintype "bidirectional"))
      (node (ref "X-SOUTH") (pin "86") (pinfunction "86_86") (pintype "bidirectional"))
    )
    (net (code "273") (name "S25_N") (class "Default")
      (node (ref "U6") (pin "12") (pinfunction "AN11/RF6_12") (pintype "bidirectional"))
      (node (ref "X-SOUTH") (pin "89") (pinfunction "89_89") (pintype "bidirectional"))
    )
    (net (code "274") (name "S25_P") (class "Default")
      (node (ref "U6") (pin "2") (pinfunction "AN27/RE0_2") (pintype "bidirectional"))
      (node (ref "X-SOUTH") (pin "87") (pinfunction "87_87") (pintype "bidirectional"))
    )
    (net (code "275") (name "S26_N") (class "Default")
      (node (ref "U3") (pin "12") (pinfunction "AN11/RF6_12") (pintype "bidirectional"))
      (node (ref "X-SOUTH") (pin "94") (pinfunction "94_94") (pintype "bidirectional"))
    )
    (net (code "276") (name "S26_P") (class "Default")
      (node (ref "U3") (pin "13") (pinfunction "AN10/RF5_13") (pintype "bidirectional"))
      (node (ref "X-SOUTH") (pin "92") (pinfunction "92_92") (pintype "bidirectional"))
    )
    (net (code "277") (name "S27_N") (class "Default")
      (node (ref "U6") (pin "14") (pinfunction "AN9/RF4_14") (pintype "bidirectional"))
      (node (ref "X-SOUTH") (pin "95") (pinfunction "95_95") (pintype "bidirectional"))
    )
    (net (code "278") (name "S27_P") (class "Default")
      (node (ref "U6") (pin "13") (pinfunction "AN10/RF5_13") (pintype "bidirectional"))
      (node (ref "X-SOUTH") (pin "93") (pinfunction "93_93") (pintype "bidirectional"))
    )
    (net (code "279") (name "S28_N") (class "Default")
      (node (ref "U3") (pin "1") (pinfunction "AN28/RE1_1") (pintype "bidirectional"))
      (node (ref "X-SOUTH") (pin "100") (pinfunction "100_100") (pintype "bidirectional"))
    )
    (net (code "280") (name "S28_P") (class "Default")
      (node (ref "U3") (pin "2") (pinfunction "AN27/RE0_2") (pintype "bidirectional"))
      (node (ref "X-SOUTH") (pin "98") (pinfunction "98_98") (pintype "bidirectional"))
    )
    (net (code "281") (name "S29_N") (class "Default")
      (node (ref "U6") (pin "16") (pinfunction "AN7/RF2_16") (pintype "bidirectional"))
      (node (ref "X-SOUTH") (pin "101") (pinfunction "101_101") (pintype "bidirectional"))
    )
    (net (code "282") (name "S29_P") (class "Default")
      (node (ref "U6") (pin "15") (pinfunction "AN8/RF3_15") (pintype "bidirectional"))
      (node (ref "X-SOUTH") (pin "99") (pinfunction "99_99") (pintype "bidirectional"))
    )
    (net (code "283") (name "S30_N") (class "Default")
      (node (ref "U3") (pin "45") (pinfunction "RB3/AN20_45") (pintype "bidirectional"))
      (node (ref "X-SOUTH") (pin "106") (pinfunction "106_106") (pintype "bidirectional"))
    )
    (net (code "284") (name "S30_P") (class "Default")
      (node (ref "U3") (pin "44") (pinfunction "RB4/AN21_44") (pintype "bidirectional"))
      (node (ref "X-SOUTH") (pin "104") (pinfunction "104_104") (pintype "bidirectional"))
    )
    (net (code "285") (name "S31_N") (class "Default")
      (node (ref "U6") (pin "45") (pinfunction "RB3/AN20_45") (pintype "bidirectional"))
      (node (ref "X-SOUTH") (pin "107") (pinfunction "107_107") (pintype "bidirectional"))
    )
    (net (code "286") (name "S31_P") (class "Default")
      (node (ref "U6") (pin "46") (pinfunction "RB2/AN19_46") (pintype "bidirectional"))
      (node (ref "X-SOUTH") (pin "105") (pinfunction "105_105") (pintype "bidirectional"))
    )
    (net (code "287") (name "S32_N") (class "Default")
      (node (ref "U3") (pin "47") (pinfunction "RB1/AN18_47") (pintype "bidirectional"))
      (node (ref "X-SOUTH") (pin "112") (pinfunction "112_112") (pintype "bidirectional"))
    )
    (net (code "288") (name "S32_P") (class "Default")
      (node (ref "U3") (pin "46") (pinfunction "RB2/AN19_46") (pintype "bidirectional"))
      (node (ref "X-SOUTH") (pin "110") (pinfunction "110_110") (pintype "bidirectional"))
    )
    (net (code "289") (name "S33_N") (class "Default")
      (node (ref "U6") (pin "43") (pinfunction "RB5/AN22_43") (pintype "bidirectional"))
      (node (ref "X-SOUTH") (pin "113") (pinfunction "113_113") (pintype "bidirectional"))
    )
    (net (code "290") (name "S33_P") (class "Default")
      (node (ref "U6") (pin "44") (pinfunction "RB4/AN21_44") (pintype "bidirectional"))
      (node (ref "X-SOUTH") (pin "111") (pinfunction "111_111") (pintype "bidirectional"))
    )
    (net (code "291") (name "S34_N") (class "Default")
      (node (ref "U3") (pin "48") (pinfunction "RB0/AN17_48") (pintype "bidirectional"))
      (node (ref "X-SOUTH") (pin "118") (pinfunction "118_118") (pintype "bidirectional"))
    )
    (net (code "292") (name "S34_P") (class "Default")
      (node (ref "U3") (pin "64") (pinfunction "AN29/RE2_64") (pintype "bidirectional"))
      (node (ref "X-SOUTH") (pin "116") (pinfunction "116_116") (pintype "bidirectional"))
    )
    (net (code "293") (name "S35_N") (class "Default")
      (node (ref "U6") (pin "21") (pinfunction "RA3/AN3/REF+_21") (pintype "bidirectional"))
      (node (ref "X-SOUTH") (pin "119") (pinfunction "119_119") (pintype "bidirectional"))
    )
    (net (code "294") (name "S35_P") (class "Default")
      (node (ref "U6") (pin "17") (pinfunction "AN6/RF1_17") (pintype "bidirectional"))
      (node (ref "X-SOUTH") (pin "117") (pinfunction "117_117") (pintype "bidirectional"))
    )
    (net (code "295") (name "S36_N") (class "Default")
      (node (ref "U3") (pin "55") (pinfunction "AN24/RD1_55") (pintype "bidirectional"))
      (node (ref "X-SOUTH") (pin "124") (pinfunction "124_124") (pintype "bidirectional"))
    )
    (net (code "296") (name "S36_P") (class "Default")
      (node (ref "U3") (pin "58") (pinfunction "AN23/RD0_58") (pintype "bidirectional"))
      (node (ref "X-SOUTH") (pin "122") (pinfunction "122_122") (pintype "bidirectional"))
    )
    (net (code "297") (name "S37_N") (class "Default")
      (node (ref "U6") (pin "23") (pinfunction "RA1/AN1_23") (pintype "bidirectional"))
      (node (ref "X-SOUTH") (pin "125") (pinfunction "125_125") (pintype "bidirectional"))
    )
    (net (code "298") (name "S37_P") (class "Default")
      (node (ref "U6") (pin "22") (pinfunction "RA2/AN2_22") (pintype "bidirectional"))
      (node (ref "X-SOUTH") (pin "123") (pinfunction "123_123") (pintype "bidirectional"))
    )
    (net (code "299") (name "S38_N") (class "Default")
      (node (ref "U3") (pin "53") (pinfunction "AN26/RD3_53") (pintype "bidirectional"))
      (node (ref "X-SOUTH") (pin "130") (pinfunction "130_130") (pintype "bidirectional"))
    )
    (net (code "300") (name "S38_P") (class "Default")
      (node (ref "U3") (pin "54") (pinfunction "AN25/RD2_54") (pintype "bidirectional"))
      (node (ref "X-SOUTH") (pin "128") (pinfunction "128_128") (pintype "bidirectional"))
    )
    (net (code "301") (name "S39_N") (class "Default")
      (node (ref "U6") (pin "27") (pinfunction "RA5/AN4_27") (pintype "bidirectional"))
      (node (ref "X-SOUTH") (pin "131") (pinfunction "131_131") (pintype "bidirectional"))
    )
    (net (code "302") (name "S39_P") (class "Default")
      (node (ref "U6") (pin "24") (pinfunction "RA0/AN0_24") (pintype "bidirectional"))
      (node (ref "X-SOUTH") (pin "129") (pinfunction "129_129") (pintype "bidirectional"))
    )
    (net (code "303") (name "SCK2B") (class "Default")
      (node (ref "SPI-EAST") (pin "3") (pinfunction "3_3") (pintype "passive"))
      (node (ref "U2") (pin "50") (pinfunction "SCK2/RD6_50") (pintype "bidirectional"))
    )
    (net (code "304") (name "SCK4B") (class "Default")
      (node (ref "SPI-WEST") (pin "3") (pinfunction "3_3") (pintype "passive"))
      (node (ref "U4") (pin "50") (pinfunction "SCK2/RD6_50") (pintype "bidirectional"))
    )
    (net (code "305") (name "SCL_N") (class "Default")
      (node (ref "R21") (pin "2") (pinfunction "2_2") (pintype "passive"))
      (node (ref "U11") (pin "2") (pinfunction "SCL_2") (pintype "input"))
      (node (ref "U8") (pin "63") (pinfunction "RE3_63") (pintype "bidirectional"))
    )
    (net (code "306") (name "SCL_S") (class "Default")
      (node (ref "R23") (pin "2") (pinfunction "2_2") (pintype "passive"))
      (node (ref "U12") (pin "2") (pinfunction "SCL_2") (pintype "input"))
      (node (ref "U5") (pin "63") (pinfunction "RE3_63") (pintype "bidirectional"))
    )
    (net (code "307") (name "SDA_N") (class "Default")
      (node (ref "R22") (pin "2") (pinfunction "2_2") (pintype "passive"))
      (node (ref "U11") (pin "3") (pinfunction "SDA_3") (pintype "bidirectional"))
      (node (ref "U8") (pin "62") (pinfunction "RE4_62") (pintype "bidirectional"))
    )
    (net (code "308") (name "SDA_S") (class "Default")
      (node (ref "R24") (pin "2") (pinfunction "2_2") (pintype "passive"))
      (node (ref "U12") (pin "3") (pinfunction "SDA_3") (pintype "bidirectional"))
      (node (ref "U5") (pin "62") (pinfunction "RE4_62") (pintype "bidirectional"))
    )
    (net (code "309") (name "SDI2B") (class "Default")
      (node (ref "SPI-EAST") (pin "4") (pinfunction "4_4") (pintype "passive"))
      (node (ref "U2") (pin "51") (pinfunction "SDI2/RD5_51") (pintype "bidirectional"))
    )
    (net (code "310") (name "SDI4B") (class "Default")
      (node (ref "SPI-WEST") (pin "4") (pinfunction "4_4") (pintype "passive"))
      (node (ref "U4") (pin "51") (pinfunction "SDI2/RD5_51") (pintype "bidirectional"))
    )
    (net (code "311") (name "SDO2B") (class "Default")
      (node (ref "SPI-EAST") (pin "5") (pinfunction "5_5") (pintype "passive"))
      (node (ref "U2") (pin "52") (pinfunction "SDO2/RD4_52") (pintype "bidirectional"))
    )
    (net (code "312") (name "SDO4B") (class "Default")
      (node (ref "SPI-WEST") (pin "5") (pinfunction "5_5") (pintype "passive"))
      (node (ref "U4") (pin "52") (pinfunction "SDO2/RD4_52") (pintype "bidirectional"))
    )
    (net (code "313") (name "SDO6B") (class "Default")
      (node (ref "U6") (pin "52") (pinfunction "SDO2/RD4_52") (pintype "bidirectional"))
    )
    (net (code "314") (name "SDO7B") (class "Default")
      (node (ref "U7") (pin "52") (pinfunction "SDO2/RD4_52") (pintype "bidirectional"))
    )
    (net (code "315") (name "SS2B") (class "Default")
      (node (ref "SPI-EAST") (pin "2") (pinfunction "2_2") (pintype "passive"))
      (node (ref "U2") (pin "49") (pinfunction "~{SS2}/RD7_49") (pintype "bidirectional"))
    )
    (net (code "316") (name "SS4B") (class "Default")
      (node (ref "SPI-WEST") (pin "2") (pinfunction "2_2") (pintype "passive"))
      (node (ref "U4") (pin "49") (pinfunction "~{SS2}/RD7_49") (pintype "bidirectional"))
    )
    (net (code "317") (name "SS6B") (class "Default")
      (node (ref "U6") (pin "49") (pinfunction "~{SS2}/RD7_49") (pintype "bidirectional"))
    )
    (net (code "318") (name "SS7B") (class "Default")
      (node (ref "U7") (pin "49") (pinfunction "~{SS2}/RD7_49") (pintype "bidirectional"))
    )
    (net (code "319") (name "S_CHK_EN") (class "Default")
      (node (ref "U2") (pin "29") (pinfunction "RC1_29") (pintype "bidirectional"))
      (node (ref "X-SOUTH") (pin "8") (pinfunction "8_8") (pintype "bidirectional"))
    )
    (net (code "320") (name "S_CHK_V") (class "Default")
      (node (ref "C143") (pin "1") (pinfunction "1_1") (pintype "passive"))
      (node (ref "C144") (pin "1") (pinfunction "1_1") (pintype "passive"))
      (node (ref "PWRS") (pin "2") (pinfunction "2_2") (pintype "passive"))
      (node (ref "R23") (pin "1") (pinfunction "1_1") (pintype "passive"))
      (node (ref "R24") (pin "1") (pinfunction "1_1") (pintype "passive"))
      (node (ref "U12") (pin "1") (pinfunction "VDD_1") (pintype "power_in"))
      (node (ref "X-SOUTH") (pin "10") (pinfunction "10_10") (pintype "bidirectional"))
    )
    (net (code "321") (name "S_I2C_EN") (class "Default")
      (node (ref "U6") (pin "28") (pinfunction "RA4_28") (pintype "bidirectional"))
      (node (ref "X-SOUTH") (pin "137") (pinfunction "137_137") (pintype "bidirectional"))
    )
    (net (code "322") (name "S_I2C_V") (class "Default")
      (node (ref "X-SOUTH") (pin "135") (pinfunction "135_135") (pintype "bidirectional"))
    )
    (net (code "323") (name "S_SCK") (class "Default")
      (node (ref "U3") (pin "50") (pinfunction "SCK2/RD6_50") (pintype "bidirectional"))
      (node (ref "X-SOUTH") (pin "144") (pinfunction "144_144") (pintype "bidirectional"))
    )
    (net (code "324") (name "S_SCL") (class "Default")
      (node (ref "R4") (pin "2") (pinfunction "2_2") (pintype "passive"))
      (node (ref "U6") (pin "50") (pinfunction "SCK2/RD6_50") (pintype "bidirectional"))
      (node (ref "X-SOUTH") (pin "143") (pinfunction "143_143") (pintype "bidirectional"))
    )
    (net (code "325") (name "S_SDA") (class "Default")
      (node (ref "R3") (pin "2") (pinfunction "2_2") (pintype "passive"))
      (node (ref "U6") (pin "51") (pinfunction "SDI2/RD5_51") (pintype "bidirectional"))
      (node (ref "X-SOUTH") (pin "141") (pinfunction "141_141") (pintype "bidirectional"))
    )
    (net (code "326") (name "S_SDI") (class "Default")
      (node (ref "U3") (pin "51") (pinfunction "SDI2/RD5_51") (pintype "bidirectional"))
      (node (ref "X-SOUTH") (pin "140") (pinfunction "140_140") (pintype "bidirectional"))
    )
    (net (code "327") (name "S_SDO") (class "Default")
      (node (ref "U3") (pin "52") (pinfunction "SDO2/RD4_52") (pintype "bidirectional"))
      (node (ref "X-SOUTH") (pin "142") (pinfunction "142_142") (pintype "bidirectional"))
    )
    (net (code "328") (name "S_SPI_EN") (class "Default")
      (node (ref "U3") (pin "49") (pinfunction "~{SS2}/RD7_49") (pintype "bidirectional"))
      (node (ref "X-SOUTH") (pin "136") (pinfunction "136_136") (pintype "bidirectional"))
    )
    (net (code "329") (name "S_SPI_V") (class "Default")
      (node (ref "X-SOUTH") (pin "134") (pinfunction "134_134") (pintype "bidirectional"))
    )
    (net (code "330") (name "S_VE") (class "Default")
      (node (ref "C134") (pin "1") (pinfunction "1_1") (pintype "passive"))
      (node (ref "PWR-SOUTH") (pin "6") (pinfunction "6_6") (pintype "passive"))
      (node (ref "X-SOUTH") (pin "13") (pinfunction "13_13") (pintype "bidirectional"))
      (node (ref "X-SOUTH") (pin "19") (pinfunction "19_19") (pintype "bidirectional"))
      (node (ref "X-SOUTH") (pin "31") (pinfunction "31_31") (pintype "bidirectional"))
      (node (ref "X-SOUTH") (pin "37") (pinfunction "37_37") (pintype "bidirectional"))
    )
    (net (code "331") (name "S_VE_CV") (class "Default")
      (node (ref "U12") (pin "9") (pinfunction "VOUTD_9") (pintype "output"))
      (node (ref "X-SOUTH") (pin "2") (pinfunction "2_2") (pintype "bidirectional"))
    )
    (net (code "332") (name "S_VE_OV") (class "Default")
      (node (ref "U5") (pin "49") (pinfunction "~{SS2}/RD7_49") (pintype "bidirectional"))
      (node (ref "X-SOUTH") (pin "1") (pinfunction "1_1") (pintype "bidirectional"))
    )
    (net (code "333") (name "S_VE_RS") (class "Default")
      (node (ref "X-SOUTH") (pin "25") (pinfunction "25_25") (pintype "bidirectional"))
    )
    (net (code "334") (name "S_VE_UV") (class "Default")
      (node (ref "U5") (pin "59") (pinfunction "RE7_59") (pintype "bidirectional"))
      (node (ref "X-SOUTH") (pin "7") (pinfunction "7_7") (pintype "bidirectional"))
    )
    (net (code "335") (name "S_VS") (class "Default")
      (node (ref "C135") (pin "1") (pinfunction "1_1") (pintype "passive"))
      (node (ref "PWR-SOUTH") (pin "4") (pinfunction "4_4") (pintype "passive"))
      (node (ref "X-SOUTH") (pin "49") (pinfunction "49_49") (pintype "bidirectional"))
      (node (ref "X-SOUTH") (pin "55") (pinfunction "55_55") (pintype "bidirectional"))
      (node (ref "X-SOUTH") (pin "61") (pinfunction "61_61") (pintype "bidirectional"))
      (node (ref "X-SOUTH") (pin "67") (pinfunction "67_67") (pintype "bidirectional"))
      (node (ref "X-SOUTH") (pin "79") (pinfunction "79_79") (pintype "bidirectional"))
      (node (ref "X-SOUTH") (pin "85") (pinfunction "85_85") (pintype "bidirectional"))
      (node (ref "X-SOUTH") (pin "91") (pinfunction "91_91") (pintype "bidirectional"))
      (node (ref "X-SOUTH") (pin "97") (pinfunction "97_97") (pintype "bidirectional"))
    )
    (net (code "336") (name "S_VS_CV") (class "Default")
      (node (ref "U12") (pin "8") (pinfunction "VOUTC_8") (pintype "output"))
      (node (ref "X-SOUTH") (pin "4") (pinfunction "4_4") (pintype "bidirectional"))
    )
    (net (code "337") (name "S_VS_OV") (class "Default")
      (node (ref "U5") (pin "50") (pinfunction "SCK2/RD6_50") (pintype "bidirectional"))
      (node (ref "X-SOUTH") (pin "3") (pinfunction "3_3") (pintype "bidirectional"))
    )
    (net (code "338") (name "S_VS_RS") (class "Default")
      (node (ref "X-SOUTH") (pin "73") (pinfunction "73_73") (pintype "bidirectional"))
    )
    (net (code "339") (name "S_VS_UV") (class "Default")
      (node (ref "U5") (pin "60") (pinfunction "RE6_60") (pintype "bidirectional"))
      (node (ref "X-SOUTH") (pin "9") (pinfunction "9_9") (pintype "bidirectional"))
    )
    (net (code "340") (name "S_VW") (class "Default")
      (node (ref "C136") (pin "1") (pinfunction "1_1") (pintype "passive"))
      (node (ref "PWR-SOUTH") (pin "2") (pinfunction "2_2") (pintype "passive"))
      (node (ref "X-SOUTH") (pin "109") (pinfunction "109_109") (pintype "bidirectional"))
      (node (ref "X-SOUTH") (pin "115") (pinfunction "115_115") (pintype "bidirectional"))
      (node (ref "X-SOUTH") (pin "127") (pinfunction "127_127") (pintype "bidirectional"))
      (node (ref "X-SOUTH") (pin "133") (pinfunction "133_133") (pintype "bidirectional"))
    )
    (net (code "341") (name "S_VW_CV") (class "Default")
      (node (ref "U12") (pin "7") (pinfunction "VOUTB_7") (pintype "output"))
      (node (ref "X-SOUTH") (pin "6") (pinfunction "6_6") (pintype "bidirectional"))
    )
    (net (code "342") (name "S_VW_OV") (class "Default")
      (node (ref "U5") (pin "51") (pinfunction "SDI2/RD5_51") (pintype "bidirectional"))
      (node (ref "X-SOUTH") (pin "5") (pinfunction "5_5") (pintype "bidirectional"))
    )
    (net (code "343") (name "S_VW_RS") (class "Default")
      (node (ref "X-SOUTH") (pin "121") (pinfunction "121_121") (pintype "bidirectional"))
    )
    (net (code "344") (name "S_VW_UV") (class "Default")
      (node (ref "U5") (pin "61") (pinfunction "RE5_61") (pintype "bidirectional"))
      (node (ref "X-SOUTH") (pin "11") (pinfunction "11_11") (pintype "bidirectional"))
    )
    (net (code "345") (name "TX1") (class "Default")
      (node (ref "SER1") (pin "2") (pinfunction "2_2") (pintype "passive"))
      (node (ref "U1") (pin "31") (pinfunction "RC6/TX1_31") (pintype "bidirectional"))
    )
    (net (code "346") (name "TX1B") (class "Default")
      (node (ref "U1") (pin "4") (pinfunction "TX2/AN15/RG1_4") (pintype "bidirectional"))
    )
    (net (code "347") (name "TX2") (class "Default")
      (node (ref "SER2") (pin "2") (pinfunction "2_2") (pintype "passive"))
      (node (ref "U2") (pin "31") (pinfunction "RC6/TX1_31") (pintype "bidirectional"))
    )
    (net (code "348") (name "TX2B") (class "Default")
      (node (ref "U2") (pin "4") (pinfunction "TX2/AN15/RG1_4") (pintype "bidirectional"))
    )
    (net (code "349") (name "TX3") (class "Default")
      (node (ref "SER3") (pin "2") (pinfunction "2_2") (pintype "passive"))
      (node (ref "U3") (pin "31") (pinfunction "RC6/TX1_31") (pintype "bidirectional"))
    )
    (net (code "350") (name "TX3B") (class "Default")
      (node (ref "U3") (pin "4") (pinfunction "TX2/AN15/RG1_4") (pintype "bidirectional"))
    )
    (net (code "351") (name "TX4") (class "Default")
      (node (ref "SER4") (pin "2") (pinfunction "2_2") (pintype "passive"))
      (node (ref "U4") (pin "31") (pinfunction "RC6/TX1_31") (pintype "bidirectional"))
    )
    (net (code "352") (name "TX4B") (class "Default")
      (node (ref "U4") (pin "4") (pinfunction "TX2/AN15/RG1_4") (pintype "bidirectional"))
    )
    (net (code "353") (name "TX5") (class "Default")
      (node (ref "SER5") (pin "2") (pinfunction "2_2") (pintype "passive"))
      (node (ref "U5") (pin "31") (pinfunction "RC6/TX1_31") (pintype "bidirectional"))
    )
    (net (code "354") (name "TX5B") (class "Default")
      (node (ref "U5") (pin "4") (pinfunction "TX2/AN15/RG1_4") (pintype "bidirectional"))
    )
    (net (code "355") (name "TX6") (class "Default")
      (node (ref "SER6") (pin "2") (pinfunction "2_2") (pintype "passive"))
      (node (ref "U6") (pin "31") (pinfunction "RC6/TX1_31") (pintype "bidirectional"))
    )
    (net (code "356") (name "TX6B") (class "Default")
      (node (ref "U6") (pin "4") (pinfunction "TX2/AN15/RG1_4") (pintype "bidirectional"))
    )
    (net (code "357") (name "TX7") (class "Default")
      (node (ref "SER7") (pin "2") (pinfunction "2_2") (pintype "passive"))
      (node (ref "U7") (pin "31") (pinfunction "RC6/TX1_31") (pintype "bidirectional"))
    )
    (net (code "358") (name "TX7B") (class "Default")
      (node (ref "U7") (pin "4") (pinfunction "TX2/AN15/RG1_4") (pintype "bidirectional"))
    )
    (net (code "359") (name "TX8") (class "Default")
      (node (ref "SER8") (pin "2") (pinfunction "2_2") (pintype "passive"))
      (node (ref "U8") (pin "31") (pinfunction "RC6/TX1_31") (pintype "bidirectional"))
    )
    (net (code "360") (name "TX8B") (class "Default")
      (node (ref "U8") (pin "4") (pinfunction "TX2/AN15/RG1_4") (pintype "bidirectional"))
    )
    (net (code "361") (name "VCC") (class "Default")
      (node (ref "C10") (pin "1") (pinfunction "1_1") (pintype "passive"))
      (node (ref "C100") (pin "1") (pinfunction "1_1") (pintype "passive"))
      (node (ref "C13") (pin "1") (pinfunction "1_1") (pintype "passive"))
      (node (ref "C133") (pin "1") (pinfunction "1_1") (pintype "passive"))
      (node (ref "C137") (pin "1") (pinfunction "1_1") (pintype "passive"))
      (node (ref "C14") (pin "1") (pinfunction "1_1") (pintype "passive"))
      (node (ref "C15") (pin "1") (pinfunction "1_1") (pintype "passive"))
      (node (ref "C16") (pin "1") (pinfunction "1_1") (pintype "passive"))
      (node (ref "C18") (pin "1") (pinfunction "1_1") (pintype "passive"))
      (node (ref "C19") (pin "1") (pinfunction "1_1") (pintype "passive"))
      (node (ref "C2") (pin "1") (pinfunction "1_1") (pintype "passive"))
      (node (ref "C20") (pin "1") (pinfunction "1_1") (pintype "passive"))
      (node (ref "C21") (pin "1") (pinfunction "1_1") (pintype "passive"))
      (node (ref "C24") (pin "1") (pinfunction "1_1") (pintype "passive"))
      (node (ref "C25") (pin "1") (pinfunction "1_1") (pintype "passive"))
      (node (ref "C26") (pin "1") (pinfunction "1_1") (pintype "passive"))
      (node (ref "C27") (pin "1") (pinfunction "1_1") (pintype "passive"))
      (node (ref "C29") (pin "1") (pinfunction "1_1") (pintype "passive"))
      (node (ref "C3") (pin "1") (pinfunction "1_1") (pintype "passive"))
      (node (ref "C30") (pin "1") (pinfunction "1_1") (pintype "passive"))
      (node (ref "C31") (pin "1") (pinfunction "1_1") (pintype "passive"))
      (node (ref "C32") (pin "1") (pinfunction "1_1") (pintype "passive"))
      (node (ref "C35") (pin "1") (pinfunction "1_1") (pintype "passive"))
      (node (ref "C36") (pin "1") (pinfunction "1_1") (pintype "passive"))
      (node (ref "C37") (pin "1") (pinfunction "1_1") (pintype "passive"))
      (node (ref "C38") (pin "1") (pinfunction "1_1") (pintype "passive"))
      (node (ref "C4") (pin "1") (pinfunction "1_1") (pintype "passive"))
      (node (ref "C40") (pin "1") (pinfunction "1_1") (pintype "passive"))
      (node (ref "C41") (pin "1") (pinfunction "1_1") (pintype "passive"))
      (node (ref "C42") (pin "1") (pinfunction "1_1") (pintype "passive"))
      (node (ref "C43") (pin "1") (pinfunction "1_1") (pintype "passive"))
      (node (ref "C46") (pin "1") (pinfunction "1_1") (pintype "passive"))
      (node (ref "C47") (pin "1") (pinfunction "1_1") (pintype "passive"))
      (node (ref "C48") (pin "1") (pinfunction "1_1") (pintype "passive"))
      (node (ref "C49") (pin "1") (pinfunction "1_1") (pintype "passive"))
      (node (ref "C5") (pin "1") (pinfunction "1_1") (pintype "passive"))
      (node (ref "C51") (pin "1") (pinfunction "1_1") (pintype "passive"))
      (node (ref "C52") (pin "1") (pinfunction "1_1") (pintype "passive"))
      (node (ref "C53") (pin "1") (pinfunction "1_1") (pintype "passive"))
      (node (ref "C54") (pin "1") (pinfunction "1_1") (pintype "passive"))
      (node (ref "C57") (pin "1") (pinfunction "1_1") (pintype "passive"))
      (node (ref "C58") (pin "1") (pinfunction "1_1") (pintype "passive"))
      (node (ref "C59") (pin "1") (pinfunction "1_1") (pintype "passive"))
      (node (ref "C60") (pin "1") (pinfunction "1_1") (pintype "passive"))
      (node (ref "C62") (pin "1") (pinfunction "1_1") (pintype "passive"))
      (node (ref "C63") (pin "1") (pinfunction "1_1") (pintype "passive"))
      (node (ref "C64") (pin "1") (pinfunction "1_1") (pintype "passive"))
      (node (ref "C65") (pin "1") (pinfunction "1_1") (pintype "passive"))
      (node (ref "C68") (pin "1") (pinfunction "1_1") (pintype "passive"))
      (node (ref "C69") (pin "1") (pinfunction "1_1") (pintype "passive"))
      (node (ref "C7") (pin "1") (pinfunction "1_1") (pintype "passive"))
      (node (ref "C70") (pin "1") (pinfunction "1_1") (pintype "passive"))
      (node (ref "C71") (pin "1") (pinfunction "1_1") (pintype "passive"))
      (node (ref "C73") (pin "1") (pinfunction "1_1") (pintype "passive"))
      (node (ref "C74") (pin "1") (pinfunction "1_1") (pintype "passive"))
      (node (ref "C75") (pin "1") (pinfunction "1_1") (pintype "passive"))
      (node (ref "C76") (pin "1") (pinfunction "1_1") (pintype "passive"))
      (node (ref "C79") (pin "1") (pinfunction "1_1") (pintype "passive"))
      (node (ref "C8") (pin "1") (pinfunction "1_1") (pintype "passive"))
      (node (ref "C80") (pin "1") (pinfunction "1_1") (pintype "passive"))
      (node (ref "C81") (pin "1") (pinfunction "1_1") (pintype "passive"))
      (node (ref "C82") (pin "1") (pinfunction "1_1") (pintype "passive"))
      (node (ref "C84") (pin "1") (pinfunction "1_1") (pintype "passive"))
      (node (ref "C85") (pin "1") (pinfunction "1_1") (pintype "passive"))
      (node (ref "C86") (pin "1") (pinfunction "1_1") (pintype "passive"))
      (node (ref "C87") (pin "1") (pinfunction "1_1") (pintype "passive"))
      (node (ref "C89") (pin "1") (pinfunction "1_1") (pintype "passive"))
      (node (ref "C9") (pin "1") (pinfunction "1_1") (pintype "passive"))
      (node (ref "C90") (pin "1") (pinfunction "1_1") (pintype "passive"))
      (node (ref "C91") (pin "1") (pinfunction "1_1") (pintype "passive"))
      (node (ref "C92") (pin "1") (pinfunction "1_1") (pintype "passive"))
      (node (ref "C93") (pin "1") (pinfunction "1_1") (pintype "passive"))
      (node (ref "C94") (pin "1") (pinfunction "1_1") (pintype "passive"))
      (node (ref "C95") (pin "1") (pinfunction "1_1") (pintype "passive"))
      (node (ref "C96") (pin "1") (pinfunction "1_1") (pintype "passive"))
      (node (ref "C97") (pin "1") (pinfunction "1_1") (pintype "passive"))
      (node (ref "C98") (pin "1") (pinfunction "1_1") (pintype "passive"))
      (node (ref "C99") (pin "1") (pinfunction "1_1") (pintype "passive"))
      (node (ref "L1") (pin "1") (pinfunction "1_1") (pintype "passive"))
      (node (ref "L2") (pin "1") (pinfunction "1_1") (pintype "passive"))
      (node (ref "L3") (pin "1") (pinfunction "1_1") (pintype "passive"))
      (node (ref "L4") (pin "1") (pinfunction "1_1") (pintype "passive"))
      (node (ref "L5") (pin "1") (pinfunction "1_1") (pintype "passive"))
      (node (ref "L6") (pin "1") (pinfunction "1_1") (pintype "passive"))
      (node (ref "L7") (pin "1") (pinfunction "1_1") (pintype "passive"))
      (node (ref "L8") (pin "1") (pinfunction "1_1") (pintype "passive"))
      (node (ref "R1") (pin "1") (pinfunction "1_1") (pintype "passive"))
      (node (ref "R10") (pin "1") (pinfunction "1_1") (pintype "passive"))
      (node (ref "R11") (pin "1") (pinfunction "1_1") (pintype "passive"))
      (node (ref "R12") (pin "1") (pinfunction "1_1") (pintype "passive"))
      (node (ref "R13") (pin "1") (pinfunction "1_1") (pintype "passive"))
      (node (ref "R14") (pin "1") (pinfunction "1_1") (pintype "passive"))
      (node (ref "R15") (pin "1") (pinfunction "1_1") (pintype "passive"))
      (node (ref "R16") (pin "1") (pinfunction "1_1") (pintype "passive"))
      (node (ref "R17") (pin "1") (pinfunction "1_1") (pintype "passive"))
      (node (ref "R18") (pin "1") (pinfunction "1_1") (pintype "passive"))
      (node (ref "R19") (pin "1") (pinfunction "1_1") (pintype "passive"))
      (node (ref "R2") (pin "1") (pinfunction "1_1") (pintype "passive"))
      (node (ref "R20") (pin "1") (pinfunction "1_1") (pintype "passive"))
      (node (ref "R3") (pin "1") (pinfunction "1_1") (pintype "passive"))
      (node (ref "R4") (pin "1") (pinfunction "1_1") (pintype "passive"))
      (node (ref "R5") (pin "1") (pinfunction "1_1") (pintype "passive"))
      (node (ref "R6") (pin "1") (pinfunction "1_1") (pintype "passive"))
      (node (ref "R7") (pin "1") (pinfunction "1_1") (pintype "passive"))
      (node (ref "R8") (pin "1") (pinfunction "1_1") (pintype "passive"))
      (node (ref "R9") (pin "1") (pinfunction "1_1") (pintype "passive"))
      (node (ref "SPI-EAST") (pin "6") (pinfunction "6_6") (pintype "passive"))
      (node (ref "SPI-WEST") (pin "6") (pinfunction "6_6") (pintype "passive"))
      (node (ref "SUP-N") (pin "2") (pinfunction "2_2") (pintype "passive"))
      (node (ref "SUP-S") (pin "2") (pinfunction "2_2") (pintype "passive"))
      (node (ref "U1") (pin "10") (pinfunction "VDD_10") (pintype "power_in"))
      (node (ref "U1") (pin "26") (pinfunction "VDD_26") (pintype "power_in"))
      (node (ref "U1") (pin "38") (pinfunction "VDD_38") (pintype "power_in"))
      (node (ref "U1") (pin "57") (pinfunction "VDD_57") (pintype "power_in"))
      (node (ref "U10") (pin "1") (pinfunction "EN_1") (pintype "bidirectional"))
      (node (ref "U10") (pin "4") (pinfunction "VCC_4") (pintype "bidirectional"))
      (node (ref "U2") (pin "10") (pinfunction "VDD_10") (pintype "power_in"))
      (node (ref "U2") (pin "26") (pinfunction "VDD_26") (pintype "power_in"))
      (node (ref "U2") (pin "38") (pinfunction "VDD_38") (pintype "power_in"))
      (node (ref "U2") (pin "57") (pinfunction "VDD_57") (pintype "power_in"))
      (node (ref "U3") (pin "10") (pinfunction "VDD_10") (pintype "power_in"))
      (node (ref "U3") (pin "26") (pinfunction "VDD_26") (pintype "power_in"))
      (node (ref "U3") (pin "38") (pinfunction "VDD_38") (pintype "power_in"))
      (node (ref "U3") (pin "57") (pinfunction "VDD_57") (pintype "power_in"))
      (node (ref "U4") (pin "10") (pinfunction "VDD_10") (pintype "power_in"))
      (node (ref "U4") (pin "26") (pinfunction "VDD_26") (pintype "power_in"))
      (node (ref "U4") (pin "38") (pinfunction "VDD_38") (pintype "power_in"))
      (node (ref "U4") (pin "57") (pinfunction "VDD_57") (pintype "power_in"))
      (node (ref "U5") (pin "10") (pinfunction "VDD_10") (pintype "power_in"))
      (node (ref "U5") (pin "26") (pinfunction "VDD_26") (pintype "power_in"))
      (node (ref "U5") (pin "38") (pinfunction "VDD_38") (pintype "power_in"))
      (node (ref "U5") (pin "57") (pinfunction "VDD_57") (pintype "power_in"))
      (node (ref "U6") (pin "10") (pinfunction "VDD_10") (pintype "power_in"))
      (node (ref "U6") (pin "26") (pinfunction "VDD_26") (pintype "power_in"))
      (node (ref "U6") (pin "38") (pinfunction "VDD_38") (pintype "power_in"))
      (node (ref "U6") (pin "57") (pinfunction "VDD_57") (pintype "power_in"))
      (node (ref "U7") (pin "10") (pinfunction "VDD_10") (pintype "power_in"))
      (node (ref "U7") (pin "26") (pinfunction "VDD_26") (pintype "power_in"))
      (node (ref "U7") (pin "38") (pinfunction "VDD_38") (pintype "power_in"))
      (node (ref "U7") (pin "57") (pinfunction "VDD_57") (pintype "power_in"))
      (node (ref "U8") (pin "10") (pinfunction "VDD_10") (pintype "power_in"))
      (node (ref "U8") (pin "26") (pinfunction "VDD_26") (pintype "power_in"))
      (node (ref "U8") (pin "38") (pinfunction "VDD_38") (pintype "power_in"))
      (node (ref "U8") (pin "57") (pinfunction "VDD_57") (pintype "power_in"))
      (node (ref "U9") (pin "10") (pinfunction "VCC_10") (pintype "power_in"))
      (node (ref "U9") (pin "14") (pinfunction "VCC_14") (pintype "power_in"))
      (node (ref "U9") (pin "2") (pinfunction "OE_2") (pintype "input"))
      (node (ref "U9") (pin "5") (pinfunction "VCC_5") (pintype "power_in"))
    )
    (net (code "362") (name "W_SCK") (class "Default")
      (node (ref "U3") (pin "34") (pinfunction "RC3/SCK1_34") (pintype "bidirectional"))
      (node (ref "U4") (pin "34") (pinfunction "RC3/SCK1_34") (pintype "bidirectional"))
      (node (ref "U6") (pin "34") (pinfunction "RC3/SCK1_34") (pintype "bidirectional"))
      (node (ref "U8") (pin "34") (pinfunction "RC3/SCK1_34") (pintype "bidirectional"))
    )
    (net (code "363") (name "W_SD_36") (class "Default")
      (node (ref "U3") (pin "36") (pinfunction "RC5/SDO1_36") (pintype "bidirectional"))
      (node (ref "U6") (pin "35") (pinfunction "RC4/SDI1_35") (pintype "bidirectional"))
    )
    (net (code "364") (name "W_SD_43") (class "Default")
      (node (ref "U3") (pin "35") (pinfunction "RC4/SDI1_35") (pintype "bidirectional"))
      (node (ref "U4") (pin "36") (pinfunction "RC5/SDO1_36") (pintype "bidirectional"))
    )
    (net (code "365") (name "W_SD_68") (class "Default")
      (node (ref "U6") (pin "36") (pinfunction "RC5/SDO1_36") (pintype "bidirectional"))
      (node (ref "U8") (pin "35") (pinfunction "RC4/SDI1_35") (pintype "bidirectional"))
    )
    (net (code "366") (name "W_SD_84") (class "Default")
      (node (ref "U4") (pin "35") (pinfunction "RC4/SDI1_35") (pintype "bidirectional"))
      (node (ref "U8") (pin "36") (pinfunction "RC5/SDO1_36") (pintype "bidirectional"))
    )
    (net (code "367") (name "unconnected-(U1-AN12{slash}RG4-Pad8)") (class "Default")
      (node (ref "U1") (pin "8") (pinfunction "AN12/RG4_8") (pintype "bidirectional"))
    )
    (net (code "368") (name "unconnected-(U1-AN13{slash}RG3-Pad6)") (class "Default")
      (node (ref "U1") (pin "6") (pinfunction "AN13/RG3_6") (pintype "bidirectional"))
    )
    (net (code "369") (name "unconnected-(U1-RA4-Pad28)") (class "Default")
      (node (ref "U1") (pin "28") (pinfunction "RA4_28") (pintype "bidirectional"))
    )
    (net (code "370") (name "unconnected-(U1-RA6-Pad40)") (class "Default")
      (node (ref "U1") (pin "40") (pinfunction "RA6_40") (pintype "bidirectional"))
    )
    (net (code "371") (name "unconnected-(U1-RC0-Pad30)") (class "Default")
      (node (ref "U1") (pin "30") (pinfunction "RC0_30") (pintype "bidirectional"))
    )
    (net (code "372") (name "unconnected-(U1-RC1-Pad29)") (class "Default")
      (node (ref "U1") (pin "29") (pinfunction "RC1_29") (pintype "bidirectional"))
    )
    (net (code "373") (name "unconnected-(U1-RE3-Pad63)") (class "Default")
      (node (ref "U1") (pin "63") (pinfunction "RE3_63") (pintype "bidirectional"))
    )
    (net (code "374") (name "unconnected-(U1-RE4-Pad62)") (class "Default")
      (node (ref "U1") (pin "62") (pinfunction "RE4_62") (pintype "bidirectional"))
    )
    (net (code "375") (name "unconnected-(U1-RG0-Pad3)") (class "Default")
      (node (ref "U1") (pin "3") (pinfunction "RG0_3") (pintype "bidirectional"))
    )
    (net (code "376") (name "unconnected-(U2-AN12{slash}RG4-Pad8)") (class "Default")
      (node (ref "U2") (pin "8") (pinfunction "AN12/RG4_8") (pintype "bidirectional"))
    )
    (net (code "377") (name "unconnected-(U2-AN13{slash}RG3-Pad6)") (class "Default")
      (node (ref "U2") (pin "6") (pinfunction "AN13/RG3_6") (pintype "bidirectional"))
    )
    (net (code "378") (name "unconnected-(U2-RA4-Pad28)") (class "Default")
      (node (ref "U2") (pin "28") (pinfunction "RA4_28") (pintype "bidirectional"))
    )
    (net (code "379") (name "unconnected-(U2-RA6-Pad40)") (class "Default")
      (node (ref "U2") (pin "40") (pinfunction "RA6_40") (pintype "bidirectional"))
    )
    (net (code "380") (name "unconnected-(U2-RC0-Pad30)") (class "Default")
      (node (ref "U2") (pin "30") (pinfunction "RC0_30") (pintype "bidirectional"))
    )
    (net (code "381") (name "unconnected-(U2-RE3-Pad63)") (class "Default")
      (node (ref "U2") (pin "63") (pinfunction "RE3_63") (pintype "bidirectional"))
    )
    (net (code "382") (name "unconnected-(U2-RE4-Pad62)") (class "Default")
      (node (ref "U2") (pin "62") (pinfunction "RE4_62") (pintype "bidirectional"))
    )
    (net (code "383") (name "unconnected-(U2-RE5-Pad61)") (class "Default")
      (node (ref "U2") (pin "61") (pinfunction "RE5_61") (pintype "bidirectional"))
    )
    (net (code "384") (name "unconnected-(U2-RE6-Pad60)") (class "Default")
      (node (ref "U2") (pin "60") (pinfunction "RE6_60") (pintype "bidirectional"))
    )
    (net (code "385") (name "unconnected-(U2-RE7-Pad59)") (class "Default")
      (node (ref "U2") (pin "59") (pinfunction "RE7_59") (pintype "bidirectional"))
    )
    (net (code "386") (name "unconnected-(U2-RG0-Pad3)") (class "Default")
      (node (ref "U2") (pin "3") (pinfunction "RG0_3") (pintype "bidirectional"))
    )
    (net (code "387") (name "unconnected-(U3-AN12{slash}RG4-Pad8)") (class "Default")
      (node (ref "U3") (pin "8") (pinfunction "AN12/RG4_8") (pintype "bidirectional"))
    )
    (net (code "388") (name "unconnected-(U3-AN13{slash}RG3-Pad6)") (class "Default")
      (node (ref "U3") (pin "6") (pinfunction "AN13/RG3_6") (pintype "bidirectional"))
    )
    (net (code "389") (name "unconnected-(U3-RA4-Pad28)") (class "Default")
      (node (ref "U3") (pin "28") (pinfunction "RA4_28") (pintype "bidirectional"))
    )
    (net (code "390") (name "unconnected-(U3-RA6-Pad40)") (class "Default")
      (node (ref "U3") (pin "40") (pinfunction "RA6_40") (pintype "bidirectional"))
    )
    (net (code "391") (name "unconnected-(U3-RC0-Pad30)") (class "Default")
      (node (ref "U3") (pin "30") (pinfunction "RC0_30") (pintype "bidirectional"))
    )
    (net (code "392") (name "unconnected-(U3-RC1-Pad29)") (class "Default")
      (node (ref "U3") (pin "29") (pinfunction "RC1_29") (pintype "bidirectional"))
    )
    (net (code "393") (name "unconnected-(U3-RE3-Pad63)") (class "Default")
      (node (ref "U3") (pin "63") (pinfunction "RE3_63") (pintype "bidirectional"))
    )
    (net (code "394") (name "unconnected-(U3-RE4-Pad62)") (class "Default")
      (node (ref "U3") (pin "62") (pinfunction "RE4_62") (pintype "bidirectional"))
    )
    (net (code "395") (name "unconnected-(U3-RE5-Pad61)") (class "Default")
      (node (ref "U3") (pin "61") (pinfunction "RE5_61") (pintype "bidirectional"))
    )
    (net (code "396") (name "unconnected-(U3-RE6-Pad60)") (class "Default")
      (node (ref "U3") (pin "60") (pinfunction "RE6_60") (pintype "bidirectional"))
    )
    (net (code "397") (name "unconnected-(U3-RE7-Pad59)") (class "Default")
      (node (ref "U3") (pin "59") (pinfunction "RE7_59") (pintype "bidirectional"))
    )
    (net (code "398") (name "unconnected-(U3-RG0-Pad3)") (class "Default")
      (node (ref "U3") (pin "3") (pinfunction "RG0_3") (pintype "bidirectional"))
    )
    (net (code "399") (name "unconnected-(U4-AN12{slash}RG4-Pad8)") (class "Default")
      (node (ref "U4") (pin "8") (pinfunction "AN12/RG4_8") (pintype "bidirectional"))
    )
    (net (code "400") (name "unconnected-(U4-AN13{slash}RG3-Pad6)") (class "Default")
      (node (ref "U4") (pin "6") (pinfunction "AN13/RG3_6") (pintype "bidirectional"))
    )
    (net (code "401") (name "unconnected-(U4-RA4-Pad28)") (class "Default")
      (node (ref "U4") (pin "28") (pinfunction "RA4_28") (pintype "bidirectional"))
    )
    (net (code "402") (name "unconnected-(U4-RA6-Pad40)") (class "Default")
      (node (ref "U4") (pin "40") (pinfunction "RA6_40") (pintype "bidirectional"))
    )
    (net (code "403") (name "unconnected-(U4-RC0-Pad30)") (class "Default")
      (node (ref "U4") (pin "30") (pinfunction "RC0_30") (pintype "bidirectional"))
    )
    (net (code "404") (name "unconnected-(U4-RE3-Pad63)") (class "Default")
      (node (ref "U4") (pin "63") (pinfunction "RE3_63") (pintype "bidirectional"))
    )
    (net (code "405") (name "unconnected-(U4-RE4-Pad62)") (class "Default")
      (node (ref "U4") (pin "62") (pinfunction "RE4_62") (pintype "bidirectional"))
    )
    (net (code "406") (name "unconnected-(U4-RE5-Pad61)") (class "Default")
      (node (ref "U4") (pin "61") (pinfunction "RE5_61") (pintype "bidirectional"))
    )
    (net (code "407") (name "unconnected-(U4-RE6-Pad60)") (class "Default")
      (node (ref "U4") (pin "60") (pinfunction "RE6_60") (pintype "bidirectional"))
    )
    (net (code "408") (name "unconnected-(U4-RE7-Pad59)") (class "Default")
      (node (ref "U4") (pin "59") (pinfunction "RE7_59") (pintype "bidirectional"))
    )
    (net (code "409") (name "unconnected-(U4-RG0-Pad3)") (class "Default")
      (node (ref "U4") (pin "3") (pinfunction "RG0_3") (pintype "bidirectional"))
    )
    (net (code "410") (name "unconnected-(U5-AN12{slash}RG4-Pad8)") (class "Default")
      (node (ref "U5") (pin "8") (pinfunction "AN12/RG4_8") (pintype "bidirectional"))
    )
    (net (code "411") (name "unconnected-(U5-AN13{slash}RG3-Pad6)") (class "Default")
      (node (ref "U5") (pin "6") (pinfunction "AN13/RG3_6") (pintype "bidirectional"))
    )
    (net (code "412") (name "unconnected-(U5-RA4-Pad28)") (class "Default")
      (node (ref "U5") (pin "28") (pinfunction "RA4_28") (pintype "bidirectional"))
    )
    (net (code "413") (name "unconnected-(U5-RA6-Pad40)") (class "Default")
      (node (ref "U5") (pin "40") (pinfunction "RA6_40") (pintype "bidirectional"))
    )
    (net (code "414") (name "unconnected-(U5-RG0-Pad3)") (class "Default")
      (node (ref "U5") (pin "3") (pinfunction "RG0_3") (pintype "bidirectional"))
    )
    (net (code "415") (name "unconnected-(U6-AN12{slash}RG4-Pad8)") (class "Default")
      (node (ref "U6") (pin "8") (pinfunction "AN12/RG4_8") (pintype "bidirectional"))
    )
    (net (code "416") (name "unconnected-(U6-AN13{slash}RG3-Pad6)") (class "Default")
      (node (ref "U6") (pin "6") (pinfunction "AN13/RG3_6") (pintype "bidirectional"))
    )
    (net (code "417") (name "unconnected-(U6-RA6-Pad40)") (class "Default")
      (node (ref "U6") (pin "40") (pinfunction "RA6_40") (pintype "bidirectional"))
    )
    (net (code "418") (name "unconnected-(U6-RC0-Pad30)") (class "Default")
      (node (ref "U6") (pin "30") (pinfunction "RC0_30") (pintype "bidirectional"))
    )
    (net (code "419") (name "unconnected-(U6-RC1-Pad29)") (class "Default")
      (node (ref "U6") (pin "29") (pinfunction "RC1_29") (pintype "bidirectional"))
    )
    (net (code "420") (name "unconnected-(U6-RE3-Pad63)") (class "Default")
      (node (ref "U6") (pin "63") (pinfunction "RE3_63") (pintype "bidirectional"))
    )
    (net (code "421") (name "unconnected-(U6-RE6-Pad60)") (class "Default")
      (node (ref "U6") (pin "60") (pinfunction "RE6_60") (pintype "bidirectional"))
    )
    (net (code "422") (name "unconnected-(U6-RE7-Pad59)") (class "Default")
      (node (ref "U6") (pin "59") (pinfunction "RE7_59") (pintype "bidirectional"))
    )
    (net (code "423") (name "unconnected-(U6-RG0-Pad3)") (class "Default")
      (node (ref "U6") (pin "3") (pinfunction "RG0_3") (pintype "bidirectional"))
    )
    (net (code "424") (name "unconnected-(U7-AN12{slash}RG4-Pad8)") (class "Default")
      (node (ref "U7") (pin "8") (pinfunction "AN12/RG4_8") (pintype "bidirectional"))
    )
    (net (code "425") (name "unconnected-(U7-AN13{slash}RG3-Pad6)") (class "Default")
      (node (ref "U7") (pin "6") (pinfunction "AN13/RG3_6") (pintype "bidirectional"))
    )
    (net (code "426") (name "unconnected-(U7-RA6-Pad40)") (class "Default")
      (node (ref "U7") (pin "40") (pinfunction "RA6_40") (pintype "bidirectional"))
    )
    (net (code "427") (name "unconnected-(U7-RC0-Pad30)") (class "Default")
      (node (ref "U7") (pin "30") (pinfunction "RC0_30") (pintype "bidirectional"))
    )
    (net (code "428") (name "unconnected-(U7-RC1-Pad29)") (class "Default")
      (node (ref "U7") (pin "29") (pinfunction "RC1_29") (pintype "bidirectional"))
    )
    (net (code "429") (name "unconnected-(U7-RE6-Pad60)") (class "Default")
      (node (ref "U7") (pin "60") (pinfunction "RE6_60") (pintype "bidirectional"))
    )
    (net (code "430") (name "unconnected-(U7-RE7-Pad59)") (class "Default")
      (node (ref "U7") (pin "59") (pinfunction "RE7_59") (pintype "bidirectional"))
    )
    (net (code "431") (name "unconnected-(U7-RG0-Pad3)") (class "Default")
      (node (ref "U7") (pin "3") (pinfunction "RG0_3") (pintype "bidirectional"))
    )
    (net (code "432") (name "unconnected-(U8-AN12{slash}RG4-Pad8)") (class "Default")
      (node (ref "U8") (pin "8") (pinfunction "AN12/RG4_8") (pintype "bidirectional"))
    )
    (net (code "433") (name "unconnected-(U8-AN13{slash}RG3-Pad6)") (class "Default")
      (node (ref "U8") (pin "6") (pinfunction "AN13/RG3_6") (pintype "bidirectional"))
    )
    (net (code "434") (name "unconnected-(U8-RA4-Pad28)") (class "Default")
      (node (ref "U8") (pin "28") (pinfunction "RA4_28") (pintype "bidirectional"))
    )
    (net (code "435") (name "unconnected-(U8-RA6-Pad40)") (class "Default")
      (node (ref "U8") (pin "40") (pinfunction "RA6_40") (pintype "bidirectional"))
    )
    (net (code "436") (name "unconnected-(U8-RG0-Pad3)") (class "Default")
      (node (ref "U8") (pin "3") (pinfunction "RG0_3") (pintype "bidirectional"))
    )
    (net (code "437") (name "unconnected-(U11-RDY{slash}~{BSY}-Pad5)") (class "Default")
      (node (ref "U11") (pin "5") (pinfunction "RDY/~{BSY}_5") (pintype "output"))
    )
    (net (code "438") (name "unconnected-(U12-RDY{slash}~{BSY}-Pad5)") (class "Default")
      (node (ref "U12") (pin "5") (pinfunction "RDY/~{BSY}_5") (pintype "output"))
    )
    (net (code "439") (name "unconnected-(X-NORTH-PadM1)") (class "Default")
      (node (ref "X-NORTH") (pin "M1") (pinfunction "M1_M1") (pintype "bidirectional"))
    )
    (net (code "440") (name "unconnected-(X-NORTH-PadM2)") (class "Default")
      (node (ref "X-NORTH") (pin "M2") (pinfunction "M2_M2") (pintype "bidirectional"))
    )
    (net (code "441") (name "unconnected-(X-SOUTH-PadM1)") (class "Default")
      (node (ref "X-SOUTH") (pin "M1") (pinfunction "M1_M1") (pintype "bidirectional"))
    )
    (net (code "442") (name "unconnected-(X-SOUTH-PadM2)") (class "Default")
      (node (ref "X-SOUTH") (pin "M2") (pinfunction "M2_M2") (pintype "bidirectional"))
    )
    (net (code "443") (name "~{E_SS}") (class "Default")
      (node (ref "U1") (pin "11") (pinfunction "~{SS1}/AN5/RF7_11") (pintype "bidirectional"))
      (node (ref "U1") (pin "33") (pinfunction "RC2_33") (pintype "bidirectional"))
      (node (ref "U2") (pin "11") (pinfunction "~{SS1}/AN5/RF7_11") (pintype "bidirectional"))
      (node (ref "U2") (pin "33") (pinfunction "RC2_33") (pintype "bidirectional"))
      (node (ref "U5") (pin "11") (pinfunction "~{SS1}/AN5/RF7_11") (pintype "bidirectional"))
      (node (ref "U5") (pin "33") (pinfunction "RC2_33") (pintype "bidirectional"))
      (node (ref "U7") (pin "11") (pinfunction "~{SS1}/AN5/RF7_11") (pintype "bidirectional"))
      (node (ref "U7") (pin "33") (pinfunction "RC2_33") (pintype "bidirectional"))
    )
    (net (code "444") (name "~{LDAC_N}") (class "Default")
      (node (ref "U11") (pin "4") (pinfunction "~{LDAC}_4") (pintype "input"))
      (node (ref "U8") (pin "52") (pinfunction "SDO2/RD4_52") (pintype "bidirectional"))
    )
    (net (code "445") (name "~{LDAC_S}") (class "Default")
      (node (ref "U12") (pin "4") (pinfunction "~{LDAC}_4") (pintype "input"))
      (node (ref "U5") (pin "52") (pinfunction "SDO2/RD4_52") (pintype "bidirectional"))
    )
    (net (code "446") (name "~{MCLR1}") (class "Default")
      (node (ref "ICSP1") (pin "4") (pinfunction "4_4") (pintype "passive"))
      (node (ref "R12") (pin "2") (pinfunction "2_2") (pintype "passive"))
      (node (ref "U1") (pin "7") (pinfunction "~{MCLR}/RG5_7") (pintype "bidirectional"))
    )
    (net (code "447") (name "~{MCLR2}") (class "Default")
      (node (ref "ICSP2") (pin "4") (pinfunction "4_4") (pintype "passive"))
      (node (ref "R11") (pin "2") (pinfunction "2_2") (pintype "passive"))
      (node (ref "U2") (pin "7") (pinfunction "~{MCLR}/RG5_7") (pintype "bidirectional"))
    )
    (net (code "448") (name "~{MCLR3}") (class "Default")
      (node (ref "ICSP3") (pin "4") (pinfunction "4_4") (pintype "passive"))
      (node (ref "R10") (pin "2") (pinfunction "2_2") (pintype "passive"))
      (node (ref "U3") (pin "7") (pinfunction "~{MCLR}/RG5_7") (pintype "bidirectional"))
    )
    (net (code "449") (name "~{MCLR4}") (class "Default")
      (node (ref "ICSP4") (pin "4") (pinfunction "4_4") (pintype "passive"))
      (node (ref "R9") (pin "2") (pinfunction "2_2") (pintype "passive"))
      (node (ref "U4") (pin "7") (pinfunction "~{MCLR}/RG5_7") (pintype "bidirectional"))
    )
    (net (code "450") (name "~{MCLR5}") (class "Default")
      (node (ref "ICSP5") (pin "4") (pinfunction "4_4") (pintype "passive"))
      (node (ref "R8") (pin "2") (pinfunction "2_2") (pintype "passive"))
      (node (ref "U5") (pin "7") (pinfunction "~{MCLR}/RG5_7") (pintype "bidirectional"))
    )
    (net (code "451") (name "~{MCLR6}") (class "Default")
      (node (ref "ICSP6") (pin "4") (pinfunction "4_4") (pintype "passive"))
      (node (ref "R7") (pin "2") (pinfunction "2_2") (pintype "passive"))
      (node (ref "U6") (pin "7") (pinfunction "~{MCLR}/RG5_7") (pintype "bidirectional"))
    )
    (net (code "452") (name "~{MCLR7}") (class "Default")
      (node (ref "ICSP7") (pin "4") (pinfunction "4_4") (pintype "passive"))
      (node (ref "R6") (pin "2") (pinfunction "2_2") (pintype "passive"))
      (node (ref "U7") (pin "7") (pinfunction "~{MCLR}/RG5_7") (pintype "bidirectional"))
    )
    (net (code "453") (name "~{MCLR8}") (class "Default")
      (node (ref "ICSP8") (pin "4") (pinfunction "4_4") (pintype "passive"))
      (node (ref "R5") (pin "2") (pinfunction "2_2") (pintype "passive"))
      (node (ref "U8") (pin "7") (pinfunction "~{MCLR}/RG5_7") (pintype "bidirectional"))
    )
    (net (code "454") (name "~{W_SS}") (class "Default")
      (node (ref "U3") (pin "11") (pinfunction "~{SS1}/AN5/RF7_11") (pintype "bidirectional"))
      (node (ref "U3") (pin "33") (pinfunction "RC2_33") (pintype "bidirectional"))
      (node (ref "U4") (pin "11") (pinfunction "~{SS1}/AN5/RF7_11") (pintype "bidirectional"))
      (node (ref "U4") (pin "33") (pinfunction "RC2_33") (pintype "bidirectional"))
      (node (ref "U6") (pin "11") (pinfunction "~{SS1}/AN5/RF7_11") (pintype "bidirectional"))
      (node (ref "U6") (pin "33") (pinfunction "RC2_33") (pintype "bidirectional"))
      (node (ref "U8") (pin "11") (pinfunction "~{SS1}/AN5/RF7_11") (pintype "bidirectional"))
      (node (ref "U8") (pin "33") (pinfunction "RC2_33") (pintype "bidirectional"))
    )
  )
)
